# PX4FMUv2_3.net
KiCad netlist of a schematic drawn in EAGLE
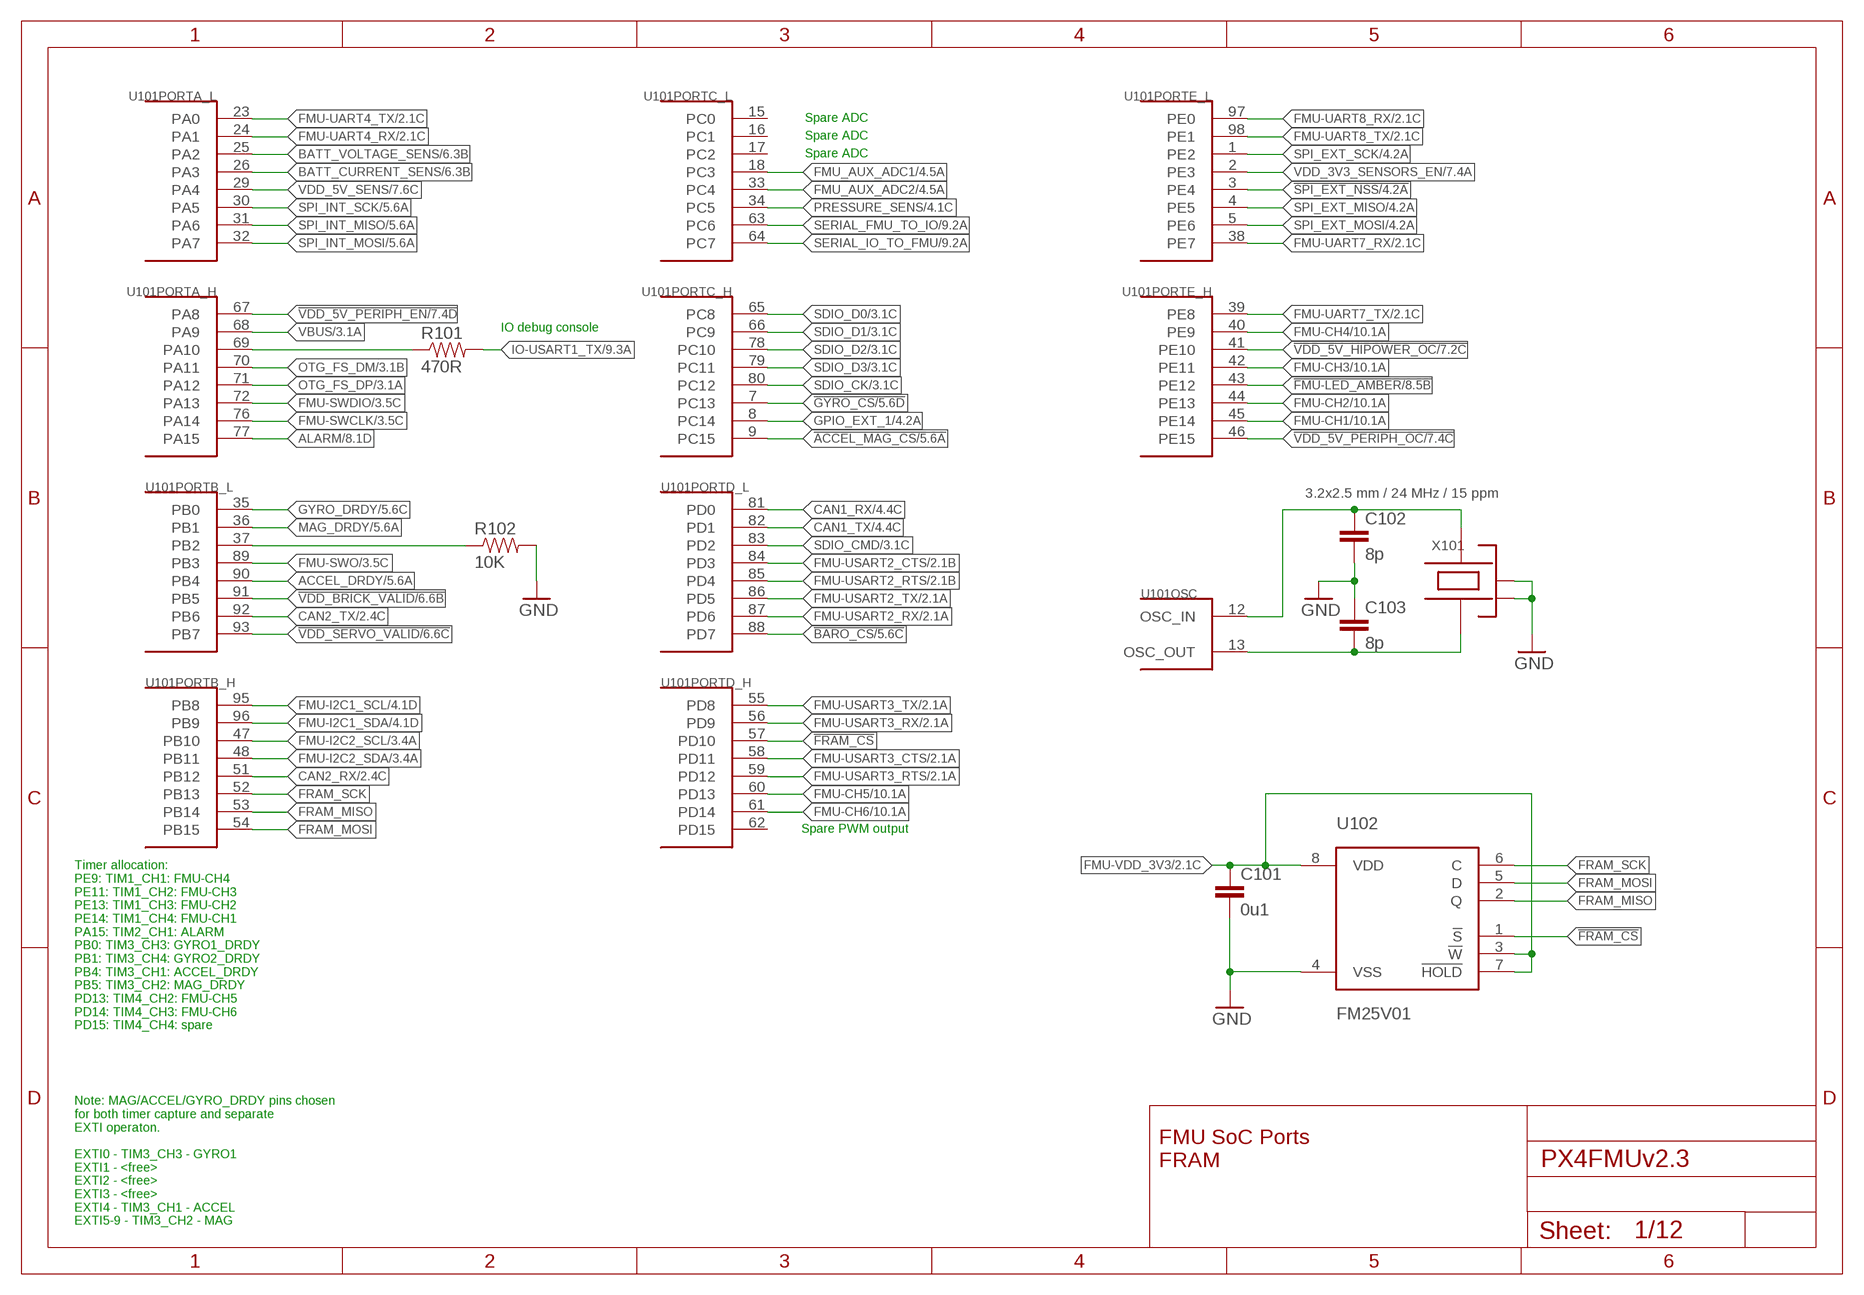
[diagram p0: schematic, sheet 1]
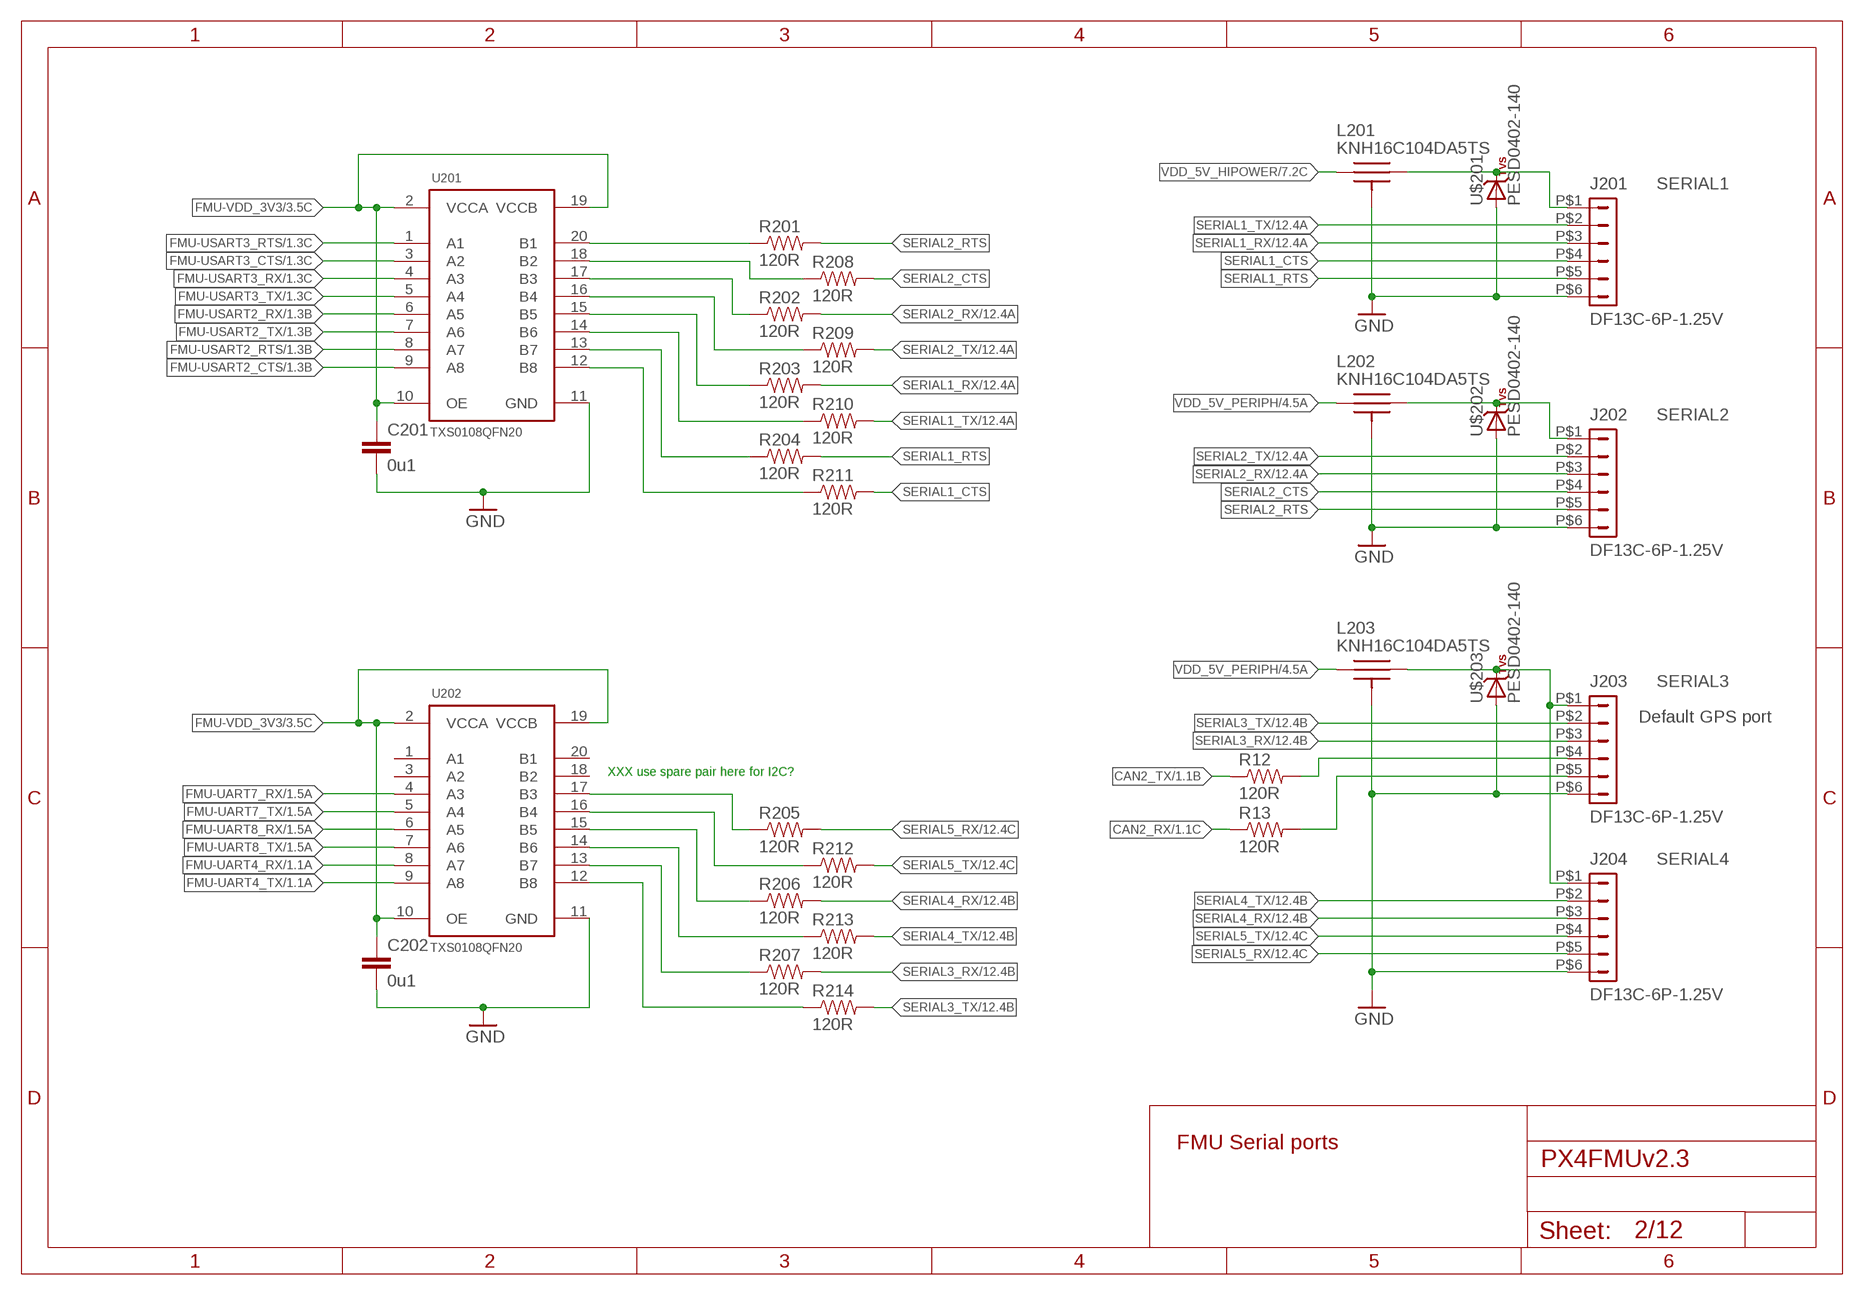
[diagram p1: schematic, sheet 2]
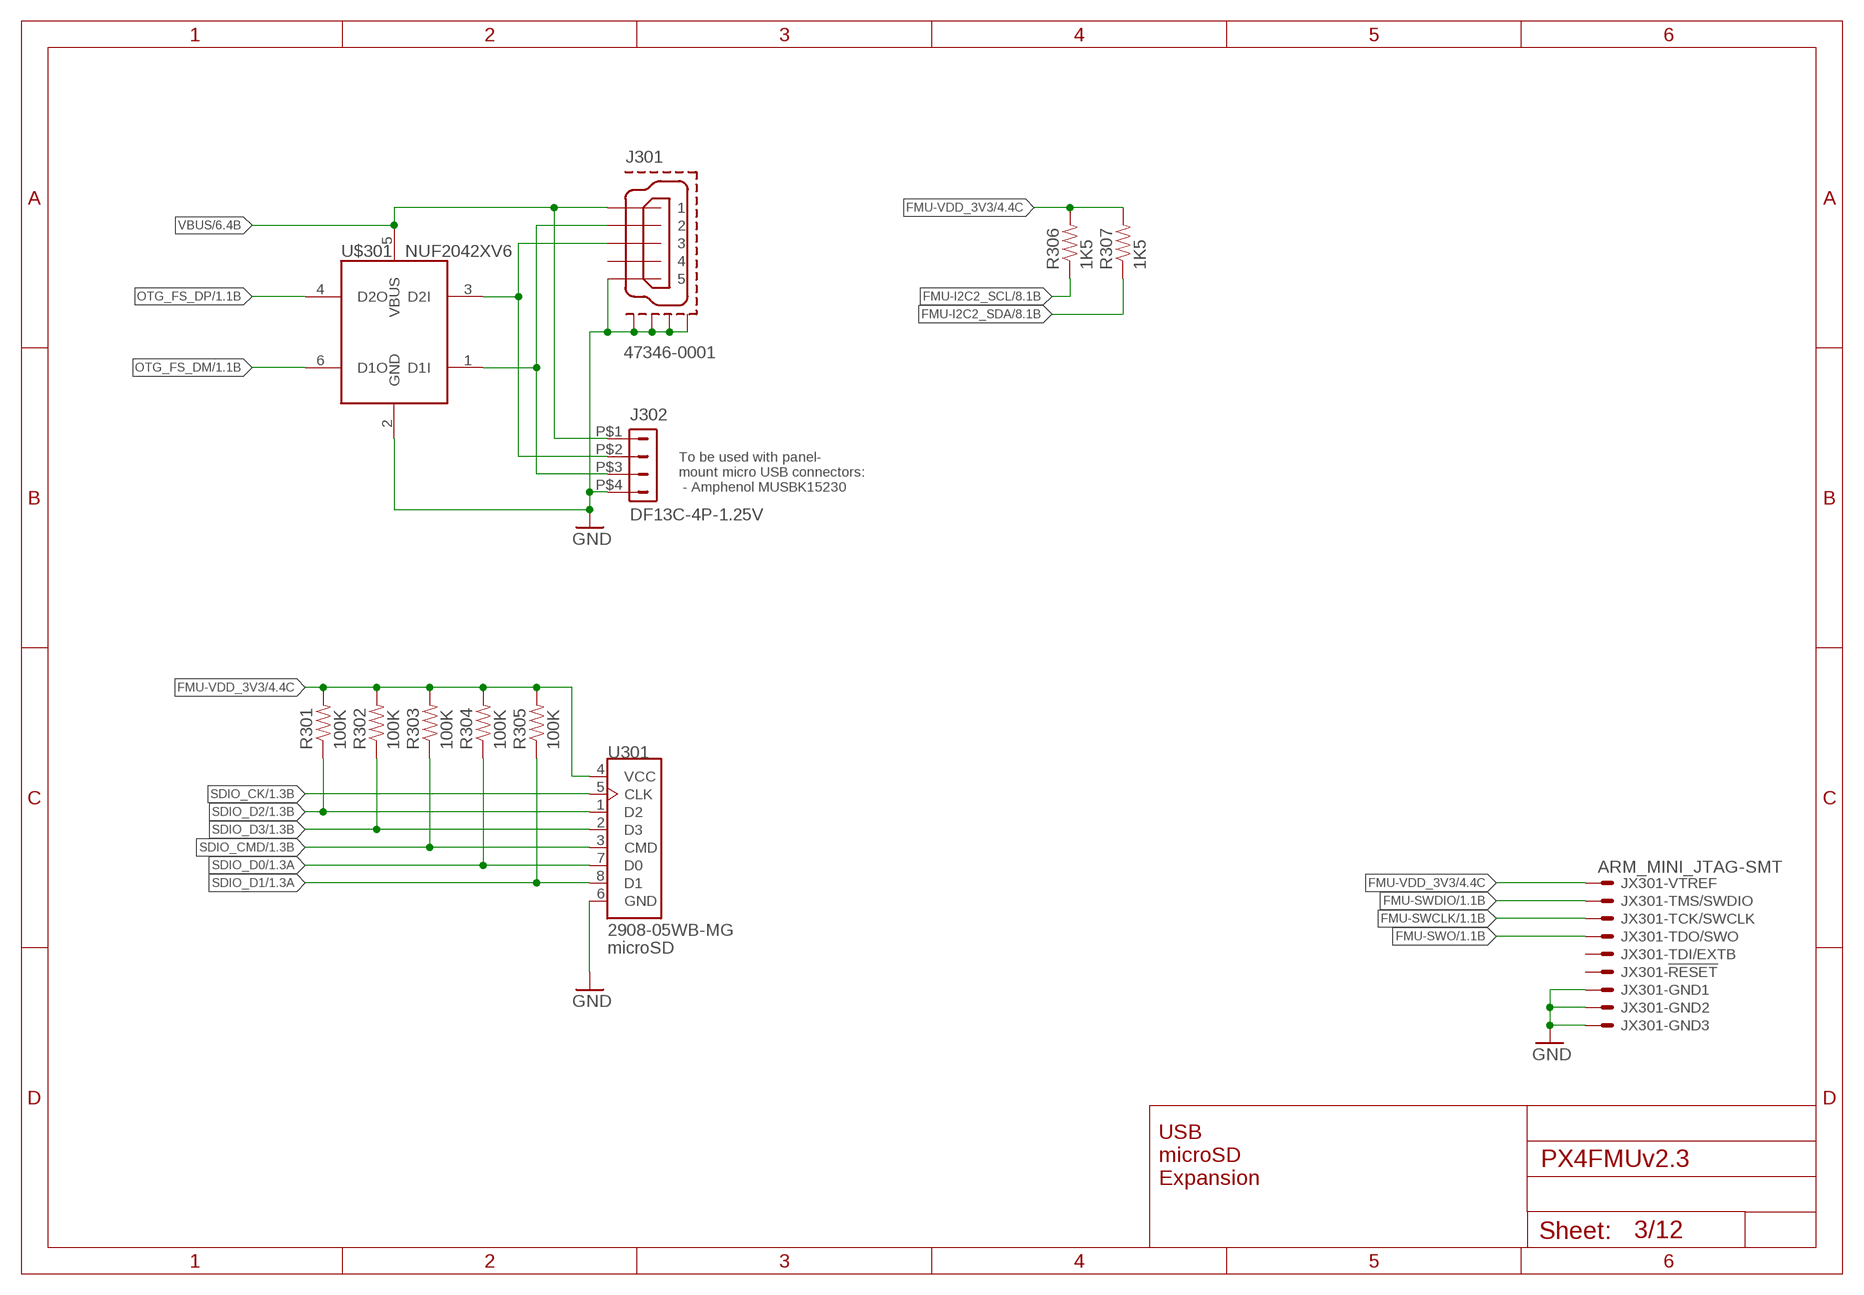
[diagram p2: schematic, sheet 3]
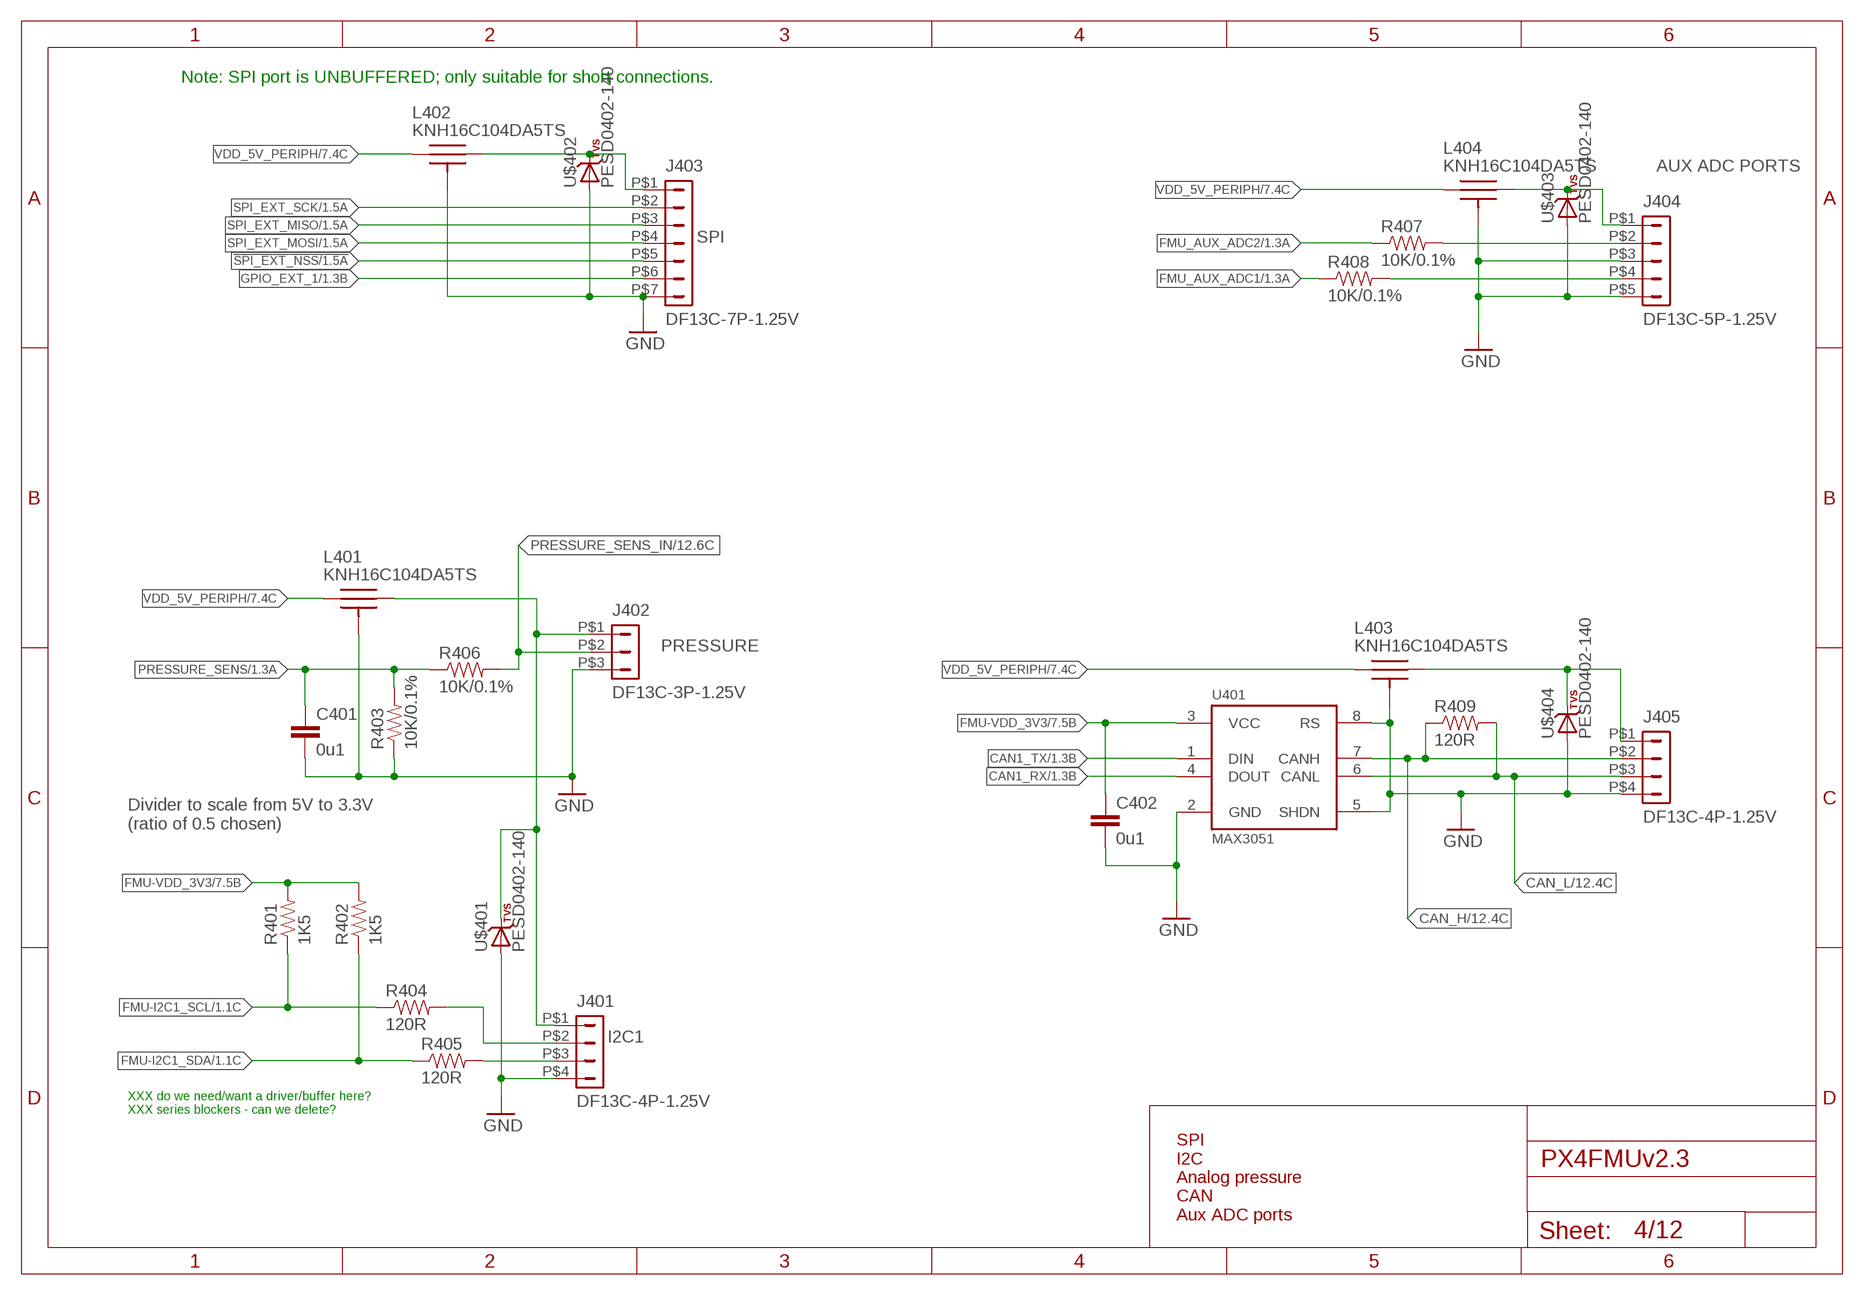
[diagram p3: schematic, sheet 4]
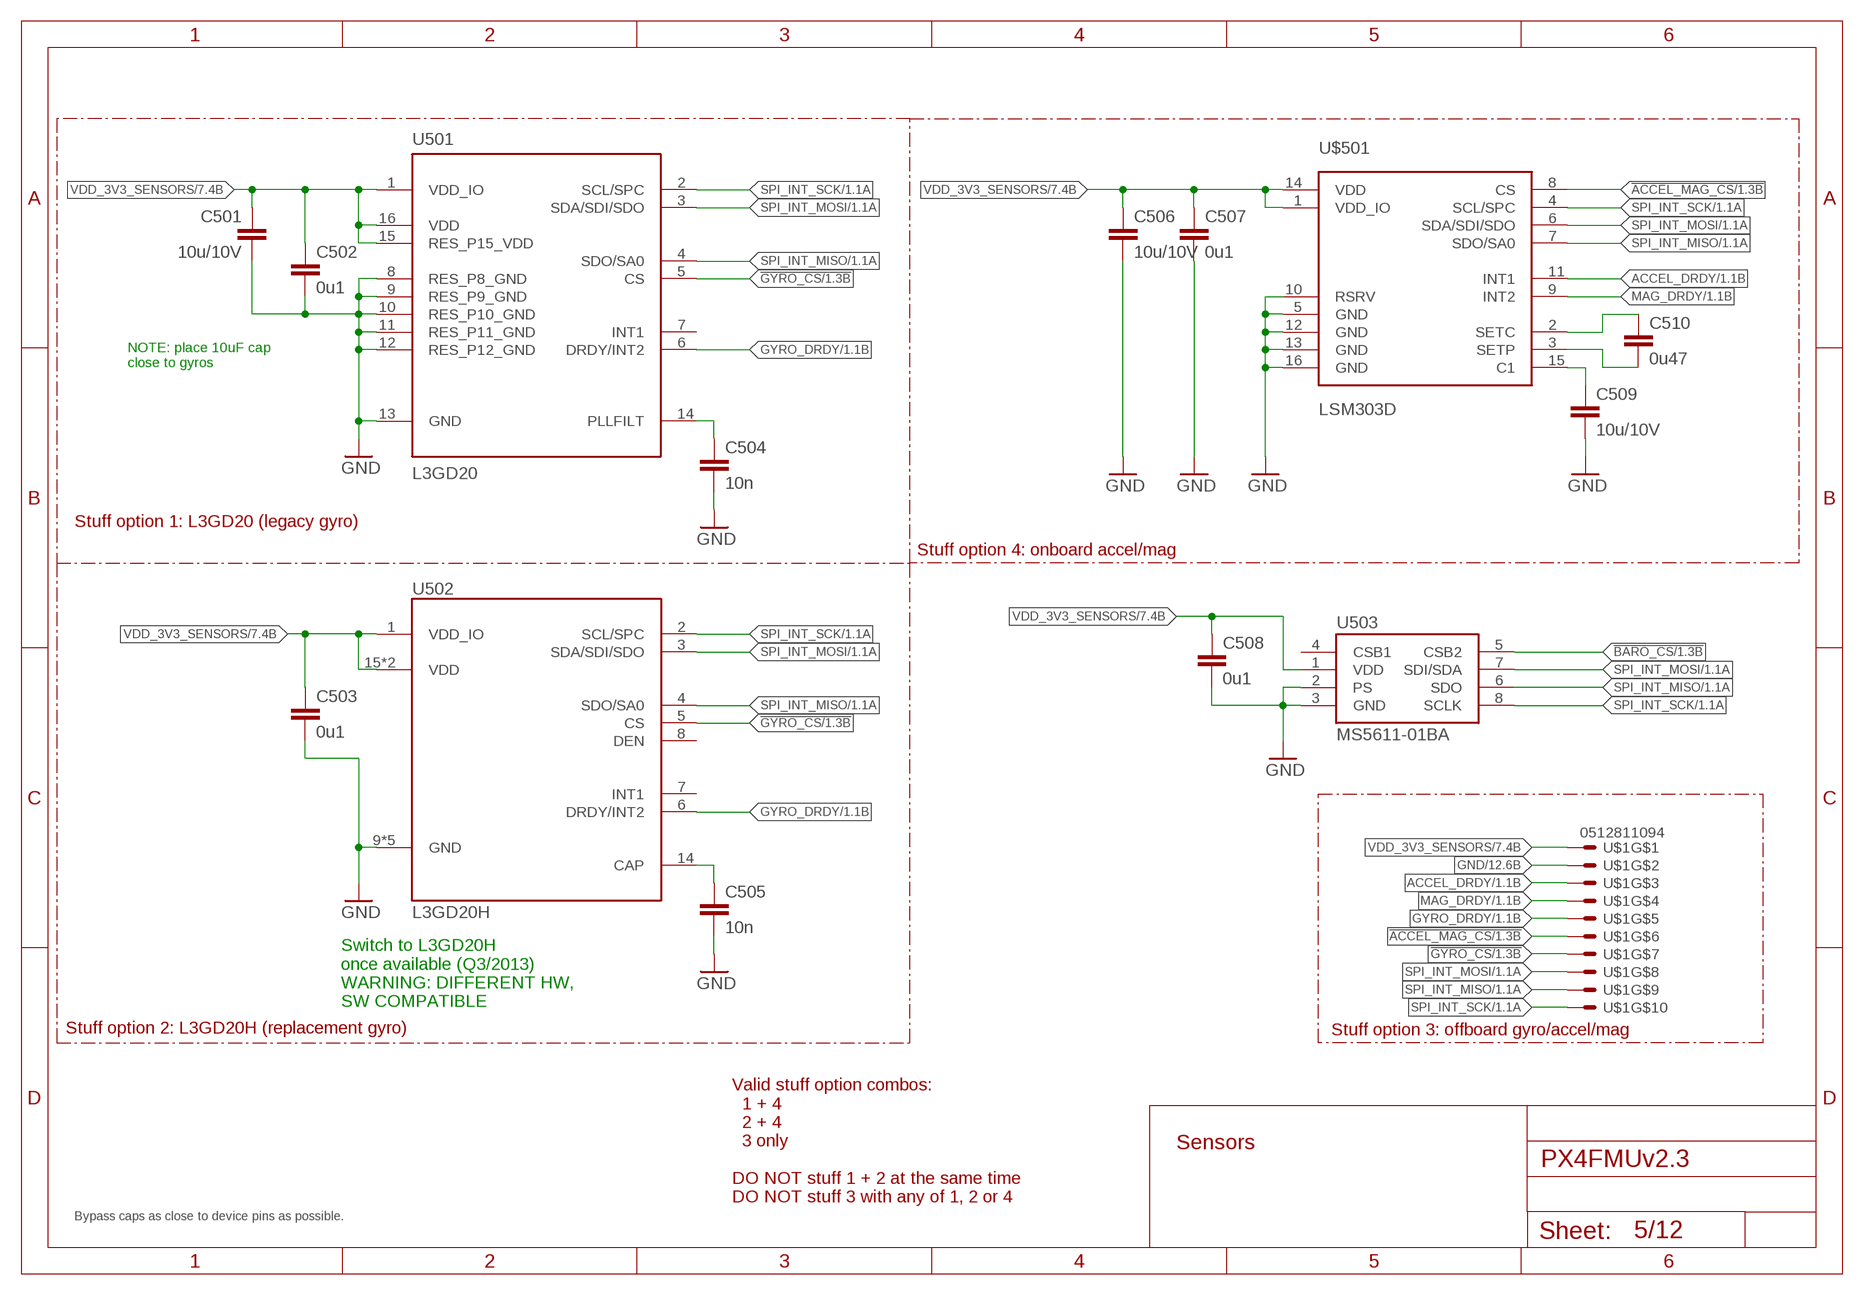
[diagram p4: schematic, sheet 5]
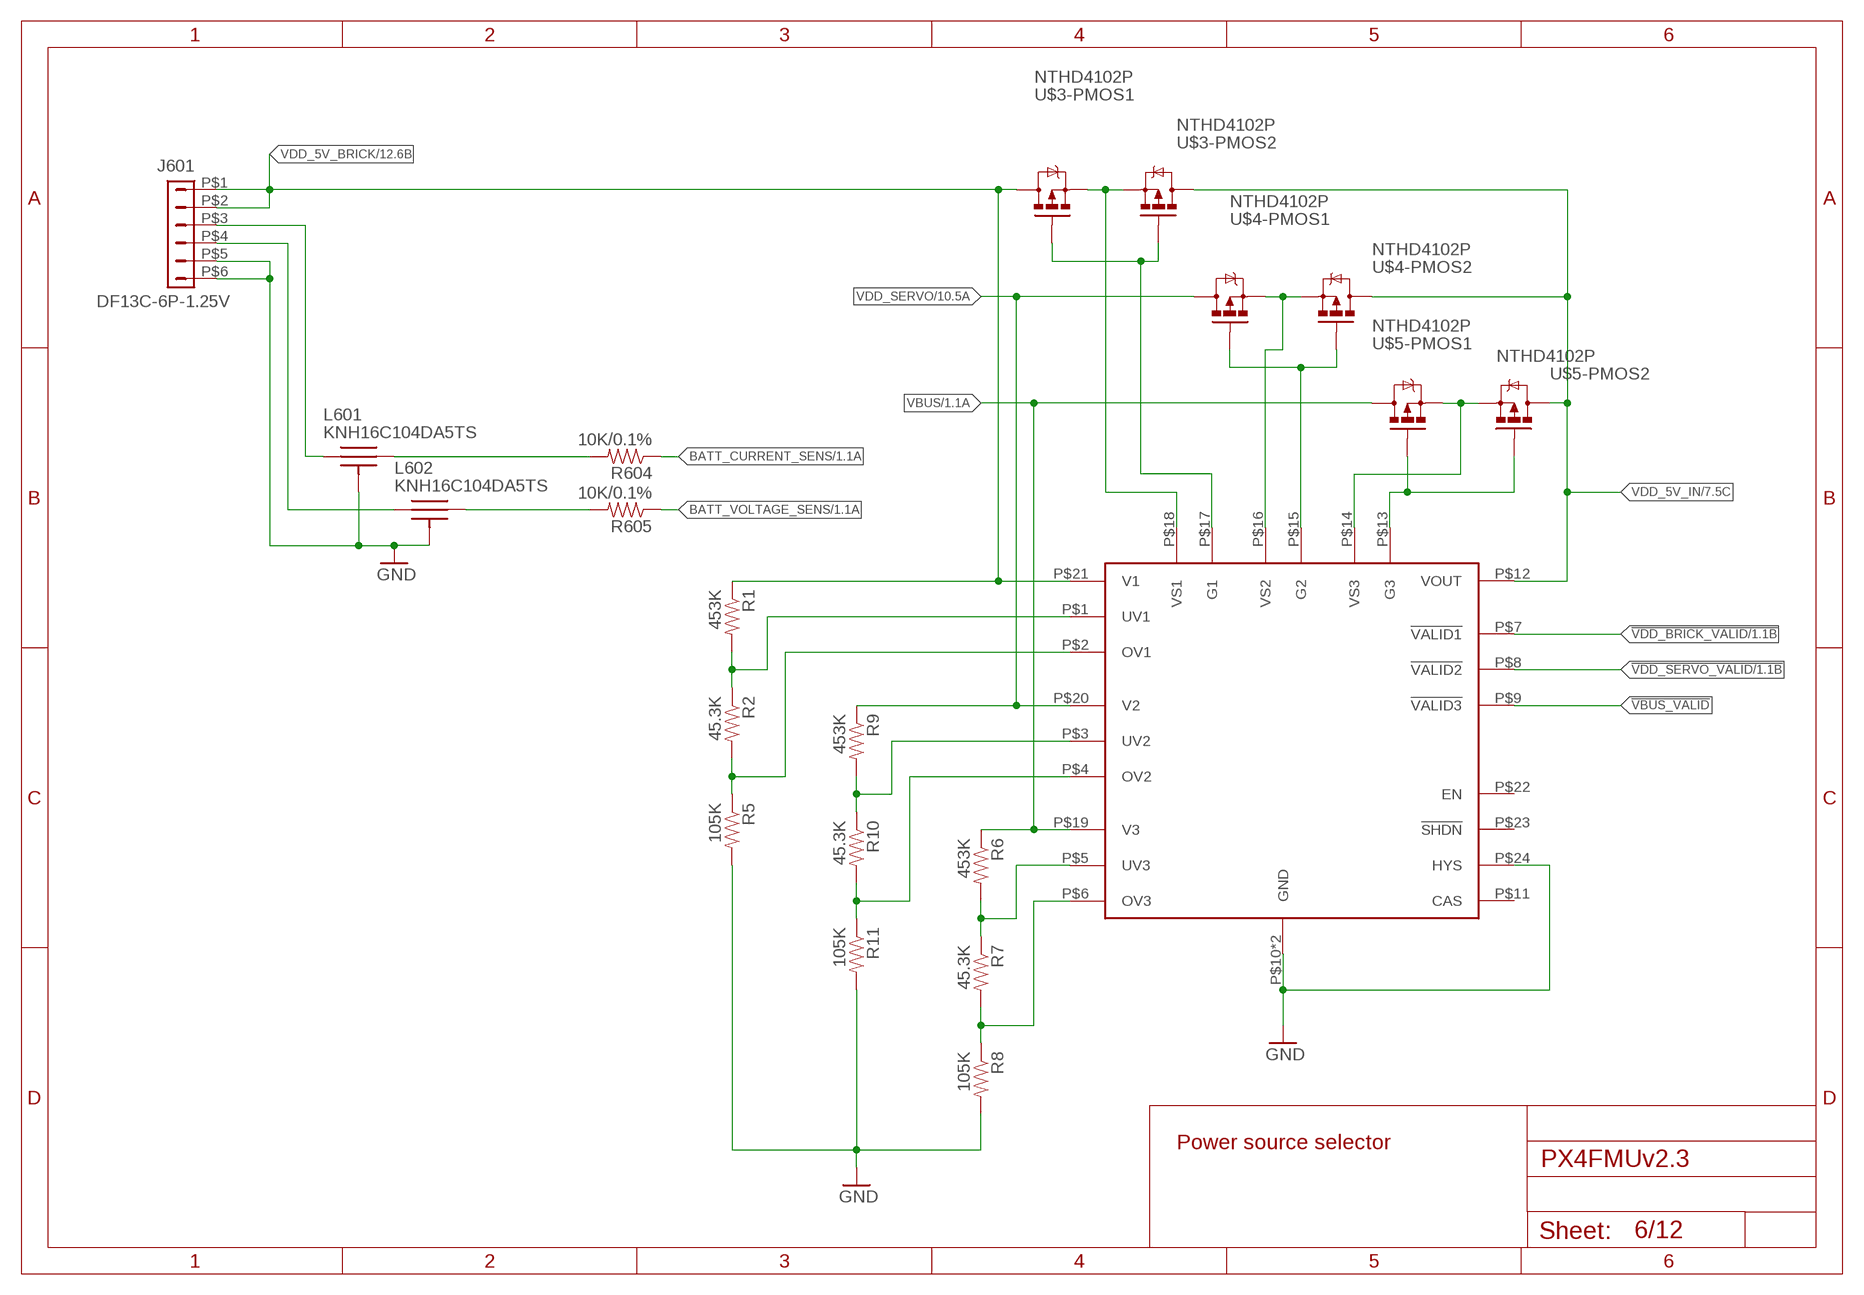
[diagram p5: schematic, sheet 6]
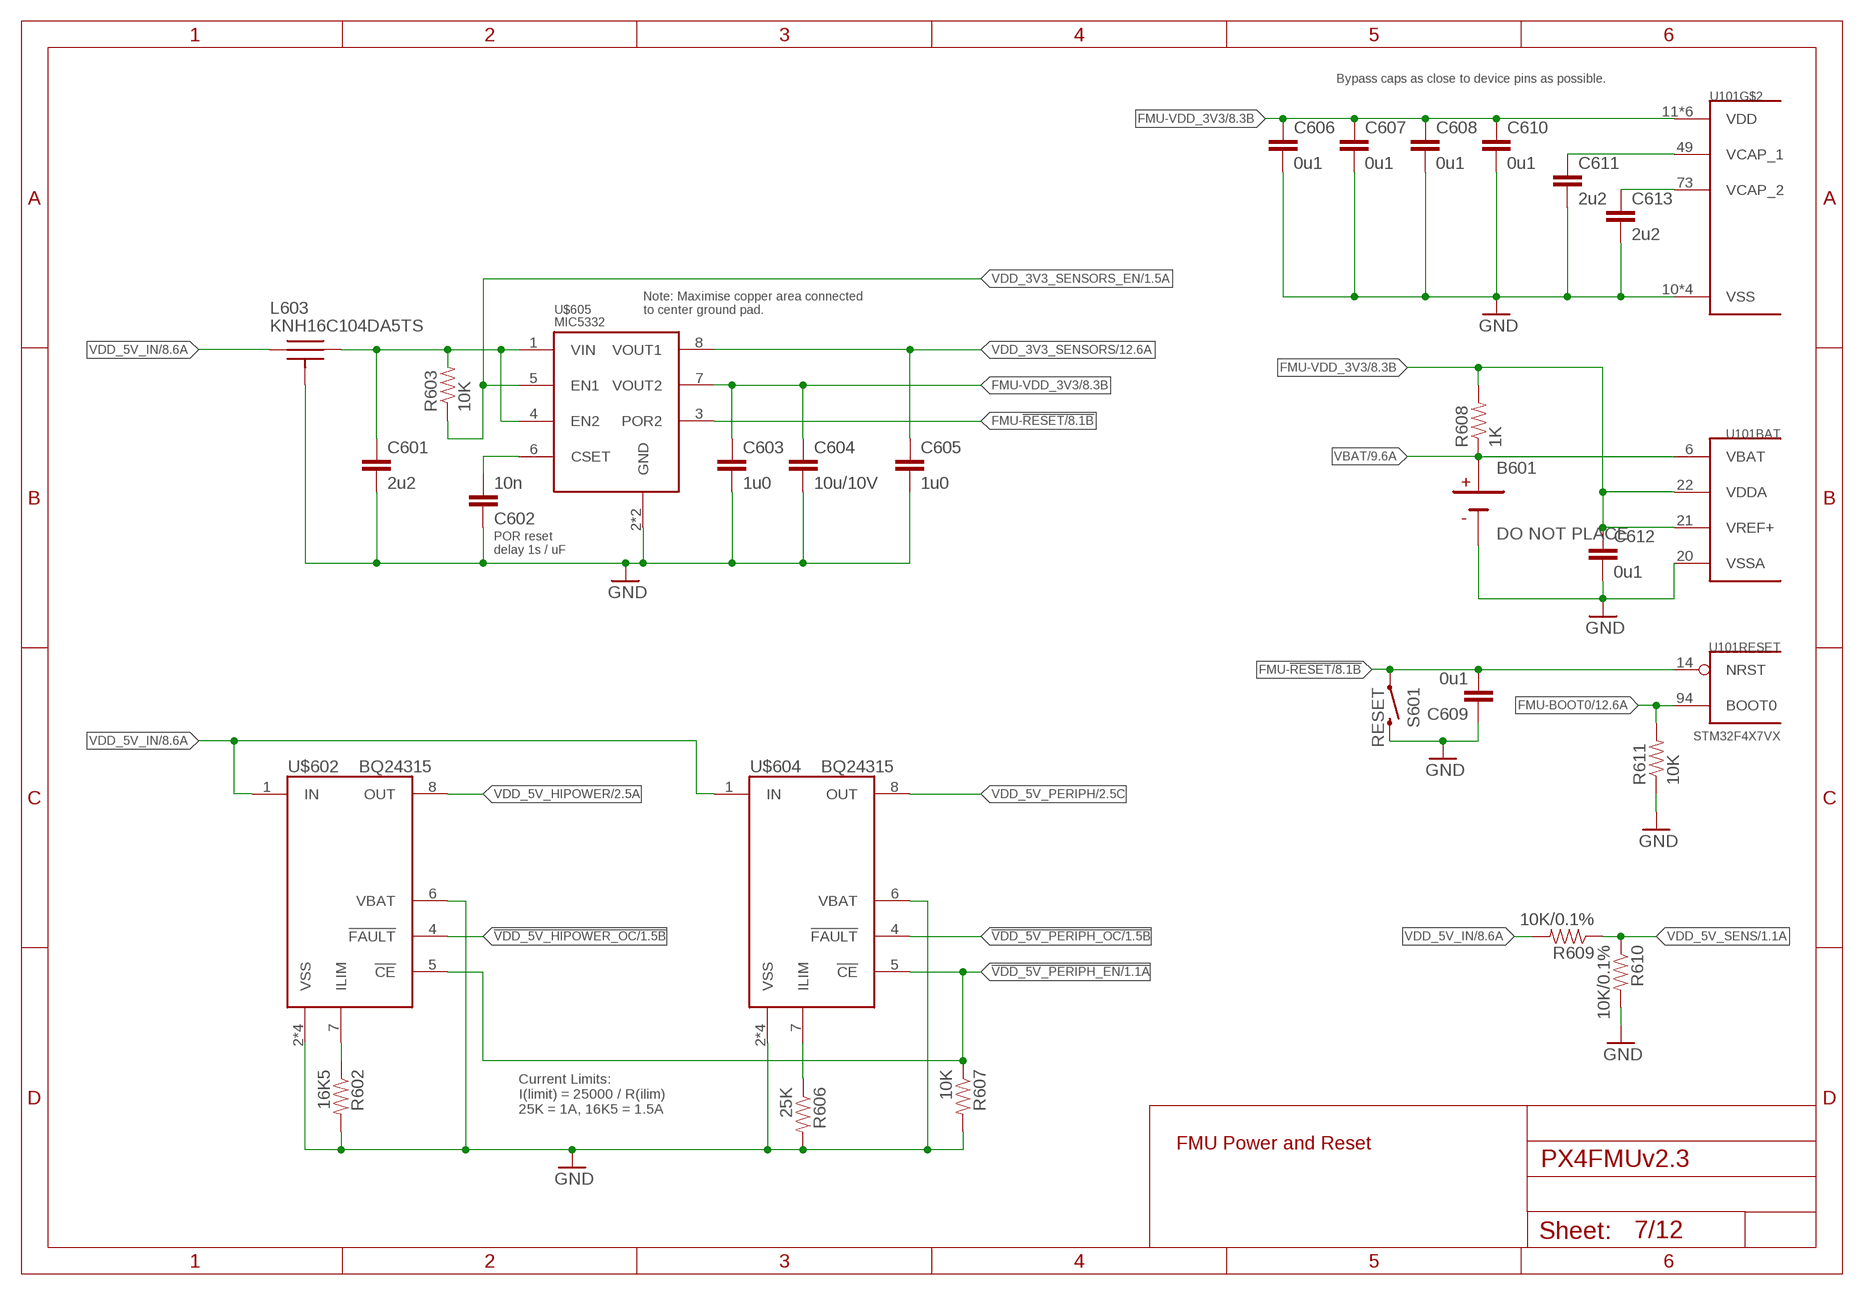
[diagram p6: schematic, sheet 7]
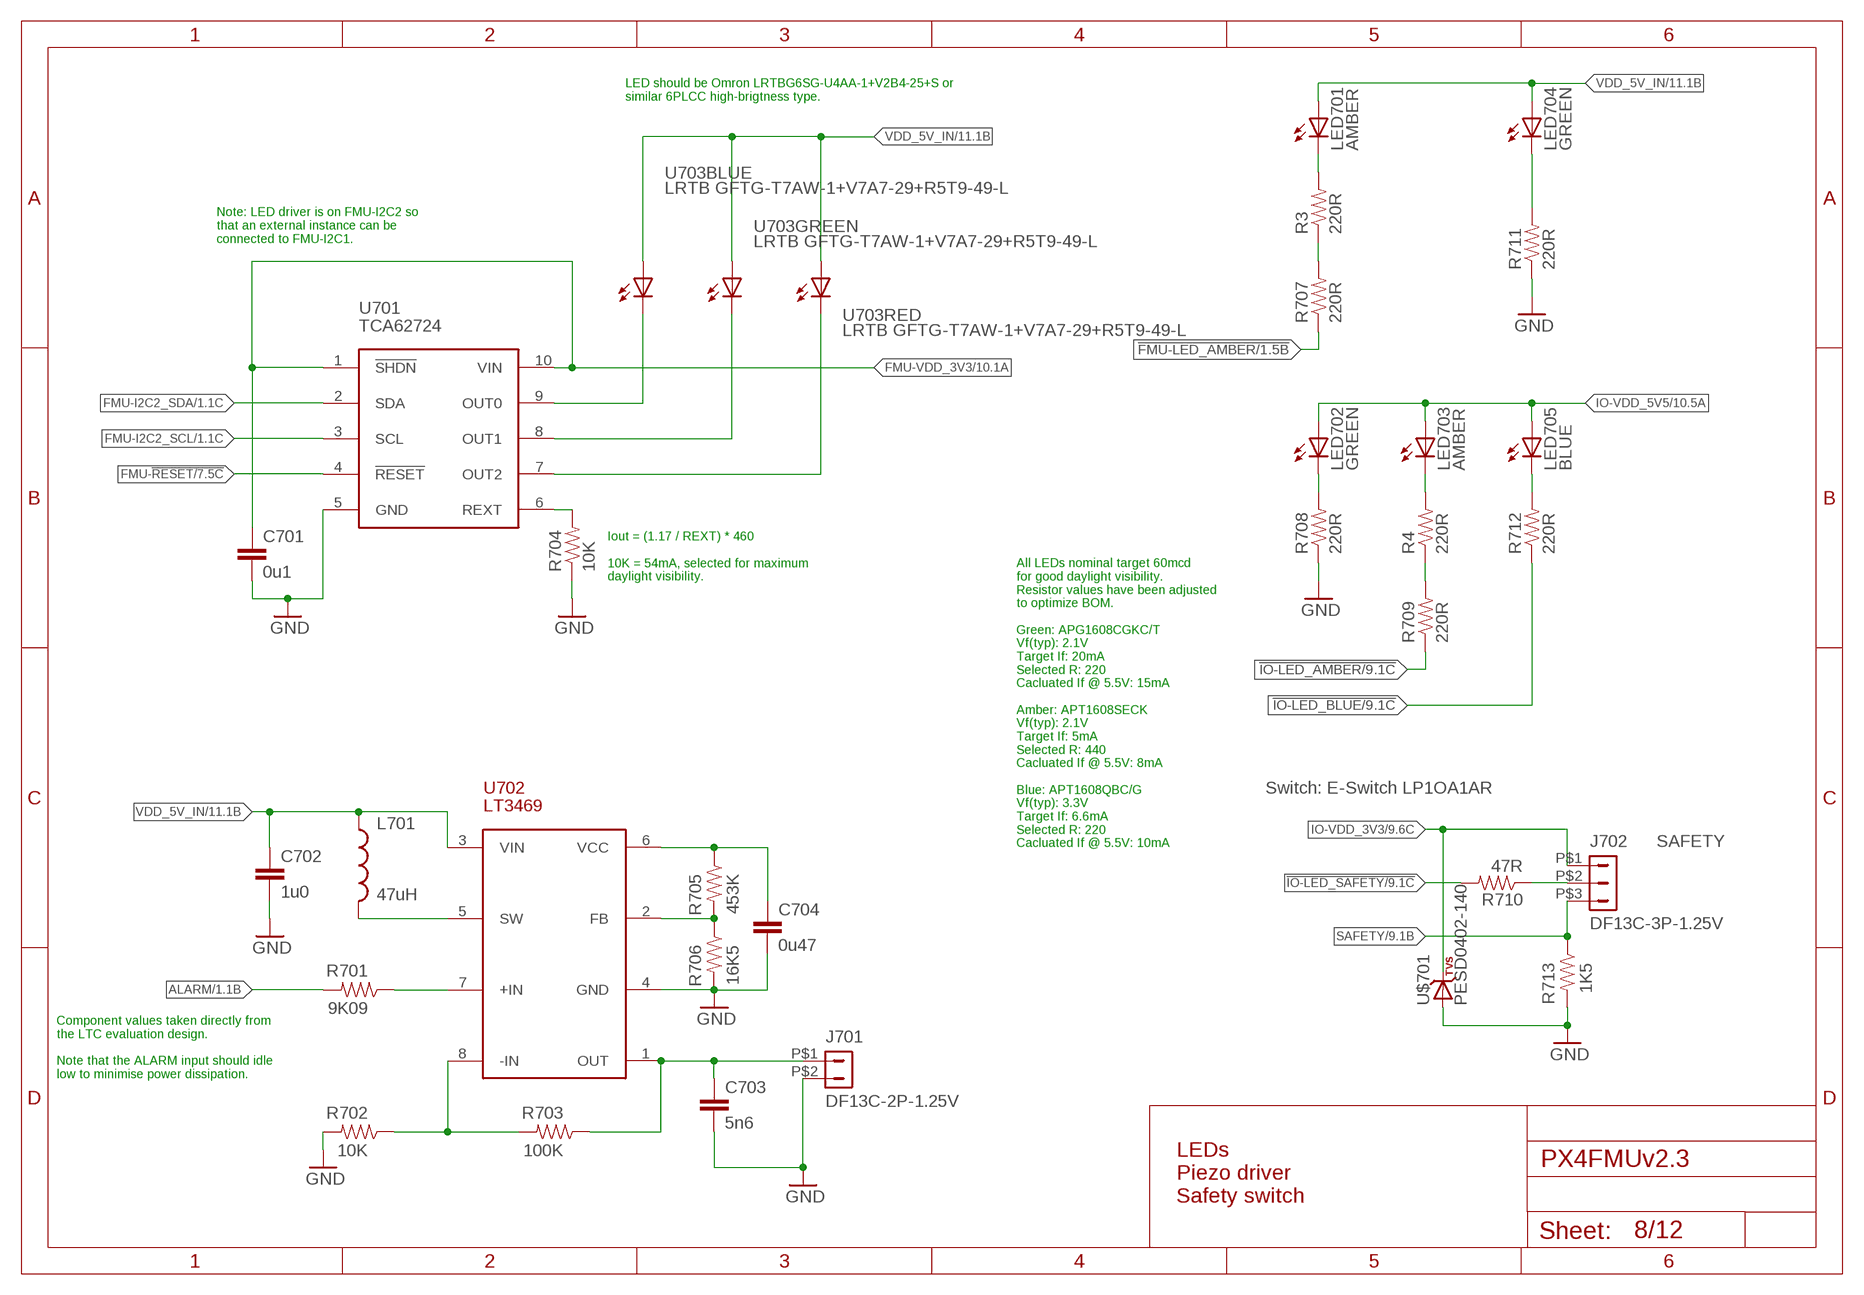
[diagram p7: schematic, sheet 8]
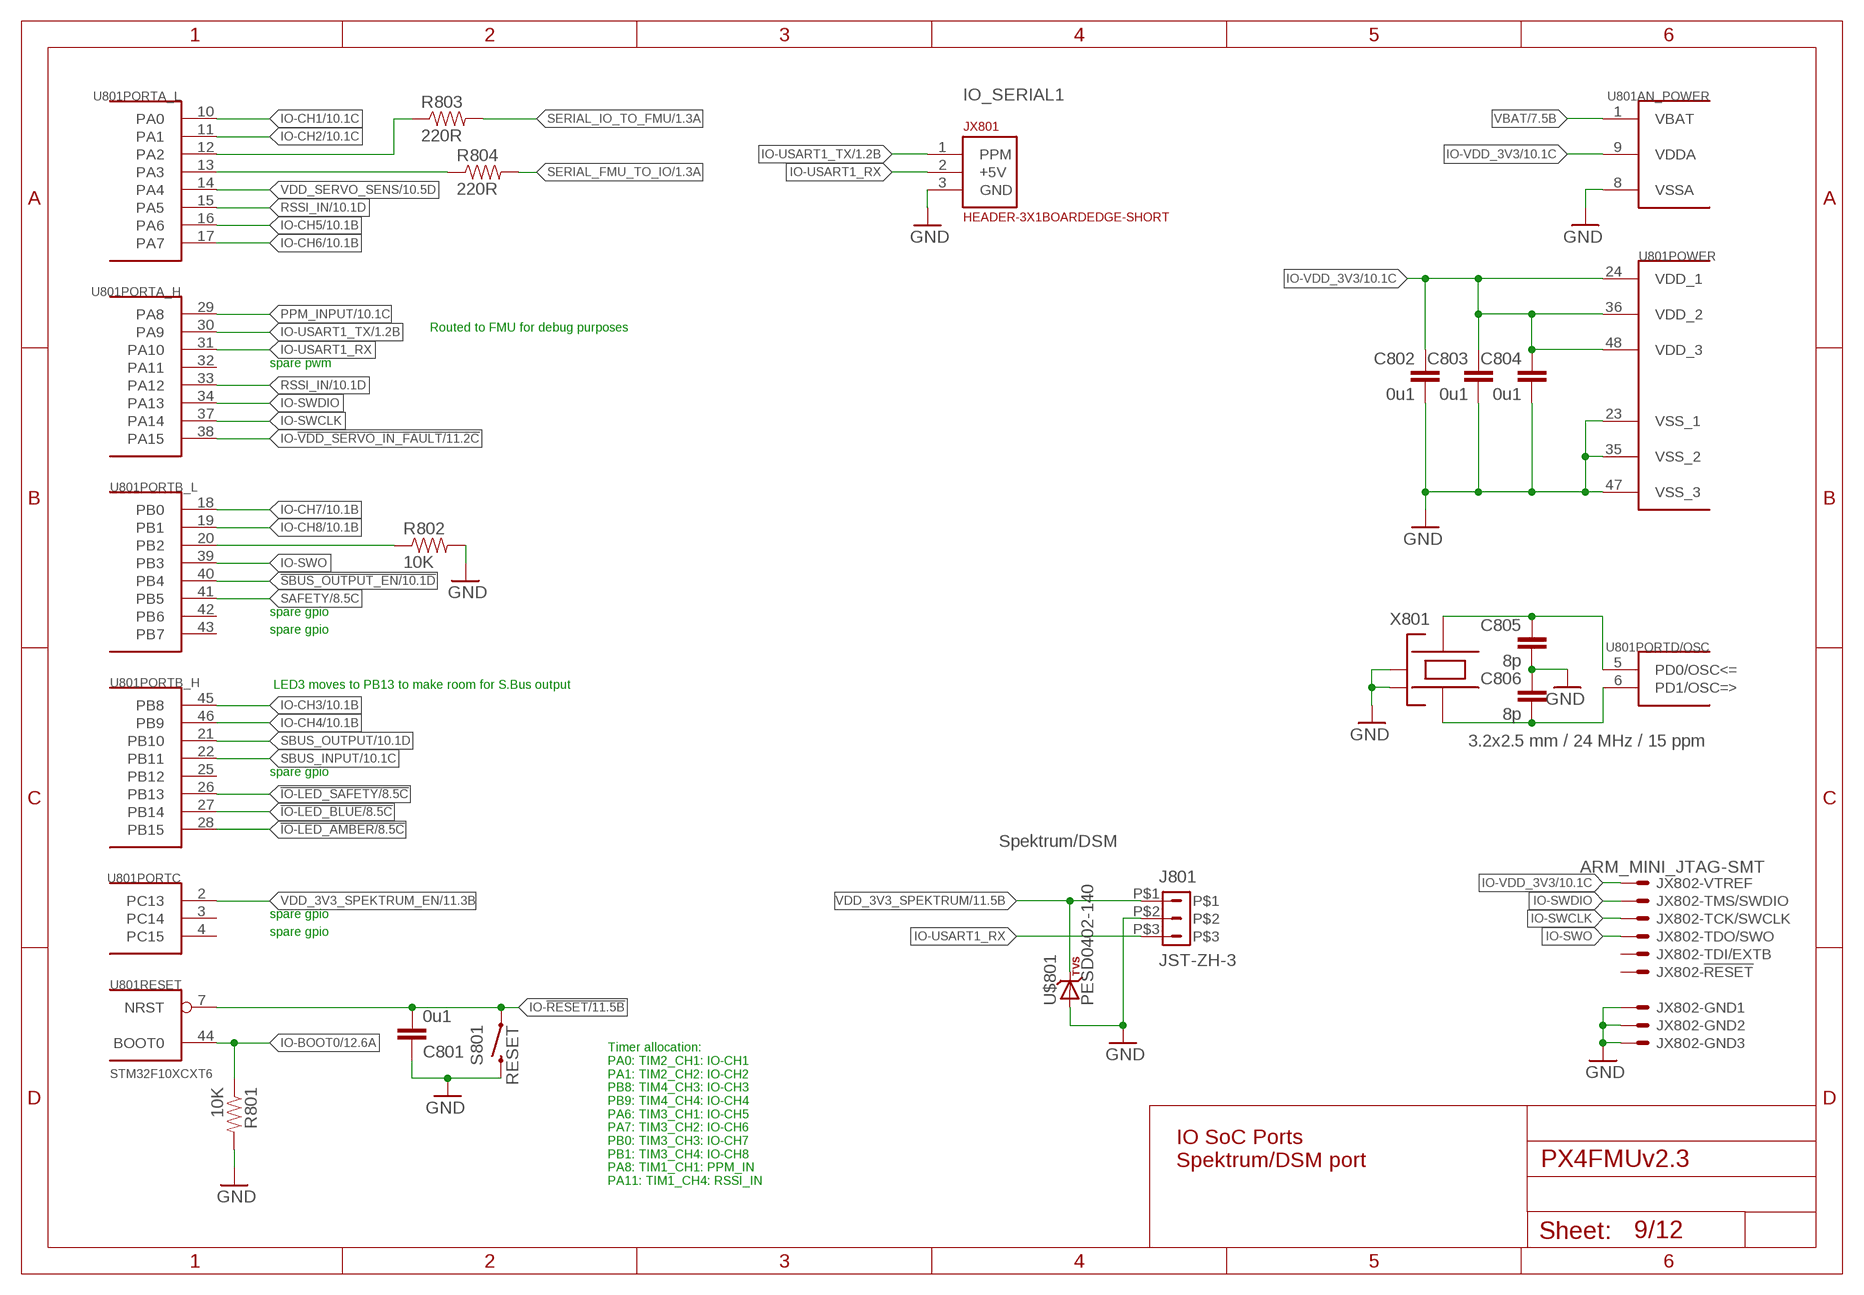
[diagram p8: schematic, sheet 9]
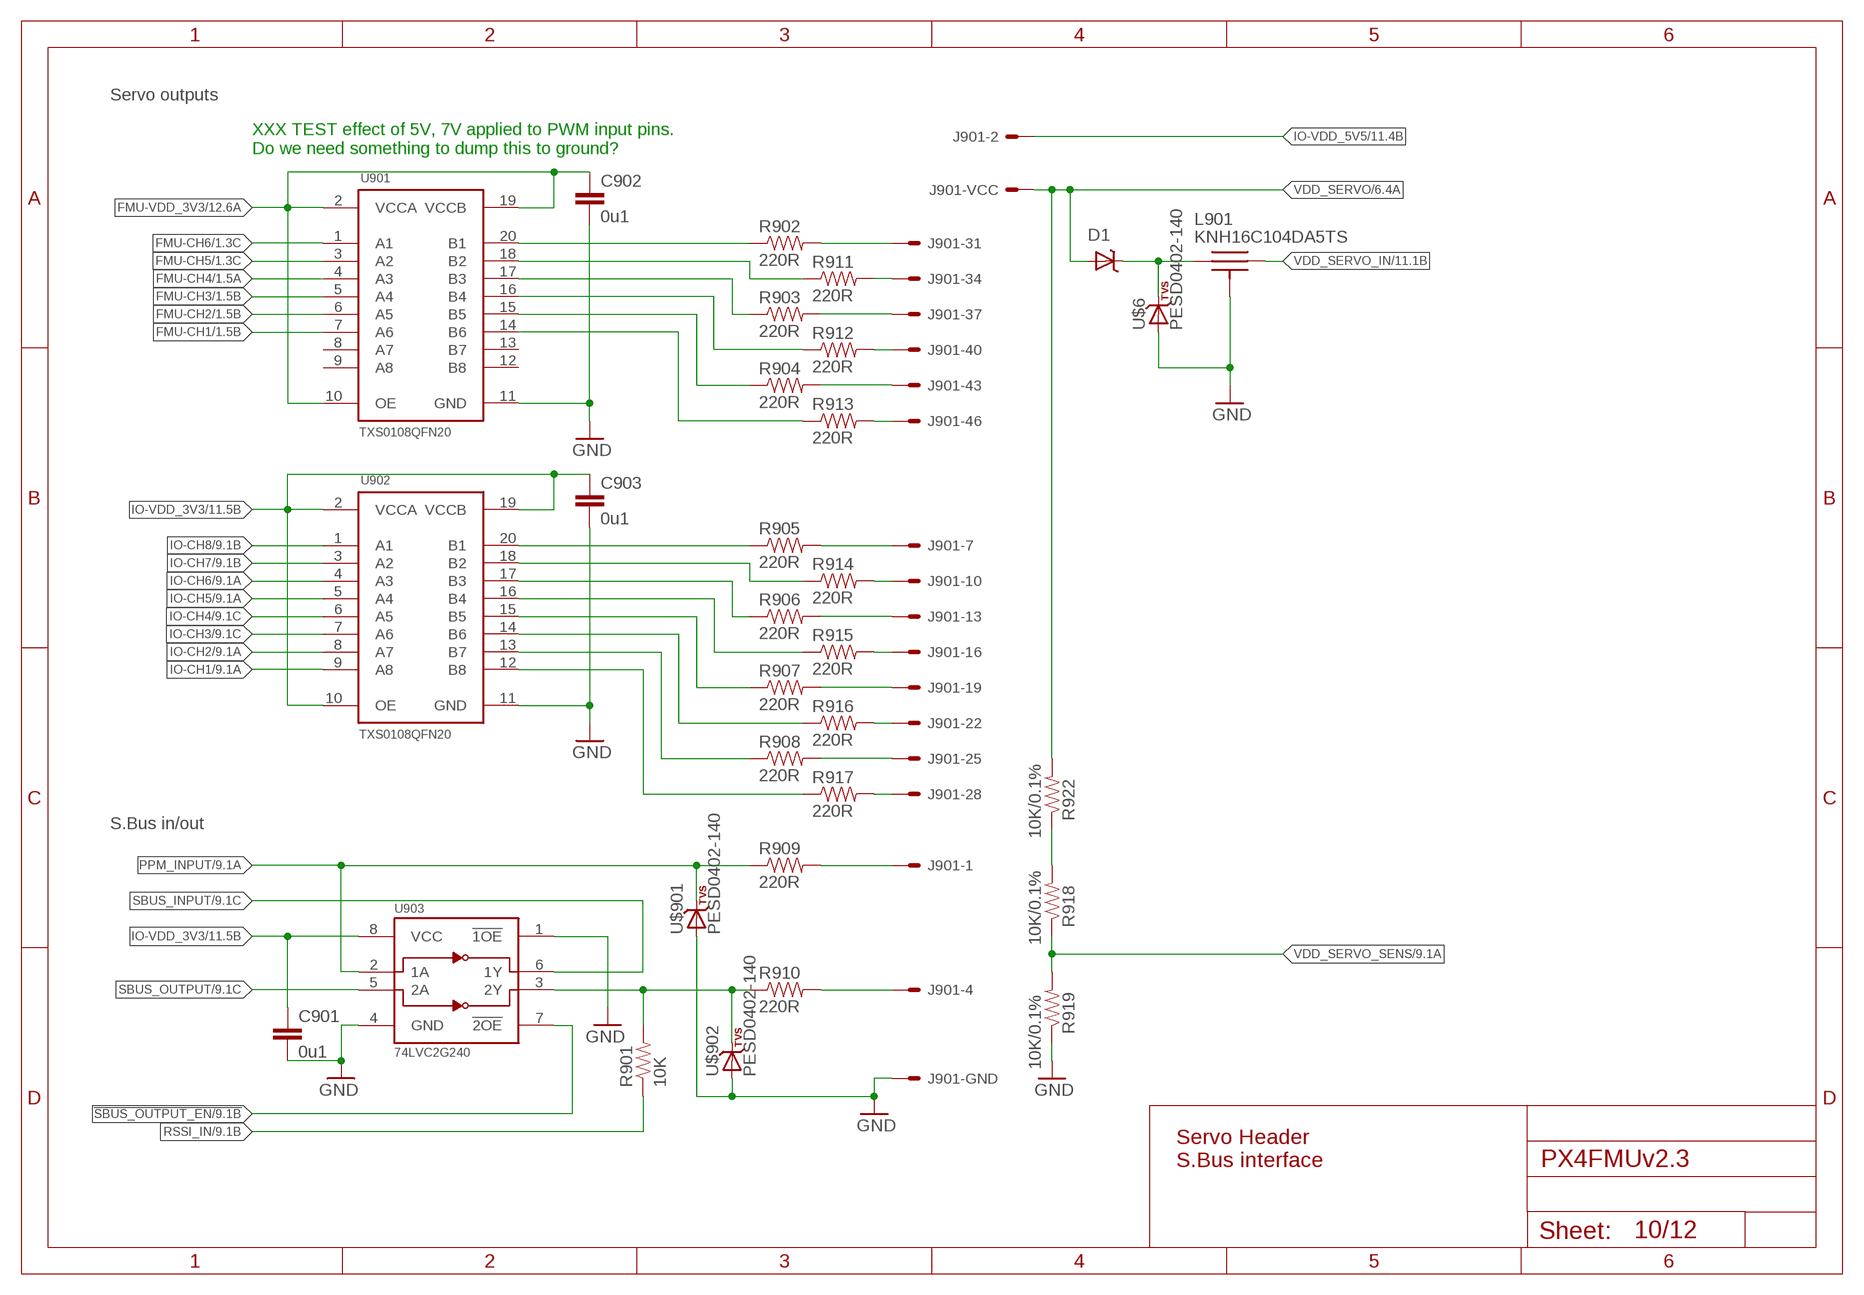
[diagram p9: schematic, sheet 10]
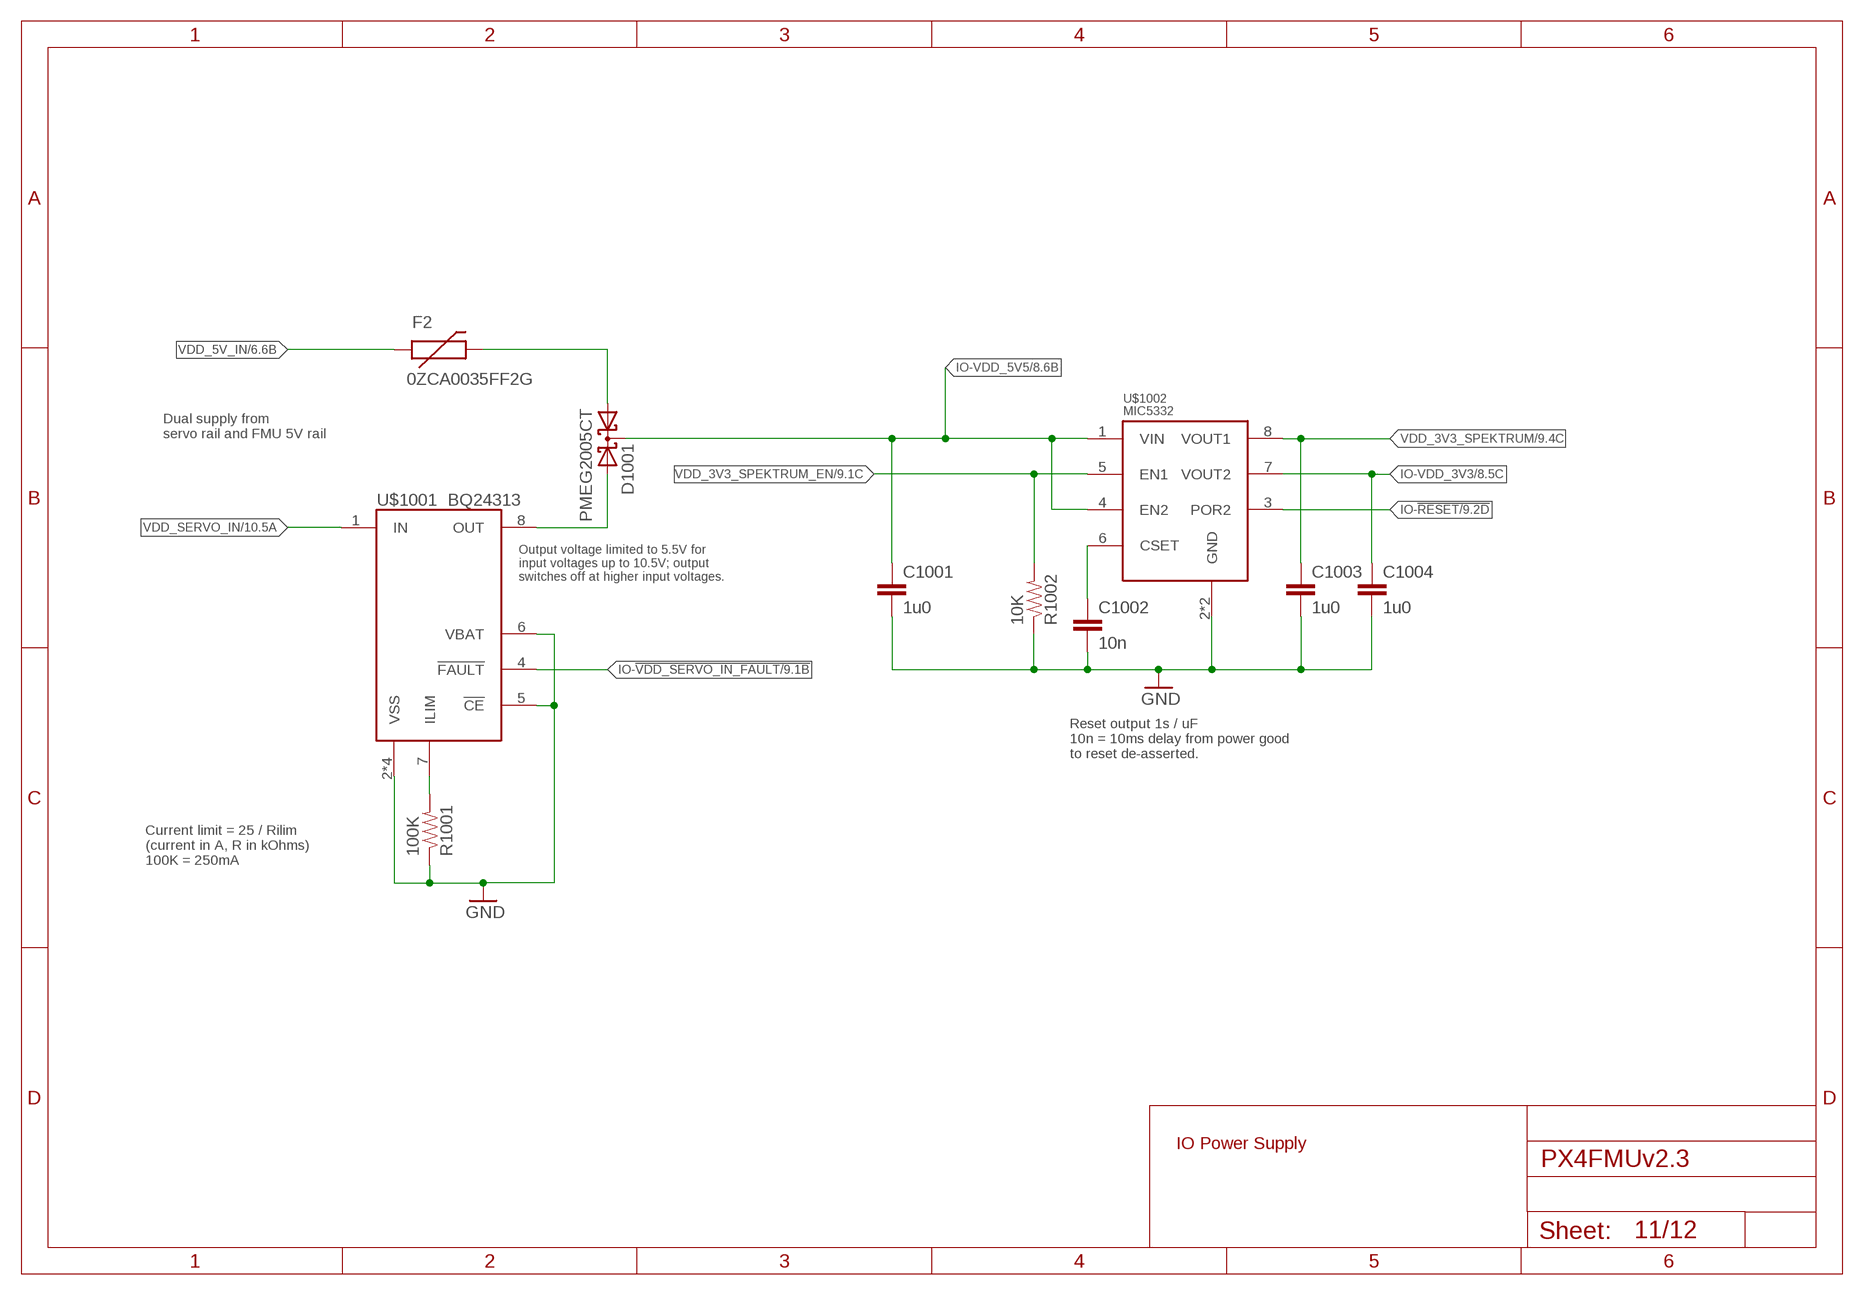
[diagram p10: schematic, sheet 11]
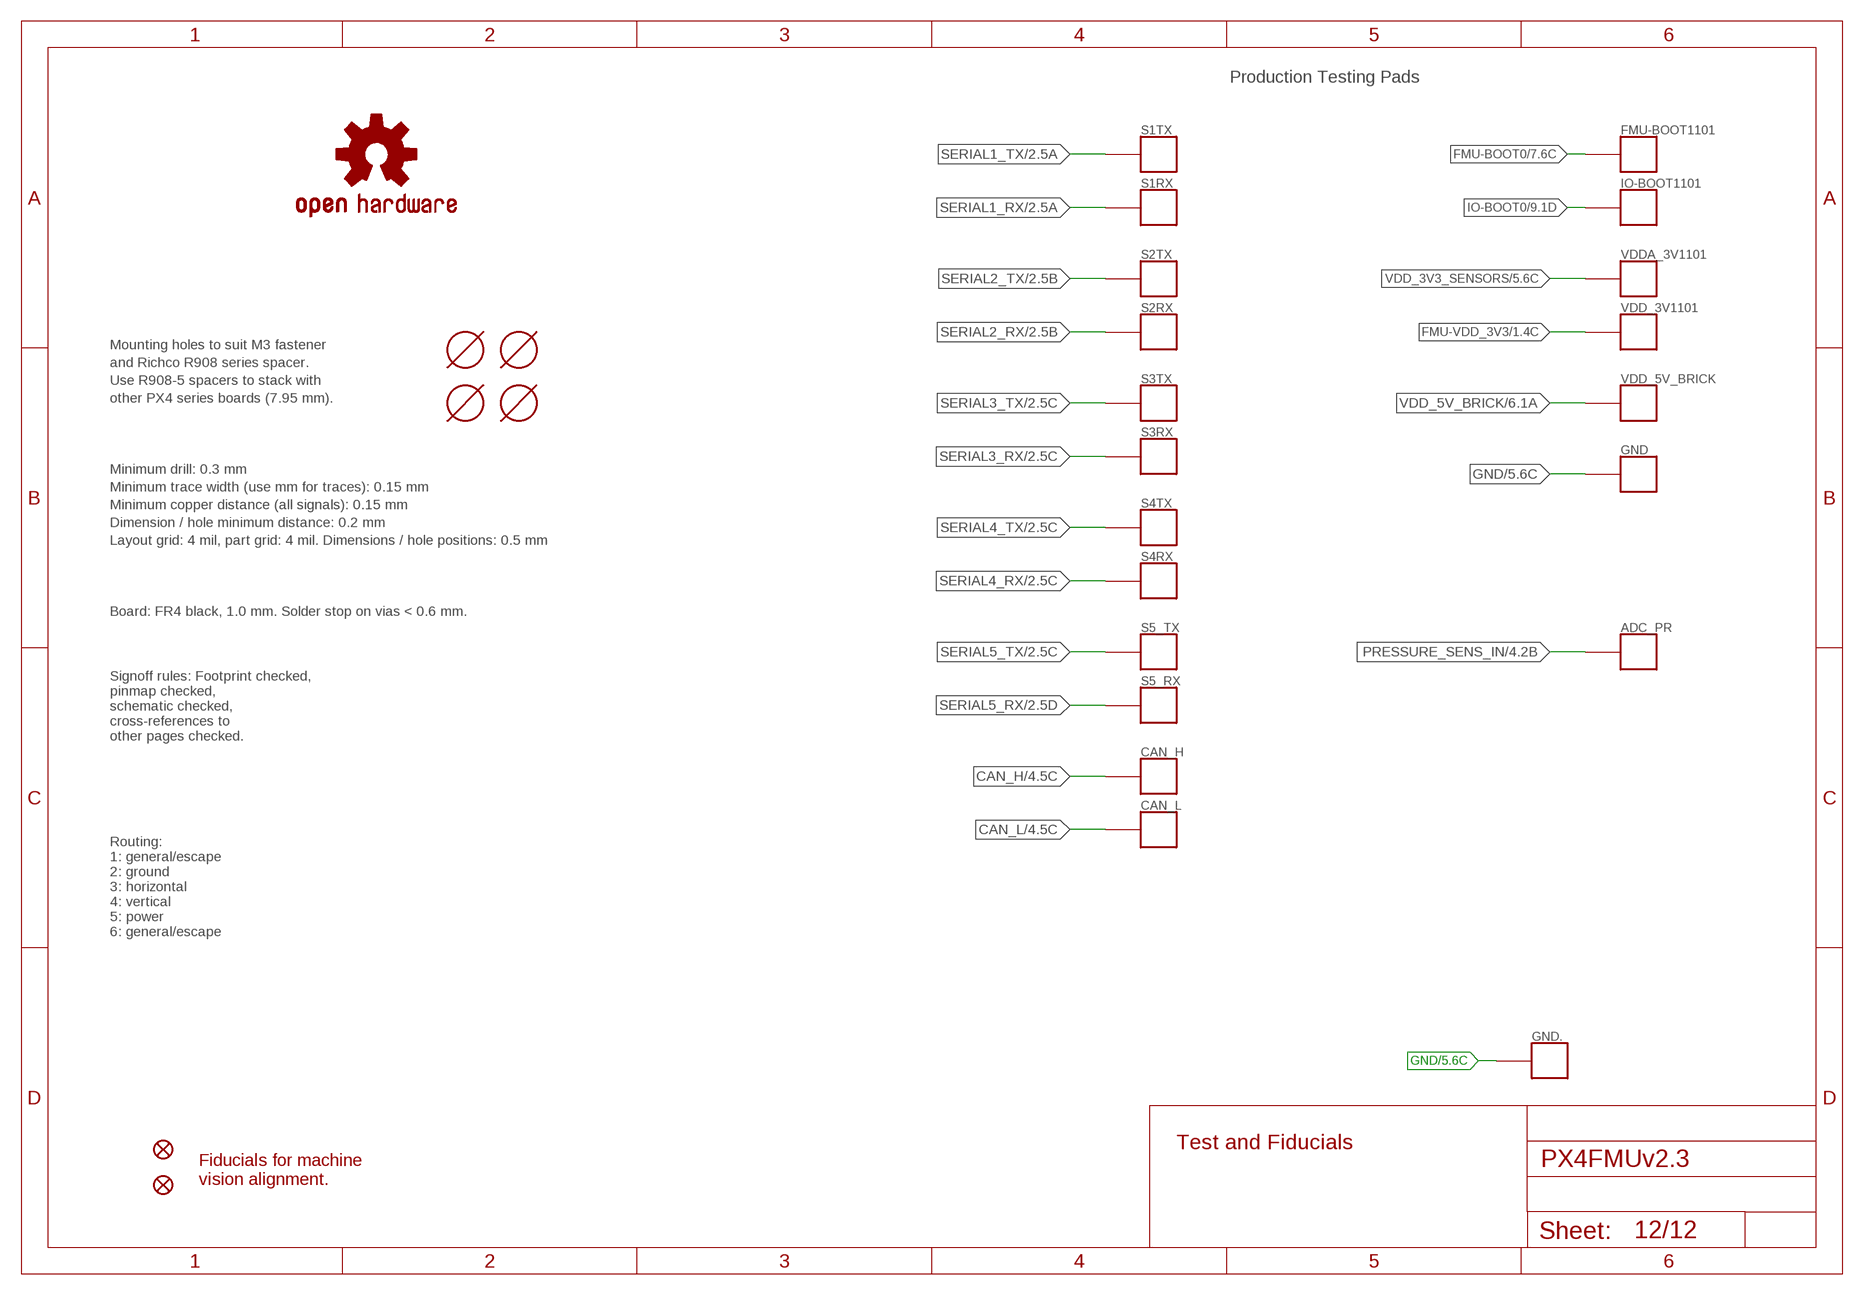
[diagram p11: schematic, sheet 12]

(export (version "E")
  (design (tool "Eeschema 10.0.6"))
  (components
    (comp (ref "C1001")
      (value "1u0")
      (footprint "eagle-import:0603-CAP")
      (fields (field (name "PARTNO") "CC0603ZRY5V7BB105"))
      (libsource (lib "eagle-import") (part "CAP0603"))
    )
    (comp (ref "C1002")
      (value "10n")
      (footprint "eagle-import:0402-CAP")
      (fields (field (name "PARTNO") "CC0402KRX7R7BB103"))
      (libsource (lib "eagle-import") (part "CAP0402"))
    )
    (comp (ref "C1003")
      (value "1u0")
      (footprint "eagle-import:0603-CAP")
      (fields (field (name "PARTNO") "CC0603ZRY5V7BB105"))
      (libsource (lib "eagle-import") (part "CAP0603"))
    )
    (comp (ref "C1004")
      (value "1u0")
      (footprint "eagle-import:0603-CAP")
      (fields (field (name "PARTNO") "CC0603ZRY5V7BB105"))
      (libsource (lib "eagle-import") (part "CAP0603"))
    )
    (comp (ref "D1001")
      (value "PMEG2005CT")
      (footprint "eagle-import:SOT23-3")
      (libsource (lib "eagle-import") (part "PMEG2005CT"))
    )
    (comp (ref "F2")
      (value "0ZCA0035FF2G")
      (footprint "eagle-import:PTC-1206")
      (libsource (lib "eagle-import") (part "PTCSMD"))
    )
    (comp (ref "R1001")
      (value "100K")
      (footprint "eagle-import:0402-RES")
      (fields (field (name "PARTNO") "RC0402FR-07100KL"))
      (libsource (lib "eagle-import") (part "RESISTOR0402-RES"))
    )
    (comp (ref "R1002")
      (value "10K")
      (footprint "eagle-import:0402-RES")
      (fields (field (name "PARTNO") "RC0402FR-0710KL"))
      (libsource (lib "eagle-import") (part "RESISTOR0402-RES"))
    )
    (comp (ref "U$1001")
      (value "BQ24313")
      (footprint "eagle-import:QFN8-DSG")
      (fields (field (name "PARTNO") "BQ24313DSGT"))
      (libsource (lib "eagle-import") (part "BQ24313"))
    )
    (comp (ref "U$1002")
      (value "MIC5332")
      (footprint "eagle-import:MLF-8-EPAD")
      (fields (field (name "PARTNO") "MIC5332-SSYMT"))
      (libsource (lib "eagle-import") (part "MIC5332"))
    )
    (comp (ref "J601")
      (value "DF13C-6P-1.25V")
      (footprint "eagle-import:DF13C-6P-1.25V")
      (fields (field (name "PARTNO") "DF13C-6P-1.25V(20)"))
      (libsource (lib "eagle-import") (part "DF13-6P-1.25V"))
    )
    (comp (ref "L601")
      (value "KNH16C104DA5TS")
      (footprint "eagle-import:KYOCERA-KNH16-DA")
      (libsource (lib "eagle-import") (part "KNH16C104DA5TS"))
    )
    (comp (ref "L602")
      (value "KNH16C104DA5TS")
      (footprint "eagle-import:KYOCERA-KNH16-DA")
      (libsource (lib "eagle-import") (part "KNH16C104DA5TS"))
    )
    (comp (ref "R1")
      (value "453K")
      (footprint "eagle-import:0402-RES")
      (fields (field (name "PARTNO") "RMCF0402FT453K"))
      (libsource (lib "eagle-import") (part "RESISTOR0402-RES"))
    )
    (comp (ref "R2")
      (value "45.3K")
      (footprint "eagle-import:0402-RES")
      (libsource (lib "eagle-import") (part "RESISTOR0402-RES"))
    )
    (comp (ref "R5")
      (value "105K")
      (footprint "eagle-import:0402-RES")
      (libsource (lib "eagle-import") (part "RESISTOR0402-RES"))
    )
    (comp (ref "R6")
      (value "453K")
      (footprint "eagle-import:0402-RES")
      (fields (field (name "PARTNO") "RMCF0402FT453K"))
      (libsource (lib "eagle-import") (part "RESISTOR0402-RES"))
    )
    (comp (ref "R7")
      (value "45.3K")
      (footprint "eagle-import:0402-RES")
      (libsource (lib "eagle-import") (part "RESISTOR0402-RES"))
    )
    (comp (ref "R8")
      (value "105K")
      (footprint "eagle-import:0402-RES")
      (libsource (lib "eagle-import") (part "RESISTOR0402-RES"))
    )
    (comp (ref "R9")
      (value "453K")
      (footprint "eagle-import:0402-RES")
      (fields (field (name "PARTNO") "RMCF0402FT453K"))
      (libsource (lib "eagle-import") (part "RESISTOR0402-RES"))
    )
    (comp (ref "R10")
      (value "45.3K")
      (footprint "eagle-import:0402-RES")
      (libsource (lib "eagle-import") (part "RESISTOR0402-RES"))
    )
    (comp (ref "R11")
      (value "105K")
      (footprint "eagle-import:0402-RES")
      (libsource (lib "eagle-import") (part "RESISTOR0402-RES"))
    )
    (comp (ref "R604")
      (value "10K/0.1%")
      (footprint "eagle-import:0402-RES")
      (fields (field (name "PARTNO") "ERA-2AEB103X"))
      (libsource (lib "eagle-import") (part "RESISTOR0402-RES"))
    )
    (comp (ref "R605")
      (value "10K/0.1%")
      (footprint "eagle-import:0402-RES")
      (fields (field (name "PARTNO") "ERA-2AEB103X"))
      (libsource (lib "eagle-import") (part "RESISTOR0402-RES"))
    )
    (comp (ref "U$2")
      (value "LTC4417")
      (footprint "eagle-import:MO-220")
      (libsource (lib "eagle-import") (part "LTC4117"))
    )
    (comp (ref "U$3")
      (value "NTHD4102P")
      (footprint "eagle-import:1206-8")
      (fields (field (name "PARTNO") "*"))
      (libsource (lib "eagle-import") (part "MOSFET-DUAL-PCHANNEL-CHIPFET"))
    )
    (comp (ref "U$4")
      (value "NTHD4102P")
      (footprint "eagle-import:1206-8")
      (fields (field (name "PARTNO") "*"))
      (libsource (lib "eagle-import") (part "MOSFET-DUAL-PCHANNEL-CHIPFET"))
    )
    (comp (ref "U$5")
      (value "NTHD4102P")
      (footprint "eagle-import:1206-8")
      (fields (field (name "PARTNO") "*"))
      (libsource (lib "eagle-import") (part "MOSFET-DUAL-PCHANNEL-CHIPFET"))
    )
    (comp (ref "C901")
      (value "0u1")
      (footprint "eagle-import:0402-CAP")
      (fields (field (name "PARTNO") "CC0402ZRY5V7BB104"))
      (libsource (lib "eagle-import") (part "CAP0402"))
    )
    (comp (ref "C902")
      (value "0u1")
      (footprint "eagle-import:0402-CAP")
      (fields (field (name "PARTNO") "CC0402ZRY5V7BB104"))
      (libsource (lib "eagle-import") (part "CAP0402"))
    )
    (comp (ref "C903")
      (value "0u1")
      (footprint "eagle-import:0402-CAP")
      (fields (field (name "PARTNO") "CC0402ZRY5V7BB104"))
      (libsource (lib "eagle-import") (part "CAP0402"))
    )
    (comp (ref "D1")
      (value "MSS1P4-M3")
      (footprint "eagle-import:MICROSMP")
      (fields (field (name "PARTNO") "MSS1P4-M3/89A"))
      (libsource (lib "eagle-import") (part "DIODE-SCHOTTKY_MSMP"))
    )
    (comp (ref "J901")
      (value "HEADER-3X163X16RA")
      (footprint "eagle-import:3X16RA")
      (fields (field (name "BOM") "EXCLUDE"))
      (libsource (lib "eagle-import") (part "HEADER-3X163X16RA"))
    )
    (comp (ref "L901")
      (value "KNH16C104DA5TS")
      (footprint "eagle-import:KYOCERA-KNH16-DA")
      (libsource (lib "eagle-import") (part "KNH16C104DA5TS"))
    )
    (comp (ref "R901")
      (value "10K")
      (footprint "eagle-import:0402-RES")
      (fields (field (name "PARTNO") "RC0402FR-0710KL"))
      (libsource (lib "eagle-import") (part "RESISTOR0402-RES"))
    )
    (comp (ref "R902")
      (value "220R")
      (footprint "eagle-import:0402-RES")
      (fields (field (name "PARTNO") "RC0402FR-07220RL"))
      (libsource (lib "eagle-import") (part "RESISTOR0402-RES"))
    )
    (comp (ref "R903")
      (value "220R")
      (footprint "eagle-import:0402-RES")
      (fields (field (name "PARTNO") "RC0402FR-07220RL"))
      (libsource (lib "eagle-import") (part "RESISTOR0402-RES"))
    )
    (comp (ref "R904")
      (value "220R")
      (footprint "eagle-import:0402-RES")
      (fields (field (name "PARTNO") "RC0402FR-07220RL"))
      (libsource (lib "eagle-import") (part "RESISTOR0402-RES"))
    )
    (comp (ref "R905")
      (value "220R")
      (footprint "eagle-import:0402-RES")
      (fields (field (name "PARTNO") "RC0402FR-07220RL"))
      (libsource (lib "eagle-import") (part "RESISTOR0402-RES"))
    )
    (comp (ref "R906")
      (value "220R")
      (footprint "eagle-import:0402-RES")
      (fields (field (name "PARTNO") "RC0402FR-07220RL"))
      (libsource (lib "eagle-import") (part "RESISTOR0402-RES"))
    )
    (comp (ref "R907")
      (value "220R")
      (footprint "eagle-import:0402-RES")
      (fields (field (name "PARTNO") "RC0402FR-07220RL"))
      (libsource (lib "eagle-import") (part "RESISTOR0402-RES"))
    )
    (comp (ref "R908")
      (value "220R")
      (footprint "eagle-import:0402-RES")
      (fields (field (name "PARTNO") "RC0402FR-07220RL"))
      (libsource (lib "eagle-import") (part "RESISTOR0402-RES"))
    )
    (comp (ref "R909")
      (value "220R")
      (footprint "eagle-import:0402-RES")
      (fields (field (name "PARTNO") "RC0402FR-07220RL"))
      (libsource (lib "eagle-import") (part "RESISTOR0402-RES"))
    )
    (comp (ref "R910")
      (value "220R")
      (footprint "eagle-import:0402-RES")
      (fields (field (name "PARTNO") "RC0402FR-07220RL"))
      (libsource (lib "eagle-import") (part "RESISTOR0402-RES"))
    )
    (comp (ref "R911")
      (value "220R")
      (footprint "eagle-import:0402-RES")
      (fields (field (name "PARTNO") "RC0402FR-07220RL"))
      (libsource (lib "eagle-import") (part "RESISTOR0402-RES"))
    )
    (comp (ref "R912")
      (value "220R")
      (footprint "eagle-import:0402-RES")
      (fields (field (name "PARTNO") "RC0402FR-07220RL"))
      (libsource (lib "eagle-import") (part "RESISTOR0402-RES"))
    )
    (comp (ref "R913")
      (value "220R")
      (footprint "eagle-import:0402-RES")
      (fields (field (name "PARTNO") "RC0402FR-07220RL"))
      (libsource (lib "eagle-import") (part "RESISTOR0402-RES"))
    )
    (comp (ref "R914")
      (value "220R")
      (footprint "eagle-import:0402-RES")
      (fields (field (name "PARTNO") "RC0402FR-07220RL"))
      (libsource (lib "eagle-import") (part "RESISTOR0402-RES"))
    )
    (comp (ref "R915")
      (value "220R")
      (footprint "eagle-import:0402-RES")
      (fields (field (name "PARTNO") "RC0402FR-07220RL"))
      (libsource (lib "eagle-import") (part "RESISTOR0402-RES"))
    )
    (comp (ref "R916")
      (value "220R")
      (footprint "eagle-import:0402-RES")
      (fields (field (name "PARTNO") "RC0402FR-07220RL"))
      (libsource (lib "eagle-import") (part "RESISTOR0402-RES"))
    )
    (comp (ref "R917")
      (value "220R")
      (footprint "eagle-import:0402-RES")
      (fields (field (name "PARTNO") "RC0402FR-07220RL"))
      (libsource (lib "eagle-import") (part "RESISTOR0402-RES"))
    )
    (comp (ref "R918")
      (value "10K/0.1%")
      (footprint "eagle-import:0402-RES")
      (fields (field (name "PARTNO") "ERA-2AEB103X"))
      (libsource (lib "eagle-import") (part "RESISTOR0402-RES"))
    )
    (comp (ref "R919")
      (value "10K/0.1%")
      (footprint "eagle-import:0402-RES")
      (fields (field (name "PARTNO") "ERA-2AEB103X"))
      (libsource (lib "eagle-import") (part "RESISTOR0402-RES"))
    )
    (comp (ref "R922")
      (value "10K/0.1%")
      (footprint "eagle-import:0402-RES")
      (fields (field (name "PARTNO") "ERA-2AEB103X"))
      (libsource (lib "eagle-import") (part "RESISTOR0402-RES"))
    )
    (comp (ref "U$6")
      (value "PESD0402-140")
      (footprint "eagle-import:0402-TVS")
      (libsource (lib "eagle-import") (part "DIODE-TVS"))
    )
    (comp (ref "U$901")
      (value "PESD0402-140")
      (footprint "eagle-import:0402-TVS")
      (libsource (lib "eagle-import") (part "DIODE-TVS"))
    )
    (comp (ref "U$902")
      (value "PESD0402-140")
      (footprint "eagle-import:0402-TVS")
      (libsource (lib "eagle-import") (part "DIODE-TVS"))
    )
    (comp (ref "U901")
      (value "TXS0108QFN20")
      (footprint "eagle-import:QFN20-RGY")
      (fields (field (name "PARTNO") "TXS0108ERGYR"))
      (libsource (lib "eagle-import") (part "TXS0108QFN20"))
    )
    (comp (ref "U902")
      (value "TXS0108QFN20")
      (footprint "eagle-import:QFN20-RGY")
      (fields (field (name "PARTNO") "TXS0108ERGYR"))
      (libsource (lib "eagle-import") (part "TXS0108QFN20"))
    )
    (comp (ref "U903")
      (value "74LVC2G240")
      (footprint "eagle-import:TSSOP8_SOT505-2")
      (fields (field (name "PARTNO") "74LVC2G240DP,125"))
      (libsource (lib "eagle-import") (part "74LVC2G240-TSSOP-8"))
    )
    (comp (ref "B601")
      (value "DO NOT PLACE")
      (footprint "eagle-import:MS621FE")
      (fields (field (name "PARTNO") "MS621FE-FL11E"))
      (libsource (lib "eagle-import") (part "MS621FE"))
    )
    (comp (ref "C601")
      (value "2u2")
      (footprint "eagle-import:0603-CAP")
      (fields (field (name "PARTNO") "C1608Y5V1C225Z"))
      (libsource (lib "eagle-import") (part "CAP0603"))
    )
    (comp (ref "C602")
      (value "10n")
      (footprint "eagle-import:0402-CAP")
      (fields (field (name "PARTNO") "CC0402KRX7R7BB103"))
      (libsource (lib "eagle-import") (part "CAP0402"))
    )
    (comp (ref "C603")
      (value "1u0")
      (footprint "eagle-import:0603-CAP")
      (fields (field (name "PARTNO") "CC0603ZRY5V7BB105"))
      (libsource (lib "eagle-import") (part "CAP0603"))
    )
    (comp (ref "C604")
      (value "10u/10V")
      (footprint "eagle-import:0805-CAP")
      (fields (field (name "PARTNO") "CC0805ZKY5V6BB106"))
      (libsource (lib "eagle-import") (part "CAP0805"))
    )
    (comp (ref "C605")
      (value "1u0")
      (footprint "eagle-import:0603-CAP")
      (fields (field (name "PARTNO") "CC0603ZRY5V7BB105"))
      (libsource (lib "eagle-import") (part "CAP0603"))
    )
    (comp (ref "C606")
      (value "0u1")
      (footprint "eagle-import:0402-CAP")
      (fields (field (name "PARTNO") "CC0402ZRY5V7BB104"))
      (libsource (lib "eagle-import") (part "CAP0402"))
    )
    (comp (ref "C607")
      (value "0u1")
      (footprint "eagle-import:0402-CAP")
      (fields (field (name "PARTNO") "CC0402ZRY5V7BB104"))
      (libsource (lib "eagle-import") (part "CAP0402"))
    )
    (comp (ref "C608")
      (value "0u1")
      (footprint "eagle-import:0402-CAP")
      (fields (field (name "PARTNO") "CC0402ZRY5V7BB104"))
      (libsource (lib "eagle-import") (part "CAP0402"))
    )
    (comp (ref "C609")
      (value "0u1")
      (footprint "eagle-import:0402-CAP")
      (fields (field (name "PARTNO") "CC0402ZRY5V7BB104"))
      (libsource (lib "eagle-import") (part "CAP0402"))
    )
    (comp (ref "C610")
      (value "0u1")
      (footprint "eagle-import:0402-CAP")
      (fields (field (name "PARTNO") "CC0402ZRY5V7BB104"))
      (libsource (lib "eagle-import") (part "CAP0402"))
    )
    (comp (ref "C611")
      (value "2u2")
      (footprint "eagle-import:0603-CAP")
      (fields (field (name "PARTNO") "C1608Y5V1C225Z"))
      (libsource (lib "eagle-import") (part "CAP0603"))
    )
    (comp (ref "C612")
      (value "0u1")
      (footprint "eagle-import:0402-CAP")
      (fields (field (name "PARTNO") "CC0402ZRY5V7BB104"))
      (libsource (lib "eagle-import") (part "CAP0402"))
    )
    (comp (ref "C613")
      (value "2u2")
      (footprint "eagle-import:0603-CAP")
      (fields (field (name "PARTNO") "C1608Y5V1C225Z"))
      (libsource (lib "eagle-import") (part "CAP0603"))
    )
    (comp (ref "L603")
      (value "KNH16C104DA5TS")
      (footprint "eagle-import:KYOCERA-KNH16-DA")
      (libsource (lib "eagle-import") (part "KNH16C104DA5TS"))
    )
    (comp (ref "R602")
      (value "16K5")
      (footprint "eagle-import:0402-RES")
      (fields (field (name "PARTNO") "RMCF0402FT16K5"))
      (libsource (lib "eagle-import") (part "RESISTOR0402-RES"))
    )
    (comp (ref "R603")
      (value "10K")
      (footprint "eagle-import:0402-RES")
      (fields (field (name "PARTNO") "RC0402FR-0710KL"))
      (libsource (lib "eagle-import") (part "RESISTOR0402-RES"))
    )
    (comp (ref "R606")
      (value "25K")
      (footprint "eagle-import:0402-RES")
      (fields (field (name "PARTNO") "RMCF0402FT25K5"))
      (libsource (lib "eagle-import") (part "RESISTOR0402-RES"))
    )
    (comp (ref "R607")
      (value "10K")
      (footprint "eagle-import:0402-RES")
      (fields (field (name "PARTNO") "RC0402FR-0710KL"))
      (libsource (lib "eagle-import") (part "RESISTOR0402-RES"))
    )
    (comp (ref "R608")
      (value "1K")
      (footprint "eagle-import:0402-RES")
      (fields (field (name "PARTNO") "RC0402FR-071KL"))
      (libsource (lib "eagle-import") (part "RESISTOR0402-RES"))
    )
    (comp (ref "R609")
      (value "10K/0.1%")
      (footprint "eagle-import:0402-RES")
      (fields (field (name "PARTNO") "ERA-2AEB103X"))
      (libsource (lib "eagle-import") (part "RESISTOR0402-RES"))
    )
    (comp (ref "R610")
      (value "10K/0.1%")
      (footprint "eagle-import:0402-RES")
      (fields (field (name "PARTNO") "ERA-2AEB103X"))
      (libsource (lib "eagle-import") (part "RESISTOR0402-RES"))
    )
    (comp (ref "R611")
      (value "10K")
      (footprint "eagle-import:0402-RES")
      (fields (field (name "PARTNO") "RC0402FR-0710KL"))
      (libsource (lib "eagle-import") (part "RESISTOR0402-RES"))
    )
    (comp (ref "S601")
      (value "RESET")
      (footprint "eagle-import:EVQP7J01K")
      (fields (field (name "PARTNO") "EVQP7J01K"))
      (libsource (lib "eagle-import") (part "SWITCH-MOMENTARY-2"))
    )
    (comp (ref "U$602")
      (value "BQ24315")
      (footprint "eagle-import:QFN8-DSG")
      (fields (field (name "PARTNO") "BQ24315DSGR"))
      (libsource (lib "eagle-import") (part "BQ24315"))
    )
    (comp (ref "U$604")
      (value "BQ24315")
      (footprint "eagle-import:QFN8-DSG")
      (fields (field (name "PARTNO") "BQ24315DSGR"))
      (libsource (lib "eagle-import") (part "BQ24315"))
    )
    (comp (ref "U$605")
      (value "MIC5332")
      (footprint "eagle-import:MLF-8-EPAD")
      (fields (field (name "PARTNO") "MIC5332-SSYMT"))
      (libsource (lib "eagle-import") (part "MIC5332"))
    )
    (comp (ref "U101")
      (value "STM32F4X7VX")
      (footprint "eagle-import:TQFP100")
      (fields (field (name "PARTNO") "STM32F427VI"))
      (libsource (lib "eagle-import") (part "STM32F4X7VX"))
    )
    (comp (ref "ADC_PR")
      (value "PAD.04")
      (footprint "eagle-import:PAD.04X.04")
      (libsource (lib "eagle-import") (part "PAD.04"))
    )
    (comp (ref "CAN_H")
      (value "PAD.04")
      (footprint "eagle-import:PAD.04X.04")
      (libsource (lib "eagle-import") (part "PAD.04"))
    )
    (comp (ref "CAN_L")
      (value "PAD.04")
      (footprint "eagle-import:PAD.04X.04")
      (libsource (lib "eagle-import") (part "PAD.04"))
    )
    (comp (ref "FMU-BOOT1101")
      (value "PAD.04")
      (footprint "eagle-import:PAD.04X.04")
      (libsource (lib "eagle-import") (part "PAD.04"))
    )
    (comp (ref "GND")
      (value "PAD.04")
      (footprint "eagle-import:PAD.04X.04")
      (libsource (lib "eagle-import") (part "PAD.04"))
    )
    (comp (ref "GND.")
      (value "PAD.04")
      (footprint "eagle-import:PAD.04X.04")
      (libsource (lib "eagle-import") (part "PAD.04"))
    )
    (comp (ref "IO-BOOT1101")
      (value "PAD.04")
      (footprint "eagle-import:PAD.04X.04")
      (libsource (lib "eagle-import") (part "PAD.04"))
    )
    (comp (ref "JP1")
      (value "FIDUCIAL1.5X3")
      (footprint "eagle-import:FIDUCIAL-1.5X3")
      (libsource (lib "eagle-import") (part "FIDUCIAL1.5X3"))
    )
    (comp (ref "JP2")
      (value "FIDUCIAL1.5X3")
      (footprint "eagle-import:FIDUCIAL-1.5X3")
      (libsource (lib "eagle-import") (part "FIDUCIAL1.5X3"))
    )
    (comp (ref "M3_MOUNT1101")
      (value "MOUNT-HOLE3.1MM")
      (footprint "eagle-import:MOUNT-HOLE3.1")
      (libsource (lib "eagle-import") (part "MOUNT-HOLE3.1MM"))
    )
    (comp (ref "M3_MOUNT1102")
      (value "MOUNT-HOLE3.1MM")
      (footprint "eagle-import:MOUNT-HOLE3.1")
      (libsource (lib "eagle-import") (part "MOUNT-HOLE3.1MM"))
    )
    (comp (ref "M3_MOUNT1103")
      (value "MOUNT-HOLE3.1MM")
      (footprint "eagle-import:MOUNT-HOLE3.1")
      (libsource (lib "eagle-import") (part "MOUNT-HOLE3.1MM"))
    )
    (comp (ref "M3_MOUNT1104")
      (value "MOUNT-HOLE3.1MM")
      (footprint "eagle-import:MOUNT-HOLE3.1")
      (libsource (lib "eagle-import") (part "MOUNT-HOLE3.1MM"))
    )
    (comp (ref "OSHW_LOGO")
      (value "OSHW-LOGOS")
      (footprint "eagle-import:OSHW-LOGO-S")
      (libsource (lib "eagle-import") (part "OSHW-LOGOS"))
    )
    (comp (ref "S1RX")
      (value "PAD.04")
      (footprint "eagle-import:PAD.04X.04")
      (libsource (lib "eagle-import") (part "PAD.04"))
    )
    (comp (ref "S1TX")
      (value "PAD.04")
      (footprint "eagle-import:PAD.04X.04")
      (libsource (lib "eagle-import") (part "PAD.04"))
    )
    (comp (ref "S2RX")
      (value "PAD.04")
      (footprint "eagle-import:PAD.04X.04")
      (libsource (lib "eagle-import") (part "PAD.04"))
    )
    (comp (ref "S2TX")
      (value "PAD.04")
      (footprint "eagle-import:PAD.04X.04")
      (libsource (lib "eagle-import") (part "PAD.04"))
    )
    (comp (ref "S3RX")
      (value "PAD.04")
      (footprint "eagle-import:PAD.04X.04")
      (libsource (lib "eagle-import") (part "PAD.04"))
    )
    (comp (ref "S3TX")
      (value "PAD.04")
      (footprint "eagle-import:PAD.04X.04")
      (libsource (lib "eagle-import") (part "PAD.04"))
    )
    (comp (ref "S4RX")
      (value "PAD.04")
      (footprint "eagle-import:PAD.04X.04")
      (libsource (lib "eagle-import") (part "PAD.04"))
    )
    (comp (ref "S4TX")
      (value "PAD.04")
      (footprint "eagle-import:PAD.04X.04")
      (libsource (lib "eagle-import") (part "PAD.04"))
    )
    (comp (ref "S5_RX")
      (value "PAD.04")
      (footprint "eagle-import:PAD.04X.04")
      (libsource (lib "eagle-import") (part "PAD.04"))
    )
    (comp (ref "S5_TX")
      (value "PAD.04")
      (footprint "eagle-import:PAD.04X.04")
      (libsource (lib "eagle-import") (part "PAD.04"))
    )
    (comp (ref "VDDA_3V1101")
      (value "PAD.04")
      (footprint "eagle-import:PAD.04X.04")
      (libsource (lib "eagle-import") (part "PAD.04"))
    )
    (comp (ref "VDD_3V1101")
      (value "PAD.04")
      (footprint "eagle-import:PAD.04X.04")
      (libsource (lib "eagle-import") (part "PAD.04"))
    )
    (comp (ref "VDD_5V_BRICK")
      (value "PAD.04")
      (footprint "eagle-import:PAD.04X.04")
      (libsource (lib "eagle-import") (part "PAD.04"))
    )
    (comp (ref "J301")
      (value "47346-0001")
      (footprint "eagle-import:MOLEX-47346-0001")
      (libsource (lib "eagle-import") (part "MOLEX-47346-0001"))
    )
    (comp (ref "J302")
      (value "DF13C-4P-1.25V")
      (footprint "eagle-import:DF13C-4P-1.25V")
      (fields (field (name "PARTNO") "DF13C-4P-1.25V(20)"))
      (libsource (lib "eagle-import") (part "DF13-4P-1.25V"))
    )
    (comp (ref "JX301")
      (value "ARM_MINI_JTAG-SMT")
      (footprint "eagle-import:FTSH-105-01-XXX-DV-K")
      (fields (field (name "BOM") "EXCLUDE") (field (name "PARTNO") "M50-3900542"))
      (libsource (lib "eagle-import") (part "ARM_MINI_JTAG-SMT"))
    )
    (comp (ref "R301")
      (value "100K")
      (footprint "eagle-import:0402-RES")
      (fields (field (name "PARTNO") "RC0402FR-07100KL"))
      (libsource (lib "eagle-import") (part "RESISTOR0402-RES"))
    )
    (comp (ref "R302")
      (value "100K")
      (footprint "eagle-import:0402-RES")
      (fields (field (name "PARTNO") "RC0402FR-07100KL"))
      (libsource (lib "eagle-import") (part "RESISTOR0402-RES"))
    )
    (comp (ref "R303")
      (value "100K")
      (footprint "eagle-import:0402-RES")
      (fields (field (name "PARTNO") "RC0402FR-07100KL"))
      (libsource (lib "eagle-import") (part "RESISTOR0402-RES"))
    )
    (comp (ref "R304")
      (value "100K")
      (footprint "eagle-import:0402-RES")
      (fields (field (name "PARTNO") "RC0402FR-07100KL"))
      (libsource (lib "eagle-import") (part "RESISTOR0402-RES"))
    )
    (comp (ref "R305")
      (value "100K")
      (footprint "eagle-import:0402-RES")
      (fields (field (name "PARTNO") "RC0402FR-07100KL"))
      (libsource (lib "eagle-import") (part "RESISTOR0402-RES"))
    )
    (comp (ref "R306")
      (value "1K5")
      (footprint "eagle-import:0402-RES")
      (fields (field (name "PARTNO") "RC0402FR-071K5L"))
      (libsource (lib "eagle-import") (part "RESISTOR0402-RES"))
    )
    (comp (ref "R307")
      (value "1K5")
      (footprint "eagle-import:0402-RES")
      (fields (field (name "PARTNO") "RC0402FR-071K5L"))
      (libsource (lib "eagle-import") (part "RESISTOR0402-RES"))
    )
    (comp (ref "U$301")
      (value "NUF2042XV6")
      (footprint "eagle-import:SOT563-6")
      (fields (field (name "PARTNO") "NUF2042XV6T1G"))
      (libsource (lib "eagle-import") (part "NUF2042XV6"))
    )
    (comp (ref "U301")
      (value "2908-05WB-MG")
      (footprint "eagle-import:MICROSD")
      (libsource (lib "eagle-import") (part "MICROSDSDI"))
    )
    (comp (ref "C101")
      (value "0u1")
      (footprint "eagle-import:0402-CAP")
      (fields (field (name "PARTNO") "CC0402ZRY5V7BB104"))
      (libsource (lib "eagle-import") (part "CAP0402"))
    )
    (comp (ref "C102")
      (value "8p")
      (footprint "eagle-import:0402-CAP")
      (fields (field (name "PARTNO") "C1005C0G1H080C"))
      (libsource (lib "eagle-import") (part "CAP0402"))
    )
    (comp (ref "C103")
      (value "8p")
      (footprint "eagle-import:0402-CAP")
      (fields (field (name "PARTNO") "C1005C0G1H080C"))
      (libsource (lib "eagle-import") (part "CAP0402"))
    )
    (comp (ref "R101")
      (value "470R")
      (footprint "eagle-import:0402-RES")
      (fields (field (name "PARTNO") "RC0402FR-07470RL"))
      (libsource (lib "eagle-import") (part "RESISTOR0402-RES"))
    )
    (comp (ref "R102")
      (value "10K")
      (footprint "eagle-import:0402-RES")
      (fields (field (name "PARTNO") "RC0402FR-0710KL"))
      (libsource (lib "eagle-import") (part "RESISTOR0402-RES"))
    )
    (comp (ref "U102")
      (value "FM25V01")
      (footprint "eagle-import:SO08")
      (fields (field (name "PARTNO") "FM25V01-G"))
      (libsource (lib "eagle-import") (part "FM25V01"))
    )
    (comp (ref "X101")
      (value "3.2x2.5 mm / 24 MHz / 15 ppm")
      (footprint "eagle-import:OSCILLATOR-3.2X2.5")
      (fields (field (name "PARTNO") "NX3225SA-24.000000MHZ"))
      (libsource (lib "eagle-import") (part "OSCILLATOR-3.2X2.5"))
    )
    (comp (ref "C201")
      (value "0u1")
      (footprint "eagle-import:0402-CAP")
      (fields (field (name "PARTNO") "CC0402ZRY5V7BB104"))
      (libsource (lib "eagle-import") (part "CAP0402"))
    )
    (comp (ref "C202")
      (value "0u1")
      (footprint "eagle-import:0402-CAP")
      (fields (field (name "PARTNO") "CC0402ZRY5V7BB104"))
      (libsource (lib "eagle-import") (part "CAP0402"))
    )
    (comp (ref "J201")
      (value "DF13C-6P-1.25V")
      (footprint "eagle-import:DF13C-6P-1.25V")
      (fields (field (name "PARTNO") "DF13C-6P-1.25V(20)"))
      (libsource (lib "eagle-import") (part "DF13-6P-1.25V"))
    )
    (comp (ref "J202")
      (value "DF13C-6P-1.25V")
      (footprint "eagle-import:DF13C-6P-1.25V")
      (fields (field (name "PARTNO") "DF13C-6P-1.25V(20)"))
      (libsource (lib "eagle-import") (part "DF13-6P-1.25V"))
    )
    (comp (ref "J203")
      (value "DF13C-6P-1.25V")
      (footprint "eagle-import:DF13C-6P-1.25V")
      (fields (field (name "PARTNO") "DF13C-6P-1.25V(20)"))
      (libsource (lib "eagle-import") (part "DF13-6P-1.25V"))
    )
    (comp (ref "J204")
      (value "DF13C-6P-1.25V")
      (footprint "eagle-import:DF13C-6P-1.25V")
      (fields (field (name "PARTNO") "DF13C-6P-1.25V(20)"))
      (libsource (lib "eagle-import") (part "DF13-6P-1.25V"))
    )
    (comp (ref "L201")
      (value "KNH16C104DA5TS")
      (footprint "eagle-import:KYOCERA-KNH16-DA")
      (libsource (lib "eagle-import") (part "KNH16C104DA5TS"))
    )
    (comp (ref "L202")
      (value "KNH16C104DA5TS")
      (footprint "eagle-import:KYOCERA-KNH16-DA")
      (libsource (lib "eagle-import") (part "KNH16C104DA5TS"))
    )
    (comp (ref "L203")
      (value "KNH16C104DA5TS")
      (footprint "eagle-import:KYOCERA-KNH16-DA")
      (libsource (lib "eagle-import") (part "KNH16C104DA5TS"))
    )
    (comp (ref "R12")
      (value "120R")
      (footprint "eagle-import:0402-RES")
      (fields (field (name "PARTNO") "RC0402FR-07120RL"))
      (libsource (lib "eagle-import") (part "RESISTOR0402-RES"))
    )
    (comp (ref "R13")
      (value "120R")
      (footprint "eagle-import:0402-RES")
      (fields (field (name "PARTNO") "RC0402FR-07120RL"))
      (libsource (lib "eagle-import") (part "RESISTOR0402-RES"))
    )
    (comp (ref "R201")
      (value "120R")
      (footprint "eagle-import:0402-RES")
      (fields (field (name "PARTNO") "RC0402FR-07120RL"))
      (libsource (lib "eagle-import") (part "RESISTOR0402-RES"))
    )
    (comp (ref "R202")
      (value "120R")
      (footprint "eagle-import:0402-RES")
      (fields (field (name "PARTNO") "RC0402FR-07120RL"))
      (libsource (lib "eagle-import") (part "RESISTOR0402-RES"))
    )
    (comp (ref "R203")
      (value "120R")
      (footprint "eagle-import:0402-RES")
      (fields (field (name "PARTNO") "RC0402FR-07120RL"))
      (libsource (lib "eagle-import") (part "RESISTOR0402-RES"))
    )
    (comp (ref "R204")
      (value "120R")
      (footprint "eagle-import:0402-RES")
      (fields (field (name "PARTNO") "RC0402FR-07120RL"))
      (libsource (lib "eagle-import") (part "RESISTOR0402-RES"))
    )
    (comp (ref "R205")
      (value "120R")
      (footprint "eagle-import:0402-RES")
      (fields (field (name "PARTNO") "RC0402FR-07120RL"))
      (libsource (lib "eagle-import") (part "RESISTOR0402-RES"))
    )
    (comp (ref "R206")
      (value "120R")
      (footprint "eagle-import:0402-RES")
      (fields (field (name "PARTNO") "RC0402FR-07120RL"))
      (libsource (lib "eagle-import") (part "RESISTOR0402-RES"))
    )
    (comp (ref "R207")
      (value "120R")
      (footprint "eagle-import:0402-RES")
      (fields (field (name "PARTNO") "RC0402FR-07120RL"))
      (libsource (lib "eagle-import") (part "RESISTOR0402-RES"))
    )
    (comp (ref "R208")
      (value "120R")
      (footprint "eagle-import:0402-RES")
      (fields (field (name "PARTNO") "RC0402FR-07120RL"))
      (libsource (lib "eagle-import") (part "RESISTOR0402-RES"))
    )
    (comp (ref "R209")
      (value "120R")
      (footprint "eagle-import:0402-RES")
      (fields (field (name "PARTNO") "RC0402FR-07120RL"))
      (libsource (lib "eagle-import") (part "RESISTOR0402-RES"))
    )
    (comp (ref "R210")
      (value "120R")
      (footprint "eagle-import:0402-RES")
      (fields (field (name "PARTNO") "RC0402FR-07120RL"))
      (libsource (lib "eagle-import") (part "RESISTOR0402-RES"))
    )
    (comp (ref "R211")
      (value "120R")
      (footprint "eagle-import:0402-RES")
      (fields (field (name "PARTNO") "RC0402FR-07120RL"))
      (libsource (lib "eagle-import") (part "RESISTOR0402-RES"))
    )
    (comp (ref "R212")
      (value "120R")
      (footprint "eagle-import:0402-RES")
      (fields (field (name "PARTNO") "RC0402FR-07120RL"))
      (libsource (lib "eagle-import") (part "RESISTOR0402-RES"))
    )
    (comp (ref "R213")
      (value "120R")
      (footprint "eagle-import:0402-RES")
      (fields (field (name "PARTNO") "RC0402FR-07120RL"))
      (libsource (lib "eagle-import") (part "RESISTOR0402-RES"))
    )
    (comp (ref "R214")
      (value "120R")
      (footprint "eagle-import:0402-RES")
      (fields (field (name "PARTNO") "RC0402FR-07120RL"))
      (libsource (lib "eagle-import") (part "RESISTOR0402-RES"))
    )
    (comp (ref "U$201")
      (value "PESD0402-140")
      (footprint "eagle-import:0402-TVS")
      (libsource (lib "eagle-import") (part "DIODE-TVS"))
    )
    (comp (ref "U$202")
      (value "PESD0402-140")
      (footprint "eagle-import:0402-TVS")
      (libsource (lib "eagle-import") (part "DIODE-TVS"))
    )
    (comp (ref "U$203")
      (value "PESD0402-140")
      (footprint "eagle-import:0402-TVS")
      (libsource (lib "eagle-import") (part "DIODE-TVS"))
    )
    (comp (ref "U201")
      (value "TXS0108QFN20")
      (footprint "eagle-import:QFN20-RGY")
      (fields (field (name "PARTNO") "TXS0108ERGYR"))
      (libsource (lib "eagle-import") (part "TXS0108QFN20"))
    )
    (comp (ref "U202")
      (value "TXS0108QFN20")
      (footprint "eagle-import:QFN20-RGY")
      (fields (field (name "PARTNO") "TXS0108ERGYR"))
      (libsource (lib "eagle-import") (part "TXS0108QFN20"))
    )
    (comp (ref "C401")
      (value "0u1")
      (footprint "eagle-import:0402-CAP")
      (fields (field (name "PARTNO") "CC0402ZRY5V7BB104"))
      (libsource (lib "eagle-import") (part "CAP0402"))
    )
    (comp (ref "C402")
      (value "0u1")
      (footprint "eagle-import:0402-CAP")
      (fields (field (name "PARTNO") "CC0402ZRY5V7BB104"))
      (libsource (lib "eagle-import") (part "CAP0402"))
    )
    (comp (ref "J401")
      (value "DF13C-4P-1.25V")
      (footprint "eagle-import:DF13C-4P-1.25V")
      (fields (field (name "PARTNO") "DF13C-4P-1.25V(20)"))
      (libsource (lib "eagle-import") (part "DF13-4P-1.25V"))
    )
    (comp (ref "J402")
      (value "DF13C-3P-1.25V")
      (footprint "eagle-import:DF13C-3P-1.25V")
      (fields (field (name "PARTNO") "DF13C-3P-1.25V(20)"))
      (libsource (lib "eagle-import") (part "DF13-3P-1.25V"))
    )
    (comp (ref "J403")
      (value "DF13C-7P-1.25V")
      (footprint "eagle-import:DF13C-7P-1.25V")
      (fields (field (name "PARTNO") "DF13C-7P-1.25V(20)"))
      (libsource (lib "eagle-import") (part "DF13-7P-1.25V"))
    )
    (comp (ref "J404")
      (value "DF13C-5P-1.25V")
      (footprint "eagle-import:DF13C-5P-1.25V")
      (fields (field (name "PARTNO") "DF13C-5P-1.25V(20)"))
      (libsource (lib "eagle-import") (part "DF13-5P-1.25V"))
    )
    (comp (ref "J405")
      (value "DF13C-4P-1.25V")
      (footprint "eagle-import:DF13C-4P-1.25V")
      (fields (field (name "PARTNO") "DF13C-4P-1.25V(20)"))
      (libsource (lib "eagle-import") (part "DF13-4P-1.25V"))
    )
    (comp (ref "L401")
      (value "KNH16C104DA5TS")
      (footprint "eagle-import:KYOCERA-KNH16-DA")
      (libsource (lib "eagle-import") (part "KNH16C104DA5TS"))
    )
    (comp (ref "L402")
      (value "KNH16C104DA5TS")
      (footprint "eagle-import:KYOCERA-KNH16-DA")
      (libsource (lib "eagle-import") (part "KNH16C104DA5TS"))
    )
    (comp (ref "L403")
      (value "KNH16C104DA5TS")
      (footprint "eagle-import:KYOCERA-KNH16-DA")
      (libsource (lib "eagle-import") (part "KNH16C104DA5TS"))
    )
    (comp (ref "L404")
      (value "KNH16C104DA5TS")
      (footprint "eagle-import:KYOCERA-KNH16-DA")
      (libsource (lib "eagle-import") (part "KNH16C104DA5TS"))
    )
    (comp (ref "R401")
      (value "1K5")
      (footprint "eagle-import:0402-RES")
      (fields (field (name "PARTNO") "RC0402FR-071K5L"))
      (libsource (lib "eagle-import") (part "RESISTOR0402-RES"))
    )
    (comp (ref "R402")
      (value "1K5")
      (footprint "eagle-import:0402-RES")
      (fields (field (name "PARTNO") "RC0402FR-071K5L"))
      (libsource (lib "eagle-import") (part "RESISTOR0402-RES"))
    )
    (comp (ref "R403")
      (value "10K/0.1%")
      (footprint "eagle-import:0402-RES")
      (fields (field (name "PARTNO") "ERA-2AEB103X"))
      (libsource (lib "eagle-import") (part "RESISTOR0402-RES"))
    )
    (comp (ref "R404")
      (value "120R")
      (footprint "eagle-import:0402-RES")
      (fields (field (name "PARTNO") "RC0402FR-07120RL"))
      (libsource (lib "eagle-import") (part "RESISTOR0402-RES"))
    )
    (comp (ref "R405")
      (value "120R")
      (footprint "eagle-import:0402-RES")
      (fields (field (name "PARTNO") "RC0402FR-07120RL"))
      (libsource (lib "eagle-import") (part "RESISTOR0402-RES"))
    )
    (comp (ref "R406")
      (value "10K/0.1%")
      (footprint "eagle-import:0402-RES")
      (fields (field (name "PARTNO") "ERA-2AEB103X"))
      (libsource (lib "eagle-import") (part "RESISTOR0402-RES"))
    )
    (comp (ref "R407")
      (value "10K/0.1%")
      (footprint "eagle-import:0402-RES")
      (fields (field (name "PARTNO") "ERA-2AEB103X"))
      (libsource (lib "eagle-import") (part "RESISTOR0402-RES"))
    )
    (comp (ref "R408")
      (value "10K/0.1%")
      (footprint "eagle-import:0402-RES")
      (fields (field (name "PARTNO") "ERA-2AEB103X"))
      (libsource (lib "eagle-import") (part "RESISTOR0402-RES"))
    )
    (comp (ref "R409")
      (value "120R")
      (footprint "eagle-import:0402-RES")
      (fields (field (name "PARTNO") "RC0402FR-07120RL"))
      (libsource (lib "eagle-import") (part "RESISTOR0402-RES"))
    )
    (comp (ref "U$401")
      (value "PESD0402-140")
      (footprint "eagle-import:0402-TVS")
      (libsource (lib "eagle-import") (part "DIODE-TVS"))
    )
    (comp (ref "U$402")
      (value "PESD0402-140")
      (footprint "eagle-import:0402-TVS")
      (libsource (lib "eagle-import") (part "DIODE-TVS"))
    )
    (comp (ref "U$403")
      (value "PESD0402-140")
      (footprint "eagle-import:0402-TVS")
      (libsource (lib "eagle-import") (part "DIODE-TVS"))
    )
    (comp (ref "U$404")
      (value "PESD0402-140")
      (footprint "eagle-import:0402-TVS")
      (libsource (lib "eagle-import") (part "DIODE-TVS"))
    )
    (comp (ref "U401")
      (value "MAX3051")
      (footprint "eagle-import:SOT23-8")
      (fields (field (name "PARTNO") "MAX3051EKA"))
      (libsource (lib "eagle-import") (part "MAX3051MAX3051EKA"))
    )
    (comp (ref "C501")
      (value "10u/10V")
      (footprint "eagle-import:0805-CAP")
      (fields (field (name "PARTNO") "CC0805ZKY5V6BB106"))
      (libsource (lib "eagle-import") (part "CAP0805"))
    )
    (comp (ref "C502")
      (value "0u1")
      (footprint "eagle-import:0402-CAP")
      (fields (field (name "PARTNO") "CC0402ZRY5V7BB104"))
      (libsource (lib "eagle-import") (part "CAP0402"))
    )
    (comp (ref "C503")
      (value "0u1")
      (footprint "eagle-import:0402-CAP")
      (fields (field (name "PARTNO") "CC0402ZRY5V7BB104"))
      (libsource (lib "eagle-import") (part "CAP0402"))
    )
    (comp (ref "C504")
      (value "10n")
      (footprint "eagle-import:0402-CAP")
      (fields (field (name "PARTNO") "CC0402KRX7R7BB103"))
      (libsource (lib "eagle-import") (part "CAP0402"))
    )
    (comp (ref "C505")
      (value "10n")
      (footprint "eagle-import:0402-CAP")
      (fields (field (name "PARTNO") "CC0402KRX7R7BB103"))
      (libsource (lib "eagle-import") (part "CAP0402"))
    )
    (comp (ref "C506")
      (value "10u/10V")
      (footprint "eagle-import:0805-CAP")
      (fields (field (name "PARTNO") "CC0805ZKY5V6BB106"))
      (libsource (lib "eagle-import") (part "CAP0805"))
    )
    (comp (ref "C507")
      (value "0u1")
      (footprint "eagle-import:0402-CAP")
      (fields (field (name "PARTNO") "CC0402ZRY5V7BB104"))
      (libsource (lib "eagle-import") (part "CAP0402"))
    )
    (comp (ref "C508")
      (value "0u1")
      (footprint "eagle-import:0402-CAP")
      (fields (field (name "PARTNO") "CC0402ZRY5V7BB104"))
      (libsource (lib "eagle-import") (part "CAP0402"))
    )
    (comp (ref "C509")
      (value "10u/10V")
      (footprint "eagle-import:0805-CAP")
      (fields (field (name "PARTNO") "CC0805ZKY5V6BB106"))
      (libsource (lib "eagle-import") (part "CAP0805"))
    )
    (comp (ref "C510")
      (value "0u47")
      (footprint "eagle-import:0402-CAP")
      (fields (field (name "PARTNO") "C1005X5R1C474K050BC"))
      (libsource (lib "eagle-import") (part "CAP0402"))
    )
    (comp (ref "U$1")
      (value "0512811094")
      (footprint "eagle-import:51281-1094")
      (fields (field (name "PARTNO") "0781191109"))
      (libsource (lib "eagle-import") (part "CONN_FPC_10RA"))
    )
    (comp (ref "U$501")
      (value "LSM303D")
      (footprint "eagle-import:LGA-16L")
      (libsource (lib "eagle-import") (part "LSM303D"))
    )
    (comp (ref "U501")
      (value "L3GD20")
      (footprint "eagle-import:L3G4200DH-MAN")
      (libsource (lib "eagle-import") (part "L3G4200DH-LL"))
    )
    (comp (ref "U502")
      (value "L3GD20H")
      (footprint "eagle-import:LGA-16L")
      (libsource (lib "eagle-import") (part "L3GD20H"))
    )
    (comp (ref "U503")
      (value "MS5611-01BA")
      (footprint "eagle-import:MS5611-01BA")
      (libsource (lib "eagle-import") (part "MS5611-01BA"))
    )
    (comp (ref "C801")
      (value "0u1")
      (footprint "eagle-import:0402-CAP")
      (fields (field (name "PARTNO") "CC0402ZRY5V7BB104"))
      (libsource (lib "eagle-import") (part "CAP0402"))
    )
    (comp (ref "C802")
      (value "0u1")
      (footprint "eagle-import:0402-CAP")
      (fields (field (name "PARTNO") "CC0402ZRY5V7BB104"))
      (libsource (lib "eagle-import") (part "CAP0402"))
    )
    (comp (ref "C803")
      (value "0u1")
      (footprint "eagle-import:0402-CAP")
      (fields (field (name "PARTNO") "CC0402ZRY5V7BB104"))
      (libsource (lib "eagle-import") (part "CAP0402"))
    )
    (comp (ref "C804")
      (value "0u1")
      (footprint "eagle-import:0402-CAP")
      (fields (field (name "PARTNO") "CC0402ZRY5V7BB104"))
      (libsource (lib "eagle-import") (part "CAP0402"))
    )
    (comp (ref "C805")
      (value "8p")
      (footprint "eagle-import:0402-CAP")
      (fields (field (name "PARTNO") "C1005C0G1H080C"))
      (libsource (lib "eagle-import") (part "CAP0402"))
    )
    (comp (ref "C806")
      (value "8p")
      (footprint "eagle-import:0402-CAP")
      (fields (field (name "PARTNO") "C1005C0G1H080C"))
      (libsource (lib "eagle-import") (part "CAP0402"))
    )
    (comp (ref "J801")
      (value "JST-ZH-3")
      (footprint "eagle-import:JST-ZH-SMT-VERTICAL")
      (fields (field (name "PARTNO") "B3B-ZR-SM4-TF (LF)(SN)(P)"))
      (libsource (lib "eagle-import") (part "JST-ZH-3"))
    )
    (comp (ref "JX801")
      (value "HEADER-3X1BOARDEDGE-SHORT")
      (footprint "eagle-import:HEADER_3X01_SMD_H_BOARD_EDGE_SHORT")
      (libsource (lib "eagle-import") (part "HEADER-3X1BOARDEDGE-SHORT"))
    )
    (comp (ref "JX802")
      (value "ARM_MINI_JTAG-SMT")
      (footprint "eagle-import:FTSH-105-01-XXX-DV-K")
      (fields (field (name "BOM") "EXCLUDE") (field (name "PARTNO") "M50-3900542"))
      (libsource (lib "eagle-import") (part "ARM_MINI_JTAG-SMT"))
    )
    (comp (ref "R801")
      (value "10K")
      (footprint "eagle-import:0402-RES")
      (fields (field (name "PARTNO") "RC0402FR-0710KL"))
      (libsource (lib "eagle-import") (part "RESISTOR0402-RES"))
    )
    (comp (ref "R802")
      (value "10K")
      (footprint "eagle-import:0402-RES")
      (fields (field (name "PARTNO") "RC0402FR-0710KL"))
      (libsource (lib "eagle-import") (part "RESISTOR0402-RES"))
    )
    (comp (ref "R803")
      (value "220R")
      (footprint "eagle-import:0402-RES")
      (fields (field (name "PARTNO") "RC0402FR-07220RL"))
      (libsource (lib "eagle-import") (part "RESISTOR0402-RES"))
    )
    (comp (ref "R804")
      (value "220R")
      (footprint "eagle-import:0402-RES")
      (fields (field (name "PARTNO") "RC0402FR-07220RL"))
      (libsource (lib "eagle-import") (part "RESISTOR0402-RES"))
    )
    (comp (ref "S801")
      (value "RESET")
      (footprint "eagle-import:EVQP7J01K")
      (fields (field (name "PARTNO") "EVQP7J01K"))
      (libsource (lib "eagle-import") (part "SWITCH-MOMENTARY-2"))
    )
    (comp (ref "U$801")
      (value "PESD0402-140")
      (footprint "eagle-import:0402-TVS")
      (libsource (lib "eagle-import") (part "DIODE-TVS"))
    )
    (comp (ref "U801")
      (value "STM32F10XCXT6")
      (footprint "eagle-import:TQFP48")
      (fields (field (name "PARTNO") "STM32F100C8T6B"))
      (libsource (lib "eagle-import") (part "STM32F10XCXT6"))
    )
    (comp (ref "X801")
      (value "3.2x2.5 mm / 24 MHz / 15 ppm")
      (footprint "eagle-import:OSCILLATOR-3.2X2.5")
      (fields (field (name "PARTNO") "NX3225SA-24.000000MHZ"))
      (libsource (lib "eagle-import") (part "OSCILLATOR-3.2X2.5"))
    )
    (comp (ref "C701")
      (value "0u1")
      (footprint "eagle-import:0402-CAP")
      (fields (field (name "PARTNO") "CC0402ZRY5V7BB104"))
      (libsource (lib "eagle-import") (part "CAP0402"))
    )
    (comp (ref "C702")
      (value "1u0")
      (footprint "eagle-import:0603-CAP")
      (fields (field (name "PARTNO") "CC0603ZRY5V7BB105"))
      (libsource (lib "eagle-import") (part "CAP0603"))
    )
    (comp (ref "C703")
      (value "5n6")
      (footprint "eagle-import:0402-CAP")
      (fields (field (name "PARTNO") "CC0402KRX7R7BB562"))
      (libsource (lib "eagle-import") (part "CAP0402"))
    )
    (comp (ref "C704")
      (value "0u47")
      (footprint "eagle-import:0402-CAP")
      (fields (field (name "PARTNO") "C1005X5R1C474K050BC"))
      (libsource (lib "eagle-import") (part "CAP0402"))
    )
    (comp (ref "J701")
      (value "DF13C-2P-1.25V")
      (footprint "eagle-import:DF13C-2P-1.25V")
      (fields (field (name "PARTNO") "DF13C-2P-1.25V(20)"))
      (libsource (lib "eagle-import") (part "DF13-2P-1.25V"))
    )
    (comp (ref "J702")
      (value "DF13C-3P-1.25V")
      (footprint "eagle-import:DF13C-3P-1.25V")
      (fields (field (name "PARTNO") "DF13C-3P-1.25V(20)"))
      (libsource (lib "eagle-import") (part "DF13-3P-1.25V"))
    )
    (comp (ref "L701")
      (value "47uH")
      (footprint "eagle-import:0805-IND")
      (fields (field (name "PARTNO") "MLZ2012M470W"))
      (libsource (lib "eagle-import") (part "INDUCTOR0805"))
    )
    (comp (ref "LED701")
      (value "AMBER")
      (footprint "eagle-import:0603-LED")
      (fields (field (name "PARTNO") "APTD1608SECK"))
      (libsource (lib "eagle-import") (part "LED0603"))
    )
    (comp (ref "LED702")
      (value "GREEN")
      (footprint "eagle-import:0603-LED")
      (fields (field (name "PARTNO") "APTD1608CGCK"))
      (libsource (lib "eagle-import") (part "LED0603"))
    )
    (comp (ref "LED703")
      (value "AMBER")
      (footprint "eagle-import:0603-LED")
      (fields (field (name "PARTNO") "APTD1608SECK"))
      (libsource (lib "eagle-import") (part "LED0603"))
    )
    (comp (ref "LED704")
      (value "GREEN")
      (footprint "eagle-import:0603-LED")
      (fields (field (name "PARTNO") "APTD1608CGCK"))
      (libsource (lib "eagle-import") (part "LED0603"))
    )
    (comp (ref "LED705")
      (value "BLUE")
      (footprint "eagle-import:0603-LED")
      (fields (field (name "PARTNO") "APTD1608QBC/D"))
      (libsource (lib "eagle-import") (part "LED0603"))
    )
    (comp (ref "R3")
      (value "220R")
      (footprint "eagle-import:0402-RES")
      (fields (field (name "PARTNO") "RC0402FR-07220RL"))
      (libsource (lib "eagle-import") (part "RESISTOR0402-RES"))
    )
    (comp (ref "R4")
      (value "220R")
      (footprint "eagle-import:0402-RES")
      (fields (field (name "PARTNO") "RC0402FR-07220RL"))
      (libsource (lib "eagle-import") (part "RESISTOR0402-RES"))
    )
    (comp (ref "R701")
      (value "9K09")
      (footprint "eagle-import:0402-RES")
      (fields (field (name "PARTNO") "RMCF0402FT9K09"))
      (libsource (lib "eagle-import") (part "RESISTOR0402-RES"))
    )
    (comp (ref "R702")
      (value "10K")
      (footprint "eagle-import:0402-RES")
      (fields (field (name "PARTNO") "RC0402FR-0710KL"))
      (libsource (lib "eagle-import") (part "RESISTOR0402-RES"))
    )
    (comp (ref "R703")
      (value "100K")
      (footprint "eagle-import:0402-RES")
      (fields (field (name "PARTNO") "RC0402FR-07100KL"))
      (libsource (lib "eagle-import") (part "RESISTOR0402-RES"))
    )
    (comp (ref "R704")
      (value "10K")
      (footprint "eagle-import:0402-RES")
      (fields (field (name "PARTNO") "RC0402FR-0710KL"))
      (libsource (lib "eagle-import") (part "RESISTOR0402-RES"))
    )
    (comp (ref "R705")
      (value "453K")
      (footprint "eagle-import:0402-RES")
      (fields (field (name "PARTNO") "RMCF0402FT453K"))
      (libsource (lib "eagle-import") (part "RESISTOR0402-RES"))
    )
    (comp (ref "R706")
      (value "16K5")
      (footprint "eagle-import:0402-RES")
      (fields (field (name "PARTNO") "RMCF0402FT16K5"))
      (libsource (lib "eagle-import") (part "RESISTOR0402-RES"))
    )
    (comp (ref "R707")
      (value "220R")
      (footprint "eagle-import:0402-RES")
      (fields (field (name "PARTNO") "RC0402FR-07220RL"))
      (libsource (lib "eagle-import") (part "RESISTOR0402-RES"))
    )
    (comp (ref "R708")
      (value "220R")
      (footprint "eagle-import:0402-RES")
      (fields (field (name "PARTNO") "RC0402FR-07220RL"))
      (libsource (lib "eagle-import") (part "RESISTOR0402-RES"))
    )
    (comp (ref "R709")
      (value "220R")
      (footprint "eagle-import:0402-RES")
      (fields (field (name "PARTNO") "RC0402FR-07220RL"))
      (libsource (lib "eagle-import") (part "RESISTOR0402-RES"))
    )
    (comp (ref "R710")
      (value "47R")
      (footprint "eagle-import:0402-RES")
      (fields (field (name "PARTNO") "RC0402JR-0747RL"))
      (libsource (lib "eagle-import") (part "RESISTOR0402-RES"))
    )
    (comp (ref "R711")
      (value "220R")
      (footprint "eagle-import:0402-RES")
      (fields (field (name "PARTNO") "RC0402FR-07220RL"))
      (libsource (lib "eagle-import") (part "RESISTOR0402-RES"))
    )
    (comp (ref "R712")
      (value "220R")
      (footprint "eagle-import:0402-RES")
      (fields (field (name "PARTNO") "RC0402FR-07220RL"))
      (libsource (lib "eagle-import") (part "RESISTOR0402-RES"))
    )
    (comp (ref "R713")
      (value "1K5")
      (footprint "eagle-import:0402-RES")
      (fields (field (name "PARTNO") "RC0402FR-071K5L"))
      (libsource (lib "eagle-import") (part "RESISTOR0402-RES"))
    )
    (comp (ref "U$701")
      (value "PESD0402-140")
      (footprint "eagle-import:0402-TVS")
      (libsource (lib "eagle-import") (part "DIODE-TVS"))
    )
    (comp (ref "U701")
      (value "TCA62724FMG")
      (footprint "eagle-import:SON10")
      (libsource (lib "eagle-import") (part "TCA62724FMG"))
    )
    (comp (ref "U702")
      (value "LT3469")
      (footprint "eagle-import:SOT23-8")
      (fields (field (name "PARTNO") "LT3469ETS8"))
      (libsource (lib "eagle-import") (part "LT3469"))
    )
    (comp (ref "U703")
      (value "LRTB GFTG-T7AW-1+V7A7-29+R5T9-49-L")
      (footprint "eagle-import:6-PLCC")
      (fields (field (name "PARTNO") "LRTB GFTG-T7AW-1+V7A7-29+R5T9-49-L"))
      (libsource (lib "eagle-import") (part "RGB-LED6-PLCC"))
    )
  )
  (nets
    (net (code "1") (name "ACCEL_DRDY") (class "Default")
      (node (ref "U$1") (pin "3") (pinfunction "S_3") (pintype "passive"))
      (node (ref "U$501") (pin "11") (pinfunction "INT1_11") (pintype "bidirectional"))
      (node (ref "U101") (pin "90") (pinfunction "PB4_90") (pintype "bidirectional"))
    )
    (net (code "2") (name "ALARM") (class "Default")
      (node (ref "R701") (pin "P$2") (pinfunction "2_P$2") (pintype "passive"))
      (node (ref "U101") (pin "77") (pinfunction "PA15_77") (pintype "bidirectional"))
    )
    (net (code "3") (name "BATT_CURRENT_SENS") (class "Default")
      (node (ref "R604") (pin "P$1") (pinfunction "1_P$1") (pintype "passive"))
      (node (ref "U101") (pin "26") (pinfunction "PA3_26") (pintype "bidirectional"))
    )
    (net (code "4") (name "BATT_VOLTAGE_SENS") (class "Default")
      (node (ref "R605") (pin "P$1") (pinfunction "1_P$1") (pintype "passive"))
      (node (ref "U101") (pin "25") (pinfunction "PA2_25") (pintype "bidirectional"))
    )
    (net (code "5") (name "CAN1_RX") (class "Default")
      (node (ref "U101") (pin "81") (pinfunction "PD0_81") (pintype "bidirectional"))
      (node (ref "U401") (pin "4") (pinfunction "DOUT_4") (pintype "output"))
    )
    (net (code "6") (name "CAN1_TX") (class "Default")
      (node (ref "U101") (pin "82") (pinfunction "PD1_82") (pintype "bidirectional"))
      (node (ref "U401") (pin "1") (pinfunction "DIN_1") (pintype "input"))
    )
    (net (code "7") (name "CAN2_RX") (class "Default")
      (node (ref "R13") (pin "P$1") (pinfunction "1_P$1") (pintype "passive"))
      (node (ref "U101") (pin "51") (pinfunction "PB12_51") (pintype "bidirectional"))
    )
    (net (code "8") (name "CAN2_TX") (class "Default")
      (node (ref "R12") (pin "P$1") (pinfunction "1_P$1") (pintype "passive"))
      (node (ref "U101") (pin "92") (pinfunction "PB6_92") (pintype "bidirectional"))
    )
    (net (code "9") (name "CAN_H") (class "Default")
      (node (ref "CAN_H") (pin "P$1") (pinfunction "P$1_P$1") (pintype "passive"))
      (node (ref "J405") (pin "P$2") (pinfunction "2_P$2") (pintype "passive"))
      (node (ref "R409") (pin "P$1") (pinfunction "1_P$1") (pintype "passive"))
      (node (ref "U401") (pin "7") (pinfunction "CANH_7") (pintype "bidirectional"))
    )
    (net (code "10") (name "CAN_L") (class "Default")
      (node (ref "CAN_L") (pin "P$1") (pinfunction "P$1_P$1") (pintype "passive"))
      (node (ref "J405") (pin "P$3") (pinfunction "3_P$3") (pintype "passive"))
      (node (ref "R409") (pin "P$2") (pinfunction "2_P$2") (pintype "passive"))
      (node (ref "U401") (pin "6") (pinfunction "CANL_6") (pintype "bidirectional"))
    )
    (net (code "11") (name "FMU-BOOT0") (class "Default")
      (node (ref "FMU-BOOT1101") (pin "P$1") (pinfunction "P$1_P$1") (pintype "passive"))
      (node (ref "R611") (pin "P$2") (pinfunction "2_P$2") (pintype "passive"))
      (node (ref "U101") (pin "94") (pinfunction "BOOT0_94") (pintype "input"))
    )
    (net (code "12") (name "FMU-CH1") (class "Default")
      (node (ref "U101") (pin "45") (pinfunction "PE14_45") (pintype "bidirectional"))
      (node (ref "U901") (pin "7") (pinfunction "A6_7") (pintype "bidirectional"))
    )
    (net (code "13") (name "FMU-CH2") (class "Default")
      (node (ref "U101") (pin "44") (pinfunction "PE13_44") (pintype "bidirectional"))
      (node (ref "U901") (pin "6") (pinfunction "A5_6") (pintype "bidirectional"))
    )
    (net (code "14") (name "FMU-CH3") (class "Default")
      (node (ref "U101") (pin "42") (pinfunction "PE11_42") (pintype "bidirectional"))
      (node (ref "U901") (pin "5") (pinfunction "A4_5") (pintype "bidirectional"))
    )
    (net (code "15") (name "FMU-CH4") (class "Default")
      (node (ref "U101") (pin "40") (pinfunction "PE9_40") (pintype "bidirectional"))
      (node (ref "U901") (pin "4") (pinfunction "A3_4") (pintype "bidirectional"))
    )
    (net (code "16") (name "FMU-CH5") (class "Default")
      (node (ref "U101") (pin "60") (pinfunction "PD13_60") (pintype "bidirectional"))
      (node (ref "U901") (pin "3") (pinfunction "A2_3") (pintype "bidirectional"))
    )
    (net (code "17") (name "FMU-CH6") (class "Default")
      (node (ref "U101") (pin "61") (pinfunction "PD14_61") (pintype "bidirectional"))
      (node (ref "U901") (pin "1") (pinfunction "A1_1") (pintype "bidirectional"))
    )
    (net (code "18") (name "FMU-I2C1_SCL") (class "Default")
      (node (ref "R401") (pin "P$1") (pinfunction "1_P$1") (pintype "passive"))
      (node (ref "R404") (pin "P$1") (pinfunction "1_P$1") (pintype "passive"))
      (node (ref "U101") (pin "95") (pinfunction "PB8_95") (pintype "bidirectional"))
    )
    (net (code "19") (name "FMU-I2C1_SDA") (class "Default")
      (node (ref "R402") (pin "P$1") (pinfunction "1_P$1") (pintype "passive"))
      (node (ref "R405") (pin "P$1") (pinfunction "1_P$1") (pintype "passive"))
      (node (ref "U101") (pin "96") (pinfunction "PB9_96") (pintype "bidirectional"))
    )
    (net (code "20") (name "FMU-I2C2_SCL") (class "Default")
      (node (ref "R306") (pin "P$1") (pinfunction "1_P$1") (pintype "passive"))
      (node (ref "U101") (pin "47") (pinfunction "PB10_47") (pintype "bidirectional"))
      (node (ref "U701") (pin "3") (pinfunction "SCL_3") (pintype "bidirectional"))
    )
    (net (code "21") (name "FMU-I2C2_SDA") (class "Default")
      (node (ref "R307") (pin "P$1") (pinfunction "1_P$1") (pintype "passive"))
      (node (ref "U101") (pin "48") (pinfunction "PB11_48") (pintype "bidirectional"))
      (node (ref "U701") (pin "2") (pinfunction "SDA_2") (pintype "bidirectional"))
    )
    (net (code "22") (name "FMU-SWCLK") (class "Default")
      (node (ref "JX301") (pin "4") (pinfunction "S_4") (pintype "passive"))
      (node (ref "U101") (pin "76") (pinfunction "PA14_76") (pintype "bidirectional"))
    )
    (net (code "23") (name "FMU-SWDIO") (class "Default")
      (node (ref "JX301") (pin "2") (pinfunction "S_2") (pintype "passive"))
      (node (ref "U101") (pin "72") (pinfunction "PA13_72") (pintype "bidirectional"))
    )
    (net (code "24") (name "FMU-SWO") (class "Default")
      (node (ref "JX301") (pin "6") (pinfunction "S_6") (pintype "passive"))
      (node (ref "U101") (pin "89") (pinfunction "PB3_89") (pintype "bidirectional"))
    )
    (net (code "25") (name "FMU-UART4_RX") (class "Default")
      (node (ref "U101") (pin "24") (pinfunction "PA1_24") (pintype "bidirectional"))
      (node (ref "U202") (pin "8") (pinfunction "A7_8") (pintype "bidirectional"))
    )
    (net (code "26") (name "FMU-UART4_TX") (class "Default")
      (node (ref "U101") (pin "23") (pinfunction "PA0_23") (pintype "bidirectional"))
      (node (ref "U202") (pin "9") (pinfunction "A8_9") (pintype "bidirectional"))
    )
    (net (code "27") (name "FMU-UART7_RX") (class "Default")
      (node (ref "U101") (pin "38") (pinfunction "PE7_38") (pintype "bidirectional"))
      (node (ref "U202") (pin "4") (pinfunction "A3_4") (pintype "bidirectional"))
    )
    (net (code "28") (name "FMU-UART7_TX") (class "Default")
      (node (ref "U101") (pin "39") (pinfunction "PE8_39") (pintype "bidirectional"))
      (node (ref "U202") (pin "5") (pinfunction "A4_5") (pintype "bidirectional"))
    )
    (net (code "29") (name "FMU-UART8_RX") (class "Default")
      (node (ref "U101") (pin "97") (pinfunction "PE0_97") (pintype "bidirectional"))
      (node (ref "U202") (pin "6") (pinfunction "A5_6") (pintype "bidirectional"))
    )
    (net (code "30") (name "FMU-UART8_TX") (class "Default")
      (node (ref "U101") (pin "98") (pinfunction "PE1_98") (pintype "bidirectional"))
      (node (ref "U202") (pin "7") (pinfunction "A6_7") (pintype "bidirectional"))
    )
    (net (code "31") (name "FMU-USART2_CTS") (class "Default")
      (node (ref "U101") (pin "84") (pinfunction "PD3_84") (pintype "bidirectional"))
      (node (ref "U201") (pin "9") (pinfunction "A8_9") (pintype "bidirectional"))
    )
    (net (code "32") (name "FMU-USART2_RTS") (class "Default")
      (node (ref "U101") (pin "85") (pinfunction "PD4_85") (pintype "bidirectional"))
      (node (ref "U201") (pin "8") (pinfunction "A7_8") (pintype "bidirectional"))
    )
    (net (code "33") (name "FMU-USART2_RX") (class "Default")
      (node (ref "U101") (pin "87") (pinfunction "PD6_87") (pintype "bidirectional"))
      (node (ref "U201") (pin "6") (pinfunction "A5_6") (pintype "bidirectional"))
    )
    (net (code "34") (name "FMU-USART2_TX") (class "Default")
      (node (ref "U101") (pin "86") (pinfunction "PD5_86") (pintype "bidirectional"))
      (node (ref "U201") (pin "7") (pinfunction "A6_7") (pintype "bidirectional"))
    )
    (net (code "35") (name "FMU-USART3_CTS") (class "Default")
      (node (ref "U101") (pin "58") (pinfunction "PD11_58") (pintype "bidirectional"))
      (node (ref "U201") (pin "3") (pinfunction "A2_3") (pintype "bidirectional"))
    )
    (net (code "36") (name "FMU-USART3_RTS") (class "Default")
      (node (ref "U101") (pin "59") (pinfunction "PD12_59") (pintype "bidirectional"))
      (node (ref "U201") (pin "1") (pinfunction "A1_1") (pintype "bidirectional"))
    )
    (net (code "37") (name "FMU-USART3_RX") (class "Default")
      (node (ref "U101") (pin "56") (pinfunction "PD9_56") (pintype "bidirectional"))
      (node (ref "U201") (pin "4") (pinfunction "A3_4") (pintype "bidirectional"))
    )
    (net (code "38") (name "FMU-USART3_TX") (class "Default")
      (node (ref "U101") (pin "55") (pinfunction "PD8_55") (pintype "bidirectional"))
      (node (ref "U201") (pin "5") (pinfunction "A4_5") (pintype "bidirectional"))
    )
    (net (code "39") (name "FMU-VDD_3V3") (class "Default")
      (node (ref "C101") (pin "P$1") (pinfunction "1_P$1") (pintype "passive"))
      (node (ref "C201") (pin "P$1") (pinfunction "1_P$1") (pintype "passive"))
      (node (ref "C202") (pin "P$1") (pinfunction "1_P$1") (pintype "passive"))
      (node (ref "C402") (pin "P$1") (pinfunction "1_P$1") (pintype "passive"))
      (node (ref "C603") (pin "P$1") (pinfunction "1_P$1") (pintype "passive"))
      (node (ref "C604") (pin "P$1") (pinfunction "1_P$1") (pintype "passive"))
      (node (ref "C606") (pin "P$1") (pinfunction "1_P$1") (pintype "passive"))
      (node (ref "C607") (pin "P$1") (pinfunction "1_P$1") (pintype "passive"))
      (node (ref "C608") (pin "P$1") (pinfunction "1_P$1") (pintype "passive"))
      (node (ref "C610") (pin "P$1") (pinfunction "1_P$1") (pintype "passive"))
      (node (ref "C612") (pin "P$1") (pinfunction "1_P$1") (pintype "passive"))
      (node (ref "C701") (pin "P$1") (pinfunction "1_P$1") (pintype "passive"))
      (node (ref "C902") (pin "P$1") (pinfunction "1_P$1") (pintype "passive"))
      (node (ref "JX301") (pin "1") (pinfunction "S_1") (pintype "passive"))
      (node (ref "R301") (pin "P$2") (pinfunction "2_P$2") (pintype "passive"))
      (node (ref "R302") (pin "P$2") (pinfunction "2_P$2") (pintype "passive"))
      (node (ref "R303") (pin "P$2") (pinfunction "2_P$2") (pintype "passive"))
      (node (ref "R304") (pin "P$2") (pinfunction "2_P$2") (pintype "passive"))
      (node (ref "R305") (pin "P$2") (pinfunction "2_P$2") (pintype "passive"))
      (node (ref "R306") (pin "P$2") (pinfunction "2_P$2") (pintype "passive"))
      (node (ref "R307") (pin "P$2") (pinfunction "2_P$2") (pintype "passive"))
      (node (ref "R401") (pin "P$2") (pinfunction "2_P$2") (pintype "passive"))
      (node (ref "R402") (pin "P$2") (pinfunction "2_P$2") (pintype "passive"))
      (node (ref "R608") (pin "P$2") (pinfunction "2_P$2") (pintype "passive"))
      (node (ref "U$605") (pin "7") (pinfunction "VOUT2_7") (pintype "bidirectional"))
      (node (ref "U101") (pin "100") (pinfunction "VDD_100") (pintype "power_in"))
      (node (ref "U101") (pin "11") (pinfunction "VDD_11") (pintype "power_in"))
      (node (ref "U101") (pin "19") (pinfunction "VDD_19") (pintype "power_in"))
      (node (ref "U101") (pin "21") (pinfunction "VREF+_21") (pintype "input"))
      (node (ref "U101") (pin "22") (pinfunction "VDDA_22") (pintype "power_in"))
      (node (ref "U101") (pin "28") (pinfunction "VDD_28") (pintype "power_in"))
      (node (ref "U101") (pin "50") (pinfunction "VDD_50") (pintype "power_in"))
      (node (ref "U101") (pin "75") (pinfunction "VDD_75") (pintype "power_in"))
      (node (ref "U102") (pin "3") (pinfunction "~{W}_3") (pintype "bidirectional"))
      (node (ref "U102") (pin "7") (pinfunction "~{HOLD}_7") (pintype "bidirectional"))
      (node (ref "U102") (pin "8") (pinfunction "VDD_8") (pintype "bidirectional"))
      (node (ref "U201") (pin "10") (pinfunction "OE_10") (pintype "input"))
      (node (ref "U201") (pin "19") (pinfunction "VCCB_19") (pintype "input"))
      (node (ref "U201") (pin "2") (pinfunction "VCCA_2") (pintype "input"))
      (node (ref "U202") (pin "10") (pinfunction "OE_10") (pintype "input"))
      (node (ref "U202") (pin "19") (pinfunction "VCCB_19") (pintype "input"))
      (node (ref "U202") (pin "2") (pinfunction "VCCA_2") (pintype "input"))
      (node (ref "U301") (pin "4") (pinfunction "VCC_4") (pintype "passive"))
      (node (ref "U401") (pin "3") (pinfunction "VCC_3") (pintype "input"))
      (node (ref "U701") (pin "1") (pinfunction "~{SHDN}_1") (pintype "input"))
      (node (ref "U701") (pin "10") (pinfunction "VIN_10") (pintype "power_in"))
      (node (ref "U901") (pin "10") (pinfunction "OE_10") (pintype "input"))
      (node (ref "U901") (pin "19") (pinfunction "VCCB_19") (pintype "input"))
      (node (ref "U901") (pin "2") (pinfunction "VCCA_2") (pintype "input"))
      (node (ref "VDD_3V1101") (pin "P$1") (pinfunction "P$1_P$1") (pintype "passive"))
    )
    (net (code "40") (name "FMU-~{RESET}") (class "Default")
      (node (ref "C609") (pin "P$2") (pinfunction "2_P$2") (pintype "passive"))
      (node (ref "S601") (pin "A1") (pinfunction "1_A1") (pintype "passive"))
      (node (ref "U$605") (pin "3") (pinfunction "POR2_3") (pintype "bidirectional"))
      (node (ref "U101") (pin "14") (pinfunction "NRST_14") (pintype "input"))
      (node (ref "U701") (pin "4") (pinfunction "~{RESET}_4") (pintype "input"))
    )
    (net (code "41") (name "FMU_AUX_ADC1") (class "Default")
      (node (ref "R408") (pin "P$1") (pinfunction "1_P$1") (pintype "passive"))
      (node (ref "U101") (pin "18") (pinfunction "PC3_18") (pintype "bidirectional"))
    )
    (net (code "42") (name "FMU_AUX_ADC2") (class "Default")
      (node (ref "R407") (pin "P$1") (pinfunction "1_P$1") (pintype "passive"))
      (node (ref "U101") (pin "33") (pinfunction "PC4_33") (pintype "bidirectional"))
    )
    (net (code "43") (name "FRAM_MISO") (class "Default")
      (node (ref "U101") (pin "53") (pinfunction "PB14_53") (pintype "bidirectional"))
      (node (ref "U102") (pin "2") (pinfunction "Q_2") (pintype "bidirectional"))
    )
    (net (code "44") (name "FRAM_MOSI") (class "Default")
      (node (ref "U101") (pin "54") (pinfunction "PB15_54") (pintype "bidirectional"))
      (node (ref "U102") (pin "5") (pinfunction "D_5") (pintype "bidirectional"))
    )
    (net (code "45") (name "FRAM_SCK") (class "Default")
      (node (ref "U101") (pin "52") (pinfunction "PB13_52") (pintype "bidirectional"))
      (node (ref "U102") (pin "6") (pinfunction "C_6") (pintype "bidirectional"))
    )
    (net (code "46") (name "GND") (class "Default")
      (node (ref "B601") (pin "2") (pinfunction "NEG_2") (pintype "bidirectional"))
      (node (ref "C1001") (pin "P$2") (pinfunction "2_P$2") (pintype "passive"))
      (node (ref "C1002") (pin "P$2") (pinfunction "2_P$2") (pintype "passive"))
      (node (ref "C1003") (pin "P$2") (pinfunction "2_P$2") (pintype "passive"))
      (node (ref "C1004") (pin "P$2") (pinfunction "2_P$2") (pintype "passive"))
      (node (ref "C101") (pin "P$2") (pinfunction "2_P$2") (pintype "passive"))
      (node (ref "C102") (pin "P$2") (pinfunction "2_P$2") (pintype "passive"))
      (node (ref "C103") (pin "P$1") (pinfunction "1_P$1") (pintype "passive"))
      (node (ref "C201") (pin "P$2") (pinfunction "2_P$2") (pintype "passive"))
      (node (ref "C202") (pin "P$2") (pinfunction "2_P$2") (pintype "passive"))
      (node (ref "C401") (pin "P$2") (pinfunction "2_P$2") (pintype "passive"))
      (node (ref "C402") (pin "P$2") (pinfunction "2_P$2") (pintype "passive"))
      (node (ref "C501") (pin "P$2") (pinfunction "2_P$2") (pintype "passive"))
      (node (ref "C502") (pin "P$2") (pinfunction "2_P$2") (pintype "passive"))
      (node (ref "C503") (pin "P$2") (pinfunction "2_P$2") (pintype "passive"))
      (node (ref "C504") (pin "P$2") (pinfunction "2_P$2") (pintype "passive"))
      (node (ref "C505") (pin "P$2") (pinfunction "2_P$2") (pintype "passive"))
      (node (ref "C506") (pin "P$2") (pinfunction "2_P$2") (pintype "passive"))
      (node (ref "C507") (pin "P$2") (pinfunction "2_P$2") (pintype "passive"))
      (node (ref "C508") (pin "P$2") (pinfunction "2_P$2") (pintype "passive"))
      (node (ref "C509") (pin "P$2") (pinfunction "2_P$2") (pintype "passive"))
      (node (ref "C601") (pin "P$2") (pinfunction "2_P$2") (pintype "passive"))
      (node (ref "C602") (pin "P$1") (pinfunction "1_P$1") (pintype "passive"))
      (node (ref "C603") (pin "P$2") (pinfunction "2_P$2") (pintype "passive"))
      (node (ref "C604") (pin "P$2") (pinfunction "2_P$2") (pintype "passive"))
      (node (ref "C605") (pin "P$2") (pinfunction "2_P$2") (pintype "passive"))
      (node (ref "C606") (pin "P$2") (pinfunction "2_P$2") (pintype "passive"))
      (node (ref "C607") (pin "P$2") (pinfunction "2_P$2") (pintype "passive"))
      (node (ref "C608") (pin "P$2") (pinfunction "2_P$2") (pintype "passive"))
      (node (ref "C609") (pin "P$1") (pinfunction "1_P$1") (pintype "passive"))
      (node (ref "C610") (pin "P$2") (pinfunction "2_P$2") (pintype "passive"))
      (node (ref "C611") (pin "P$2") (pinfunction "2_P$2") (pintype "passive"))
      (node (ref "C612") (pin "P$2") (pinfunction "2_P$2") (pintype "passive"))
      (node (ref "C613") (pin "P$2") (pinfunction "2_P$2") (pintype "passive"))
      (node (ref "C701") (pin "P$2") (pinfunction "2_P$2") (pintype "passive"))
      (node (ref "C702") (pin "P$2") (pinfunction "2_P$2") (pintype "passive"))
      (node (ref "C703") (pin "P$2") (pinfunction "2_P$2") (pintype "passive"))
      (node (ref "C704") (pin "P$2") (pinfunction "2_P$2") (pintype "passive"))
      (node (ref "C801") (pin "P$1") (pinfunction "1_P$1") (pintype "passive"))
      (node (ref "C802") (pin "P$2") (pinfunction "2_P$2") (pintype "passive"))
      (node (ref "C803") (pin "P$2") (pinfunction "2_P$2") (pintype "passive"))
      (node (ref "C804") (pin "P$2") (pinfunction "2_P$2") (pintype "passive"))
      (node (ref "C805") (pin "P$2") (pinfunction "2_P$2") (pintype "passive"))
      (node (ref "C806") (pin "P$1") (pinfunction "1_P$1") (pintype "passive"))
      (node (ref "C901") (pin "P$2") (pinfunction "2_P$2") (pintype "passive"))
      (node (ref "C902") (pin "P$2") (pinfunction "2_P$2") (pintype "passive"))
      (node (ref "C903") (pin "P$2") (pinfunction "2_P$2") (pintype "passive"))
      (node (ref "GND") (pin "P$1") (pinfunction "P$1_P$1") (pintype "passive"))
      (node (ref "GND.") (pin "P$1") (pinfunction "P$1_P$1") (pintype "passive"))
      (node (ref "J201") (pin "P$6") (pinfunction "6_P$6") (pintype "passive"))
      (node (ref "J202") (pin "P$6") (pinfunction "6_P$6") (pintype "passive"))
      (node (ref "J203") (pin "P$6") (pinfunction "6_P$6") (pintype "passive"))
      (node (ref "J204") (pin "P$6") (pinfunction "6_P$6") (pintype "passive"))
      (node (ref "J301") (pin "GND") (pinfunction "5_GND") (pintype "power_in"))
      (node (ref "J301") (pin "GND1") (pinfunction "GND1_GND1") (pintype "bidirectional"))
      (node (ref "J301") (pin "GND2") (pinfunction "GND2_GND2") (pintype "bidirectional"))
      (node (ref "J301") (pin "GND3") (pinfunction "GND3_GND3") (pintype "bidirectional"))
      (node (ref "J301") (pin "GND4") (pinfunction "GND4_GND4") (pintype "bidirectional"))
      (node (ref "J302") (pin "P$4") (pinfunction "4_P$4") (pintype "passive"))
      (node (ref "J401") (pin "P$4") (pinfunction "4_P$4") (pintype "passive"))
      (node (ref "J402") (pin "P$3") (pinfunction "3_P$3") (pintype "passive"))
      (node (ref "J403") (pin "P$7") (pinfunction "7_P$7") (pintype "passive"))
      (node (ref "J404") (pin "P$3") (pinfunction "3_P$3") (pintype "passive"))
      (node (ref "J404") (pin "P$5") (pinfunction "5_P$5") (pintype "passive"))
      (node (ref "J405") (pin "P$4") (pinfunction "4_P$4") (pintype "passive"))
      (node (ref "J601") (pin "P$5") (pinfunction "5_P$5") (pintype "passive"))
      (node (ref "J601") (pin "P$6") (pinfunction "6_P$6") (pintype "passive"))
      (node (ref "J701") (pin "P$2") (pinfunction "2_P$2") (pintype "passive"))
      (node (ref "J801") (pin "P$2") (pinfunction "P$2_P$2") (pintype "bidirectional"))
      (node (ref "J901") (pin "12") (pinfunction "S_12") (pintype "passive"))
      (node (ref "J901") (pin "15") (pinfunction "S_15") (pintype "passive"))
      (node (ref "J901") (pin "18") (pinfunction "S_18") (pintype "passive"))
      (node (ref "J901") (pin "21") (pinfunction "S_21") (pintype "passive"))
      (node (ref "J901") (pin "24") (pinfunction "S_24") (pintype "passive"))
      (node (ref "J901") (pin "27") (pinfunction "S_27") (pintype "passive"))
      (node (ref "J901") (pin "3") (pinfunction "S_3") (pintype "passive"))
      (node (ref "J901") (pin "30") (pinfunction "S_30") (pintype "passive"))
      (node (ref "J901") (pin "33") (pinfunction "S_33") (pintype "passive"))
      (node (ref "J901") (pin "36") (pinfunction "S_36") (pintype "passive"))
      (node (ref "J901") (pin "39") (pinfunction "S_39") (pintype "passive"))
      (node (ref "J901") (pin "42") (pinfunction "S_42") (pintype "passive"))
      (node (ref "J901") (pin "45") (pinfunction "S_45") (pintype "passive"))
      (node (ref "J901") (pin "48") (pinfunction "S_48") (pintype "passive"))
      (node (ref "J901") (pin "6") (pinfunction "S_6") (pintype "passive"))
      (node (ref "J901") (pin "9") (pinfunction "S_9") (pintype "passive"))
      (node (ref "JX301") (pin "3") (pinfunction "S_3") (pintype "passive"))
      (node (ref "JX301") (pin "5") (pinfunction "S_5") (pintype "passive"))
      (node (ref "JX301") (pin "9") (pinfunction "S_9") (pintype "passive"))
      (node (ref "JX801") (pin "3") (pinfunction "GND_3") (pintype "bidirectional"))
      (node (ref "JX802") (pin "3") (pinfunction "S_3") (pintype "passive"))
      (node (ref "JX802") (pin "5") (pinfunction "S_5") (pintype "passive"))
      (node (ref "JX802") (pin "9") (pinfunction "S_9") (pintype "passive"))
      (node (ref "L201") (pin "P$3") (pinfunction "P$3_P$3") (pintype "bidirectional"))
      (node (ref "L201") (pin "P$4") (pinfunction "P$3_P$4") (pintype "bidirectional"))
      (node (ref "L201") (pin "P$5") (pinfunction "P$3_P$5") (pintype "bidirectional"))
      (node (ref "L202") (pin "P$3") (pinfunction "P$3_P$3") (pintype "bidirectional"))
      (node (ref "L202") (pin "P$4") (pinfunction "P$3_P$4") (pintype "bidirectional"))
      (node (ref "L202") (pin "P$5") (pinfunction "P$3_P$5") (pintype "bidirectional"))
      (node (ref "L203") (pin "P$3") (pinfunction "P$3_P$3") (pintype "bidirectional"))
      (node (ref "L203") (pin "P$4") (pinfunction "P$3_P$4") (pintype "bidirectional"))
      (node (ref "L203") (pin "P$5") (pinfunction "P$3_P$5") (pintype "bidirectional"))
      (node (ref "L401") (pin "P$3") (pinfunction "P$3_P$3") (pintype "bidirectional"))
      (node (ref "L401") (pin "P$4") (pinfunction "P$3_P$4") (pintype "bidirectional"))
      (node (ref "L401") (pin "P$5") (pinfunction "P$3_P$5") (pintype "bidirectional"))
      (node (ref "L402") (pin "P$3") (pinfunction "P$3_P$3") (pintype "bidirectional"))
      (node (ref "L402") (pin "P$4") (pinfunction "P$3_P$4") (pintype "bidirectional"))
      (node (ref "L402") (pin "P$5") (pinfunction "P$3_P$5") (pintype "bidirectional"))
      (node (ref "L403") (pin "P$3") (pinfunction "P$3_P$3") (pintype "bidirectional"))
      (node (ref "L403") (pin "P$4") (pinfunction "P$3_P$4") (pintype "bidirectional"))
      (node (ref "L403") (pin "P$5") (pinfunction "P$3_P$5") (pintype "bidirectional"))
      (node (ref "L404") (pin "P$3") (pinfunction "P$3_P$3") (pintype "bidirectional"))
      (node (ref "L404") (pin "P$4") (pinfunction "P$3_P$4") (pintype "bidirectional"))
      (node (ref "L404") (pin "P$5") (pinfunction "P$3_P$5") (pintype "bidirectional"))
      (node (ref "L601") (pin "P$3") (pinfunction "P$3_P$3") (pintype "bidirectional"))
      (node (ref "L601") (pin "P$4") (pinfunction "P$3_P$4") (pintype "bidirectional"))
      (node (ref "L601") (pin "P$5") (pinfunction "P$3_P$5") (pintype "bidirectional"))
      (node (ref "L602") (pin "P$3") (pinfunction "P$3_P$3") (pintype "bidirectional"))
      (node (ref "L602") (pin "P$4") (pinfunction "P$3_P$4") (pintype "bidirectional"))
      (node (ref "L602") (pin "P$5") (pinfunction "P$3_P$5") (pintype "bidirectional"))
      (node (ref "L603") (pin "P$3") (pinfunction "P$3_P$3") (pintype "bidirectional"))
      (node (ref "L603") (pin "P$4") (pinfunction "P$3_P$4") (pintype "bidirectional"))
      (node (ref "L603") (pin "P$5") (pinfunction "P$3_P$5") (pintype "bidirectional"))
      (node (ref "L901") (pin "P$3") (pinfunction "P$3_P$3") (pintype "bidirectional"))
      (node (ref "L901") (pin "P$4") (pinfunction "P$3_P$4") (pintype "bidirectional"))
      (node (ref "L901") (pin "P$5") (pinfunction "P$3_P$5") (pintype "bidirectional"))
      (node (ref "R1001") (pin "P$1") (pinfunction "1_P$1") (pintype "passive"))
      (node (ref "R1002") (pin "P$1") (pinfunction "1_P$1") (pintype "passive"))
      (node (ref "R102") (pin "P$2") (pinfunction "2_P$2") (pintype "passive"))
      (node (ref "R11") (pin "P$2") (pinfunction "2_P$2") (pintype "passive"))
      (node (ref "R403") (pin "P$1") (pinfunction "1_P$1") (pintype "passive"))
      (node (ref "R5") (pin "P$2") (pinfunction "2_P$2") (pintype "passive"))
      (node (ref "R602") (pin "P$2") (pinfunction "2_P$2") (pintype "passive"))
      (node (ref "R606") (pin "P$2") (pinfunction "2_P$2") (pintype "passive"))
      (node (ref "R607") (pin "P$2") (pinfunction "2_P$2") (pintype "passive"))
      (node (ref "R610") (pin "P$2") (pinfunction "2_P$2") (pintype "passive"))
      (node (ref "R611") (pin "P$1") (pinfunction "1_P$1") (pintype "passive"))
      (node (ref "R702") (pin "P$2") (pinfunction "2_P$2") (pintype "passive"))
      (node (ref "R704") (pin "P$1") (pinfunction "1_P$1") (pintype "passive"))
      (node (ref "R706") (pin "P$2") (pinfunction "2_P$2") (pintype "passive"))
      (node (ref "R708") (pin "P$1") (pinfunction "1_P$1") (pintype "passive"))
      (node (ref "R711") (pin "P$1") (pinfunction "1_P$1") (pintype "passive"))
      (node (ref "R713") (pin "P$2") (pinfunction "2_P$2") (pintype "passive"))
      (node (ref "R8") (pin "P$2") (pinfunction "2_P$2") (pintype "passive"))
      (node (ref "R801") (pin "P$2") (pinfunction "2_P$2") (pintype "passive"))
      (node (ref "R802") (pin "P$2") (pinfunction "2_P$2") (pintype "passive"))
      (node (ref "R919") (pin "P$1") (pinfunction "1_P$1") (pintype "passive"))
      (node (ref "S601") (pin "B3") (pinfunction "2_B3") (pintype "passive"))
      (node (ref "S801") (pin "B3") (pinfunction "2_B3") (pintype "passive"))
      (node (ref "U$1") (pin "2") (pinfunction "S_2") (pintype "passive"))
      (node (ref "U$1001") (pin "2") (pinfunction "VSS_2") (pintype "bidirectional"))
      (node (ref "U$1001") (pin "5") (pinfunction "~{CE}_5") (pintype "bidirectional"))
      (node (ref "U$1001") (pin "6") (pinfunction "VBAT_6") (pintype "bidirectional"))
      (node (ref "U$1001") (pin "GND") (pinfunction "VSS_GND") (pintype "bidirectional"))
      (node (ref "U$1001") (pin "P$2") (pinfunction "VSS_P$2") (pintype "bidirectional"))
      (node (ref "U$1001") (pin "P$3") (pinfunction "VSS_P$3") (pintype "bidirectional"))
      (node (ref "U$1002") (pin "2") (pinfunction "GND_2") (pintype "bidirectional"))
      (node (ref "U$1002") (pin "GND") (pinfunction "GND_GND") (pintype "bidirectional"))
      (node (ref "U$2") (pin "P$10") (pinfunction "GND_P$10") (pintype "bidirectional"))
      (node (ref "U$2") (pin "P$24") (pinfunction "HYS_P$24") (pintype "bidirectional"))
      (node (ref "U$2") (pin "P$25") (pinfunction "GND_P$25") (pintype "bidirectional"))
      (node (ref "U$201") (pin "A") (pinfunction "A_A") (pintype "passive"))
      (node (ref "U$202") (pin "A") (pinfunction "A_A") (pintype "passive"))
      (node (ref "U$203") (pin "A") (pinfunction "A_A") (pintype "passive"))
      (node (ref "U$301") (pin "2") (pinfunction "GND_2") (pintype "bidirectional"))
      (node (ref "U$401") (pin "A") (pinfunction "A_A") (pintype "passive"))
      (node (ref "U$402") (pin "A") (pinfunction "A_A") (pintype "passive"))
      (node (ref "U$403") (pin "A") (pinfunction "A_A") (pintype "passive"))
      (node (ref "U$404") (pin "A") (pinfunction "A_A") (pintype "passive"))
      (node (ref "U$501") (pin "10") (pinfunction "RSRV_10") (pintype "bidirectional"))
      (node (ref "U$501") (pin "12") (pinfunction "GND_12") (pintype "bidirectional"))
      (node (ref "U$501") (pin "13") (pinfunction "GND_13") (pintype "bidirectional"))
      (node (ref "U$501") (pin "16") (pinfunction "GND_16") (pintype "bidirectional"))
      (node (ref "U$501") (pin "5") (pinfunction "GND_5") (pintype "bidirectional"))
      (node (ref "U$6") (pin "A") (pinfunction "A_A") (pintype "passive"))
      (node (ref "U$602") (pin "2") (pinfunction "VSS_2") (pintype "bidirectional"))
      (node (ref "U$602") (pin "6") (pinfunction "VBAT_6") (pintype "bidirectional"))
      (node (ref "U$602") (pin "GND") (pinfunction "VSS_GND") (pintype "bidirectional"))
      (node (ref "U$602") (pin "P$2") (pinfunction "VSS_P$2") (pintype "bidirectional"))
      (node (ref "U$602") (pin "P$3") (pinfunction "VSS_P$3") (pintype "bidirectional"))
      (node (ref "U$604") (pin "2") (pinfunction "VSS_2") (pintype "bidirectional"))
      (node (ref "U$604") (pin "6") (pinfunction "VBAT_6") (pintype "bidirectional"))
      (node (ref "U$604") (pin "GND") (pinfunction "VSS_GND") (pintype "bidirectional"))
      (node (ref "U$604") (pin "P$2") (pinfunction "VSS_P$2") (pintype "bidirectional"))
      (node (ref "U$604") (pin "P$3") (pinfunction "VSS_P$3") (pintype "bidirectional"))
      (node (ref "U$605") (pin "2") (pinfunction "GND_2") (pintype "bidirectional"))
      (node (ref "U$605") (pin "GND") (pinfunction "GND_GND") (pintype "bidirectional"))
      (node (ref "U$701") (pin "A") (pinfunction "A_A") (pintype "passive"))
      (node (ref "U$801") (pin "A") (pinfunction "A_A") (pintype "passive"))
      (node (ref "U$901") (pin "A") (pinfunction "A_A") (pintype "passive"))
      (node (ref "U$902") (pin "A") (pinfunction "A_A") (pintype "passive"))
      (node (ref "U101") (pin "10") (pinfunction "VSS_10") (pintype "power_in"))
      (node (ref "U101") (pin "20") (pinfunction "VSSA_20") (pintype "power_in"))
      (node (ref "U101") (pin "27") (pinfunction "VSS_27") (pintype "power_in"))
      (node (ref "U101") (pin "74") (pinfunction "VSS_74") (pintype "power_in"))
      (node (ref "U101") (pin "99") (pinfunction "VSS_99") (pintype "power_in"))
      (node (ref "U102") (pin "4") (pinfunction "VSS_4") (pintype "bidirectional"))
      (node (ref "U201") (pin "11") (pinfunction "GND_11") (pintype "power_in"))
      (node (ref "U202") (pin "11") (pinfunction "GND_11") (pintype "power_in"))
      (node (ref "U301") (pin "6") (pinfunction "GND_6") (pintype "power_in"))
      (node (ref "U401") (pin "2") (pinfunction "GND_2") (pintype "power_in"))
      (node (ref "U401") (pin "5") (pinfunction "SHDN_5") (pintype "input"))
      (node (ref "U401") (pin "8") (pinfunction "RS_8") (pintype "input"))
      (node (ref "U501") (pin "10") (pinfunction "RES_P10_GND_10") (pintype "bidirectional"))
      (node (ref "U501") (pin "11") (pinfunction "RES_P11_GND_11") (pintype "bidirectional"))
      (node (ref "U501") (pin "12") (pinfunction "RES_P12_GND_12") (pintype "bidirectional"))
      (node (ref "U501") (pin "13") (pinfunction "GND_13") (pintype "bidirectional"))
      (node (ref "U501") (pin "8") (pinfunction "RES_P8_GND_8") (pintype "bidirectional"))
      (node (ref "U501") (pin "9") (pinfunction "RES_P9_GND_9") (pintype "bidirectional"))
      (node (ref "U502") (pin "10") (pinfunction "GND_10") (pintype "bidirectional"))
      (node (ref "U502") (pin "11") (pinfunction "GND_11") (pintype "bidirectional"))
      (node (ref "U502") (pin "12") (pinfunction "GND_12") (pintype "bidirectional"))
      (node (ref "U502") (pin "13") (pinfunction "GND_13") (pintype "bidirectional"))
      (node (ref "U502") (pin "9") (pinfunction "GND_9") (pintype "bidirectional"))
      (node (ref "U503") (pin "2") (pinfunction "PS_2") (pintype "bidirectional"))
      (node (ref "U503") (pin "3") (pinfunction "GND_3") (pintype "bidirectional"))
      (node (ref "U701") (pin "5") (pinfunction "GND_5") (pintype "power_in"))
      (node (ref "U702") (pin "4") (pinfunction "GND_4") (pintype "power_in"))
      (node (ref "U801") (pin "23") (pinfunction "VSS_1_23") (pintype "power_in"))
      (node (ref "U801") (pin "35") (pinfunction "VSS_2_35") (pintype "power_in"))
      (node (ref "U801") (pin "47") (pinfunction "VSS_3_47") (pintype "power_in"))
      (node (ref "U801") (pin "8") (pinfunction "VSSA_8") (pintype "power_in"))
      (node (ref "U901") (pin "11") (pinfunction "GND_11") (pintype "power_in"))
      (node (ref "U902") (pin "11") (pinfunction "GND_11") (pintype "power_in"))
      (node (ref "U903") (pin "1") (pinfunction "~{1OE}_1") (pintype "input"))
      (node (ref "U903") (pin "4") (pinfunction "GND_4") (pintype "power_in"))
      (node (ref "X101") (pin "2") (pinfunction "NC_2_2") (pintype "power_in"))
      (node (ref "X101") (pin "4") (pinfunction "NC_4_4") (pintype "power_in"))
      (node (ref "X801") (pin "2") (pinfunction "NC_2_2") (pintype "power_in"))
      (node (ref "X801") (pin "4") (pinfunction "NC_4_4") (pintype "power_in"))
    )
    (net (code "47") (name "GPIO_EXT_1") (class "Default")
      (node (ref "J403") (pin "P$6") (pinfunction "6_P$6") (pintype "passive"))
      (node (ref "U101") (pin "8") (pinfunction "PC14_8") (pintype "bidirectional"))
    )
    (net (code "48") (name "GYRO_DRDY") (class "Default")
      (node (ref "U$1") (pin "5") (pinfunction "S_5") (pintype "passive"))
      (node (ref "U101") (pin "35") (pinfunction "PB0_35") (pintype "bidirectional"))
      (node (ref "U501") (pin "6") (pinfunction "DRDY/INT2_6") (pintype "output"))
      (node (ref "U502") (pin "6") (pinfunction "DRDY/INT2_6") (pintype "bidirectional"))
    )
    (net (code "49") (name "IO-BOOT0") (class "Default")
      (node (ref "IO-BOOT1101") (pin "P$1") (pinfunction "P$1_P$1") (pintype "passive"))
      (node (ref "R801") (pin "P$1") (pinfunction "1_P$1") (pintype "passive"))
      (node (ref "U801") (pin "44") (pinfunction "BOOT0_44") (pintype "input"))
    )
    (net (code "50") (name "IO-CH1") (class "Default")
      (node (ref "U801") (pin "10") (pinfunction "PA0_10") (pintype "bidirectional"))
      (node (ref "U902") (pin "9") (pinfunction "A8_9") (pintype "bidirectional"))
    )
    (net (code "51") (name "IO-CH2") (class "Default")
      (node (ref "U801") (pin "11") (pinfunction "PA1_11") (pintype "bidirectional"))
      (node (ref "U902") (pin "8") (pinfunction "A7_8") (pintype "bidirectional"))
    )
    (net (code "52") (name "IO-CH3") (class "Default")
      (node (ref "U801") (pin "45") (pinfunction "PB8_45") (pintype "bidirectional"))
      (node (ref "U902") (pin "7") (pinfunction "A6_7") (pintype "bidirectional"))
    )
    (net (code "53") (name "IO-CH4") (class "Default")
      (node (ref "U801") (pin "46") (pinfunction "PB9_46") (pintype "bidirectional"))
      (node (ref "U902") (pin "6") (pinfunction "A5_6") (pintype "bidirectional"))
    )
    (net (code "54") (name "IO-CH5") (class "Default")
      (node (ref "U801") (pin "16") (pinfunction "PA6_16") (pintype "bidirectional"))
      (node (ref "U902") (pin "5") (pinfunction "A4_5") (pintype "bidirectional"))
    )
    (net (code "55") (name "IO-CH6") (class "Default")
      (node (ref "U801") (pin "17") (pinfunction "PA7_17") (pintype "bidirectional"))
      (node (ref "U902") (pin "4") (pinfunction "A3_4") (pintype "bidirectional"))
    )
    (net (code "56") (name "IO-CH7") (class "Default")
      (node (ref "U801") (pin "18") (pinfunction "PB0_18") (pintype "bidirectional"))
      (node (ref "U902") (pin "3") (pinfunction "A2_3") (pintype "bidirectional"))
    )
    (net (code "57") (name "IO-CH8") (class "Default")
      (node (ref "U801") (pin "19") (pinfunction "PB1_19") (pintype "bidirectional"))
      (node (ref "U902") (pin "1") (pinfunction "A1_1") (pintype "bidirectional"))
    )
    (net (code "58") (name "IO-SWCLK") (class "Default")
      (node (ref "JX802") (pin "4") (pinfunction "S_4") (pintype "passive"))
      (node (ref "U801") (pin "37") (pinfunction "PA14_37") (pintype "bidirectional"))
    )
    (net (code "59") (name "IO-SWDIO") (class "Default")
      (node (ref "JX802") (pin "2") (pinfunction "S_2") (pintype "passive"))
      (node (ref "U801") (pin "34") (pinfunction "PA13_34") (pintype "bidirectional"))
    )
    (net (code "60") (name "IO-SWO") (class "Default")
      (node (ref "JX802") (pin "6") (pinfunction "S_6") (pintype "passive"))
      (node (ref "U801") (pin "39") (pinfunction "PB3_39") (pintype "bidirectional"))
    )
    (net (code "61") (name "IO-USART1_RX") (class "Default")
      (node (ref "J801") (pin "P$3") (pinfunction "P$3_P$3") (pintype "bidirectional"))
      (node (ref "JX801") (pin "2") (pinfunction "+5V_2") (pintype "bidirectional"))
      (node (ref "U801") (pin "31") (pinfunction "PA10_31") (pintype "bidirectional"))
    )
    (net (code "62") (name "IO-USART1_TX") (class "Default")
      (node (ref "JX801") (pin "1") (pinfunction "PPM_1") (pintype "bidirectional"))
      (node (ref "R101") (pin "P$2") (pinfunction "2_P$2") (pintype "passive"))
      (node (ref "U801") (pin "30") (pinfunction "PA9_30") (pintype "bidirectional"))
    )
    (net (code "63") (name "IO-VDD_3V3") (class "Default")
      (node (ref "C1004") (pin "P$1") (pinfunction "1_P$1") (pintype "passive"))
      (node (ref "C802") (pin "P$1") (pinfunction "1_P$1") (pintype "passive"))
      (node (ref "C803") (pin "P$1") (pinfunction "1_P$1") (pintype "passive"))
      (node (ref "C804") (pin "P$1") (pinfunction "1_P$1") (pintype "passive"))
      (node (ref "C901") (pin "P$1") (pinfunction "1_P$1") (pintype "passive"))
      (node (ref "C903") (pin "P$1") (pinfunction "1_P$1") (pintype "passive"))
      (node (ref "J702") (pin "P$1") (pinfunction "1_P$1") (pintype "passive"))
      (node (ref "JX802") (pin "1") (pinfunction "S_1") (pintype "passive"))
      (node (ref "U$1002") (pin "7") (pinfunction "VOUT2_7") (pintype "bidirectional"))
      (node (ref "U$701") (pin "C") (pinfunction "C_C") (pintype "passive"))
      (node (ref "U801") (pin "24") (pinfunction "VDD_1_24") (pintype "power_in"))
      (node (ref "U801") (pin "36") (pinfunction "VDD_2_36") (pintype "power_in"))
      (node (ref "U801") (pin "48") (pinfunction "VDD_3_48") (pintype "power_in"))
      (node (ref "U801") (pin "9") (pinfunction "VDDA_9") (pintype "power_in"))
      (node (ref "U902") (pin "10") (pinfunction "OE_10") (pintype "input"))
      (node (ref "U902") (pin "19") (pinfunction "VCCB_19") (pintype "input"))
      (node (ref "U902") (pin "2") (pinfunction "VCCA_2") (pintype "input"))
      (node (ref "U903") (pin "8") (pinfunction "VCC_8") (pintype "power_in"))
    )
    (net (code "64") (name "IO-VDD_5V5") (class "Default")
      (node (ref "C1001") (pin "P$1") (pinfunction "1_P$1") (pintype "passive"))
      (node (ref "D1001") (pin "3") (pinfunction "CC_3") (pintype "passive"))
      (node (ref "J901") (pin "2") (pinfunction "S_2") (pintype "passive"))
      (node (ref "LED702") (pin "A") (pinfunction "A_A") (pintype "passive"))
      (node (ref "LED703") (pin "A") (pinfunction "A_A") (pintype "passive"))
      (node (ref "LED705") (pin "A") (pinfunction "A_A") (pintype "passive"))
      (node (ref "U$1002") (pin "1") (pinfunction "VIN_1") (pintype "bidirectional"))
      (node (ref "U$1002") (pin "4") (pinfunction "EN2_4") (pintype "bidirectional"))
    )
    (net (code "65") (name "IO-~{RESET}") (class "Default")
      (node (ref "C801") (pin "P$2") (pinfunction "2_P$2") (pintype "passive"))
      (node (ref "S801") (pin "A1") (pinfunction "1_A1") (pintype "passive"))
      (node (ref "U$1002") (pin "3") (pinfunction "POR2_3") (pintype "bidirectional"))
      (node (ref "U801") (pin "7") (pinfunction "NRST_7") (pintype "input"))
    )
    (net (code "66") (name "IO-~{VDD_SERVO_IN_FAULT}") (class "Default")
      (node (ref "U$1001") (pin "4") (pinfunction "~{FAULT}_4") (pintype "bidirectional"))
      (node (ref "U801") (pin "38") (pinfunction "PA15_38") (pintype "bidirectional"))
    )
    (net (code "67") (name "MAG_DRDY") (class "Default")
      (node (ref "U$1") (pin "4") (pinfunction "S_4") (pintype "passive"))
      (node (ref "U$501") (pin "9") (pinfunction "INT2_9") (pintype "bidirectional"))
      (node (ref "U101") (pin "36") (pinfunction "PB1_36") (pintype "bidirectional"))
    )
    (net (code "68") (name "Net-(C102-1)") (class "Default")
      (node (ref "C102") (pin "P$1") (pinfunction "1_P$1") (pintype "passive"))
      (node (ref "U101") (pin "12") (pinfunction "OSC_IN_12") (pintype "input"))
      (node (ref "X101") (pin "3") (pinfunction "3_3") (pintype "bidirectional"))
    )
    (net (code "69") (name "Net-(C103-2)") (class "Default")
      (node (ref "C103") (pin "P$2") (pinfunction "2_P$2") (pintype "passive"))
      (node (ref "U101") (pin "13") (pinfunction "OSC_OUT_13") (pintype "output"))
      (node (ref "X101") (pin "1") (pinfunction "1_1") (pintype "bidirectional"))
    )
    (net (code "70") (name "Net-(C504-1)") (class "Default")
      (node (ref "C504") (pin "P$1") (pinfunction "1_P$1") (pintype "passive"))
      (node (ref "U501") (pin "14") (pinfunction "PLLFILT_14") (pintype "bidirectional"))
    )
    (net (code "71") (name "Net-(C505-1)") (class "Default")
      (node (ref "C505") (pin "P$1") (pinfunction "1_P$1") (pintype "passive"))
      (node (ref "U502") (pin "14") (pinfunction "CAP_14") (pintype "bidirectional"))
    )
    (net (code "72") (name "Net-(C509-1)") (class "Default")
      (node (ref "C509") (pin "P$1") (pinfunction "1_P$1") (pintype "passive"))
      (node (ref "U$501") (pin "15") (pinfunction "C1_15") (pintype "bidirectional"))
    )
    (net (code "73") (name "Net-(C510-1)") (class "Default")
      (node (ref "C510") (pin "P$1") (pinfunction "1_P$1") (pintype "passive"))
      (node (ref "U$501") (pin "2") (pinfunction "SETC_2") (pintype "bidirectional"))
    )
    (net (code "74") (name "Net-(C510-2)") (class "Default")
      (node (ref "C510") (pin "P$2") (pinfunction "2_P$2") (pintype "passive"))
      (node (ref "U$501") (pin "3") (pinfunction "SETP_3") (pintype "bidirectional"))
    )
    (net (code "75") (name "Net-(C601-1)") (class "Default")
      (node (ref "C601") (pin "P$1") (pinfunction "1_P$1") (pintype "passive"))
      (node (ref "L603") (pin "P$2") (pinfunction "P$2_P$2") (pintype "bidirectional"))
      (node (ref "R603") (pin "P$2") (pinfunction "2_P$2") (pintype "passive"))
      (node (ref "U$605") (pin "1") (pinfunction "VIN_1") (pintype "bidirectional"))
      (node (ref "U$605") (pin "4") (pinfunction "EN2_4") (pintype "bidirectional"))
    )
    (net (code "76") (name "Net-(C602-2)") (class "Default")
      (node (ref "C602") (pin "P$2") (pinfunction "2_P$2") (pintype "passive"))
      (node (ref "U$605") (pin "6") (pinfunction "CSET_6") (pintype "bidirectional"))
    )
    (net (code "77") (name "Net-(C611-1)") (class "Default")
      (node (ref "C611") (pin "P$1") (pinfunction "1_P$1") (pintype "passive"))
      (node (ref "U101") (pin "49") (pinfunction "VCAP_1_49") (pintype "power_in"))
    )
    (net (code "78") (name "Net-(C613-1)") (class "Default")
      (node (ref "C613") (pin "P$1") (pinfunction "1_P$1") (pintype "passive"))
      (node (ref "U101") (pin "73") (pinfunction "VCAP_2_73") (pintype "power_in"))
    )
    (net (code "79") (name "Net-(C703-1)") (class "Default")
      (node (ref "C703") (pin "P$1") (pinfunction "1_P$1") (pintype "passive"))
      (node (ref "J701") (pin "P$1") (pinfunction "1_P$1") (pintype "passive"))
      (node (ref "R703") (pin "P$1") (pinfunction "1_P$1") (pintype "passive"))
      (node (ref "U702") (pin "1") (pinfunction "OUT_1") (pintype "output"))
    )
    (net (code "80") (name "Net-(C704-1)") (class "Default")
      (node (ref "C704") (pin "P$1") (pinfunction "1_P$1") (pintype "passive"))
      (node (ref "R705") (pin "P$1") (pinfunction "1_P$1") (pintype "passive"))
      (node (ref "U702") (pin "6") (pinfunction "VCC_6") (pintype "bidirectional"))
    )
    (net (code "81") (name "Net-(C805-1)") (class "Default")
      (node (ref "C805") (pin "P$1") (pinfunction "1_P$1") (pintype "passive"))
      (node (ref "U801") (pin "5") (pinfunction "PD0/OSC<=_5") (pintype "bidirectional"))
      (node (ref "X801") (pin "3") (pinfunction "3_3") (pintype "bidirectional"))
    )
    (net (code "82") (name "Net-(C806-2)") (class "Default")
      (node (ref "C806") (pin "P$2") (pinfunction "2_P$2") (pintype "passive"))
      (node (ref "U801") (pin "6") (pinfunction "PD1/OSC=>_6") (pintype "bidirectional"))
      (node (ref "X801") (pin "1") (pinfunction "1_1") (pintype "bidirectional"))
    )
    (net (code "83") (name "Net-(C1002-1)") (class "Default")
      (node (ref "C1002") (pin "P$1") (pinfunction "1_P$1") (pintype "passive"))
      (node (ref "U$1002") (pin "6") (pinfunction "CSET_6") (pintype "bidirectional"))
    )
    (net (code "84") (name "Net-(D1-C)") (class "Default")
      (node (ref "D1") (pin "CATHODE") (pinfunction "C_CATHODE") (pintype "passive"))
      (node (ref "L901") (pin "P$1") (pinfunction "P$1_P$1") (pintype "bidirectional"))
      (node (ref "U$6") (pin "C") (pinfunction "C_C") (pintype "passive"))
    )
    (net (code "85") (name "Net-(D1001-A1)") (class "Default")
      (node (ref "D1001") (pin "1") (pinfunction "A1_1") (pintype "passive"))
      (node (ref "F2") (pin "2") (pinfunction "2_2") (pintype "bidirectional"))
    )
    (net (code "86") (name "Net-(D1001-A2)") (class "Default")
      (node (ref "D1001") (pin "2") (pinfunction "A2_2") (pintype "passive"))
      (node (ref "U$1001") (pin "8") (pinfunction "OUT_8") (pintype "bidirectional"))
    )
    (net (code "87") (name "Net-(J201-1)") (class "Default")
      (node (ref "J201") (pin "P$1") (pinfunction "1_P$1") (pintype "passive"))
      (node (ref "L201") (pin "P$2") (pinfunction "P$2_P$2") (pintype "bidirectional"))
      (node (ref "U$201") (pin "C") (pinfunction "C_C") (pintype "passive"))
    )
    (net (code "88") (name "Net-(J202-1)") (class "Default")
      (node (ref "J202") (pin "P$1") (pinfunction "1_P$1") (pintype "passive"))
      (node (ref "L202") (pin "P$2") (pinfunction "P$2_P$2") (pintype "bidirectional"))
      (node (ref "U$202") (pin "C") (pinfunction "C_C") (pintype "passive"))
    )
    (net (code "89") (name "Net-(J203-1)") (class "Default")
      (node (ref "J203") (pin "P$1") (pinfunction "1_P$1") (pintype "passive"))
      (node (ref "J204") (pin "P$1") (pinfunction "1_P$1") (pintype "passive"))
      (node (ref "L203") (pin "P$2") (pinfunction "P$2_P$2") (pintype "bidirectional"))
      (node (ref "U$203") (pin "C") (pinfunction "C_C") (pintype "passive"))
    )
    (net (code "90") (name "Net-(J203-4)") (class "Default")
      (node (ref "J203") (pin "P$4") (pinfunction "4_P$4") (pintype "passive"))
      (node (ref "R12") (pin "P$2") (pinfunction "2_P$2") (pintype "passive"))
    )
    (net (code "91") (name "Net-(J203-5)") (class "Default")
      (node (ref "J203") (pin "P$5") (pinfunction "5_P$5") (pintype "passive"))
      (node (ref "R13") (pin "P$2") (pinfunction "2_P$2") (pintype "passive"))
    )
    (net (code "92") (name "Net-(J301-2)") (class "Default")
      (node (ref "J301") (pin "D-") (pinfunction "2_D-") (pintype "bidirectional"))
      (node (ref "J302") (pin "P$3") (pinfunction "3_P$3") (pintype "passive"))
      (node (ref "U$301") (pin "1") (pinfunction "D1I_1") (pintype "bidirectional"))
    )
    (net (code "93") (name "Net-(J301-3)") (class "Default")
      (node (ref "J301") (pin "D+") (pinfunction "3_D+") (pintype "bidirectional"))
      (node (ref "J302") (pin "P$2") (pinfunction "2_P$2") (pintype "passive"))
      (node (ref "U$301") (pin "3") (pinfunction "D2I_3") (pintype "bidirectional"))
    )
    (net (code "94") (name "Net-(J401-1)") (class "Default")
      (node (ref "J401") (pin "P$1") (pinfunction "1_P$1") (pintype "passive"))
      (node (ref "J402") (pin "P$1") (pinfunction "1_P$1") (pintype "passive"))
      (node (ref "L401") (pin "P$2") (pinfunction "P$2_P$2") (pintype "bidirectional"))
      (node (ref "U$401") (pin "C") (pinfunction "C_C") (pintype "passive"))
    )
    (net (code "95") (name "Net-(J401-2)") (class "Default")
      (node (ref "J401") (pin "P$2") (pinfunction "2_P$2") (pintype "passive"))
      (node (ref "R404") (pin "P$2") (pinfunction "2_P$2") (pintype "passive"))
    )
    (net (code "96") (name "Net-(J401-3)") (class "Default")
      (node (ref "J401") (pin "P$3") (pinfunction "3_P$3") (pintype "passive"))
      (node (ref "R405") (pin "P$2") (pinfunction "2_P$2") (pintype "passive"))
    )
    (net (code "97") (name "Net-(J403-1)") (class "Default")
      (node (ref "J403") (pin "P$1") (pinfunction "1_P$1") (pintype "passive"))
      (node (ref "L402") (pin "P$2") (pinfunction "P$2_P$2") (pintype "bidirectional"))
      (node (ref "U$402") (pin "C") (pinfunction "C_C") (pintype "passive"))
    )
    (net (code "98") (name "Net-(J404-1)") (class "Default")
      (node (ref "J404") (pin "P$1") (pinfunction "1_P$1") (pintype "passive"))
      (node (ref "L404") (pin "P$2") (pinfunction "P$2_P$2") (pintype "bidirectional"))
      (node (ref "U$403") (pin "C") (pinfunction "C_C") (pintype "passive"))
    )
    (net (code "99") (name "Net-(J404-2)") (class "Default")
      (node (ref "J404") (pin "P$2") (pinfunction "2_P$2") (pintype "passive"))
      (node (ref "R407") (pin "P$2") (pinfunction "2_P$2") (pintype "passive"))
    )
    (net (code "100") (name "Net-(J404-4)") (class "Default")
      (node (ref "J404") (pin "P$4") (pinfunction "4_P$4") (pintype "passive"))
      (node (ref "R408") (pin "P$2") (pinfunction "2_P$2") (pintype "passive"))
    )
    (net (code "101") (name "Net-(J405-1)") (class "Default")
      (node (ref "J405") (pin "P$1") (pinfunction "1_P$1") (pintype "passive"))
      (node (ref "L403") (pin "P$2") (pinfunction "P$2_P$2") (pintype "bidirectional"))
      (node (ref "U$404") (pin "C") (pinfunction "C_C") (pintype "passive"))
    )
    (net (code "102") (name "Net-(J601-3)") (class "Default")
      (node (ref "J601") (pin "P$3") (pinfunction "3_P$3") (pintype "passive"))
      (node (ref "L601") (pin "P$1") (pinfunction "P$1_P$1") (pintype "bidirectional"))
    )
    (net (code "103") (name "Net-(J601-4)") (class "Default")
      (node (ref "J601") (pin "P$4") (pinfunction "4_P$4") (pintype "passive"))
      (node (ref "L602") (pin "P$1") (pinfunction "P$1_P$1") (pintype "bidirectional"))
    )
    (net (code "104") (name "Net-(J702-2)") (class "Default")
      (node (ref "J702") (pin "P$2") (pinfunction "2_P$2") (pintype "passive"))
      (node (ref "R710") (pin "P$1") (pinfunction "1_P$1") (pintype "passive"))
    )
    (net (code "105") (name "Net-(J901A-S)") (class "Default")
      (node (ref "J901") (pin "1") (pinfunction "S_1") (pintype "passive"))
      (node (ref "R909") (pin "P$2") (pinfunction "2_P$2") (pintype "passive"))
    )
    (net (code "106") (name "Net-(J901B-S)") (class "Default")
      (node (ref "J901") (pin "10") (pinfunction "S_10") (pintype "passive"))
      (node (ref "R914") (pin "P$2") (pinfunction "2_P$2") (pintype "passive"))
    )
    (net (code "107") (name "Net-(J901C-S)") (class "Default")
      (node (ref "J901") (pin "13") (pinfunction "S_13") (pintype "passive"))
      (node (ref "R906") (pin "P$2") (pinfunction "2_P$2") (pintype "passive"))
    )
    (net (code "108") (name "Net-(J901D-S)") (class "Default")
      (node (ref "J901") (pin "16") (pinfunction "S_16") (pintype "passive"))
      (node (ref "R915") (pin "P$2") (pinfunction "2_P$2") (pintype "passive"))
    )
    (net (code "109") (name "Net-(J901E-S)") (class "Default")
      (node (ref "J901") (pin "19") (pinfunction "S_19") (pintype "passive"))
      (node (ref "R907") (pin "P$2") (pinfunction "2_P$2") (pintype "passive"))
    )
    (net (code "110") (name "Net-(J901G-S)") (class "Default")
      (node (ref "J901") (pin "22") (pinfunction "S_22") (pintype "passive"))
      (node (ref "R916") (pin "P$2") (pinfunction "2_P$2") (pintype "passive"))
    )
    (net (code "111") (name "Net-(J901H-S)") (class "Default")
      (node (ref "J901") (pin "25") (pinfunction "S_25") (pintype "passive"))
      (node (ref "R908") (pin "P$2") (pinfunction "2_P$2") (pintype "passive"))
    )
    (net (code "112") (name "Net-(J901I-S)") (class "Default")
      (node (ref "J901") (pin "28") (pinfunction "S_28") (pintype "passive"))
      (node (ref "R917") (pin "P$2") (pinfunction "2_P$2") (pintype "passive"))
    )
    (net (code "113") (name "Net-(J901J-S)") (class "Default")
      (node (ref "J901") (pin "31") (pinfunction "S_31") (pintype "passive"))
      (node (ref "R902") (pin "P$2") (pinfunction "2_P$2") (pintype "passive"))
    )
    (net (code "114") (name "Net-(J901K-S)") (class "Default")
      (node (ref "J901") (pin "34") (pinfunction "S_34") (pintype "passive"))
      (node (ref "R911") (pin "P$2") (pinfunction "2_P$2") (pintype "passive"))
    )
    (net (code "115") (name "Net-(J901L-S)") (class "Default")
      (node (ref "J901") (pin "37") (pinfunction "S_37") (pintype "passive"))
      (node (ref "R903") (pin "P$2") (pinfunction "2_P$2") (pintype "passive"))
    )
    (net (code "116") (name "Net-(J901M-S)") (class "Default")
      (node (ref "J901") (pin "4") (pinfunction "S_4") (pintype "passive"))
      (node (ref "R910") (pin "P$2") (pinfunction "2_P$2") (pintype "passive"))
    )
    (net (code "117") (name "Net-(J901N-S)") (class "Default")
      (node (ref "J901") (pin "40") (pinfunction "S_40") (pintype "passive"))
      (node (ref "R912") (pin "P$2") (pinfunction "2_P$2") (pintype "passive"))
    )
    (net (code "118") (name "Net-(J901O-S)") (class "Default")
      (node (ref "J901") (pin "43") (pinfunction "S_43") (pintype "passive"))
      (node (ref "R904") (pin "P$2") (pinfunction "2_P$2") (pintype "passive"))
    )
    (net (code "119") (name "Net-(J901P-S)") (class "Default")
      (node (ref "J901") (pin "46") (pinfunction "S_46") (pintype "passive"))
      (node (ref "R913") (pin "P$2") (pinfunction "2_P$2") (pintype "passive"))
    )
    (net (code "120") (name "Net-(J901Q-S)") (class "Default")
      (node (ref "J901") (pin "7") (pinfunction "S_7") (pintype "passive"))
      (node (ref "R905") (pin "P$2") (pinfunction "2_P$2") (pintype "passive"))
    )
    (net (code "121") (name "Net-(L701-2)") (class "Default")
      (node (ref "L701") (pin "P$2") (pinfunction "2_P$2") (pintype "passive"))
      (node (ref "U702") (pin "5") (pinfunction "SW_5") (pintype "passive"))
    )
    (net (code "122") (name "Net-(R1-2)") (class "Default")
      (node (ref "R1") (pin "P$2") (pinfunction "2_P$2") (pintype "passive"))
      (node (ref "R2") (pin "P$1") (pinfunction "1_P$1") (pintype "passive"))
      (node (ref "U$2") (pin "P$1") (pinfunction "UV1_P$1") (pintype "bidirectional"))
    )
    (net (code "123") (name "Net-(R2-2)") (class "Default")
      (node (ref "R2") (pin "P$2") (pinfunction "2_P$2") (pintype "passive"))
      (node (ref "R5") (pin "P$1") (pinfunction "1_P$1") (pintype "passive"))
      (node (ref "U$2") (pin "P$2") (pinfunction "OV1_P$2") (pintype "bidirectional"))
    )
    (net (code "124") (name "Net-(R3-1)") (class "Default")
      (node (ref "R3") (pin "P$1") (pinfunction "1_P$1") (pintype "passive"))
      (node (ref "R707") (pin "P$2") (pinfunction "2_P$2") (pintype "passive"))
    )
    (net (code "125") (name "Net-(R3-2)") (class "Default")
      (node (ref "LED701") (pin "C") (pinfunction "C_C") (pintype "passive"))
      (node (ref "R3") (pin "P$2") (pinfunction "2_P$2") (pintype "passive"))
    )
    (net (code "126") (name "Net-(R4-1)") (class "Default")
      (node (ref "R4") (pin "P$1") (pinfunction "1_P$1") (pintype "passive"))
      (node (ref "R709") (pin "P$2") (pinfunction "2_P$2") (pintype "passive"))
    )
    (net (code "127") (name "Net-(R4-2)") (class "Default")
      (node (ref "LED703") (pin "C") (pinfunction "C_C") (pintype "passive"))
      (node (ref "R4") (pin "P$2") (pinfunction "2_P$2") (pintype "passive"))
    )
    (net (code "128") (name "Net-(R6-2)") (class "Default")
      (node (ref "R6") (pin "P$2") (pinfunction "2_P$2") (pintype "passive"))
      (node (ref "R7") (pin "P$1") (pinfunction "1_P$1") (pintype "passive"))
      (node (ref "U$2") (pin "P$5") (pinfunction "UV3_P$5") (pintype "bidirectional"))
    )
    (net (code "129") (name "Net-(R7-2)") (class "Default")
      (node (ref "R7") (pin "P$2") (pinfunction "2_P$2") (pintype "passive"))
      (node (ref "R8") (pin "P$1") (pinfunction "1_P$1") (pintype "passive"))
      (node (ref "U$2") (pin "P$6") (pinfunction "OV3_P$6") (pintype "bidirectional"))
    )
    (net (code "130") (name "Net-(R10-1)") (class "Default")
      (node (ref "R10") (pin "P$1") (pinfunction "1_P$1") (pintype "passive"))
      (node (ref "R9") (pin "P$2") (pinfunction "2_P$2") (pintype "passive"))
      (node (ref "U$2") (pin "P$3") (pinfunction "UV2_P$3") (pintype "bidirectional"))
    )
    (net (code "131") (name "Net-(R10-2)") (class "Default")
      (node (ref "R10") (pin "P$2") (pinfunction "2_P$2") (pintype "passive"))
      (node (ref "R11") (pin "P$1") (pinfunction "1_P$1") (pintype "passive"))
      (node (ref "U$2") (pin "P$4") (pinfunction "OV2_P$4") (pintype "bidirectional"))
    )
    (net (code "132") (name "Net-(R101-1)") (class "Default")
      (node (ref "R101") (pin "P$1") (pinfunction "1_P$1") (pintype "passive"))
      (node (ref "U101") (pin "69") (pinfunction "PA10_69") (pintype "bidirectional"))
    )
    (net (code "133") (name "Net-(R102-1)") (class "Default")
      (node (ref "R102") (pin "P$1") (pinfunction "1_P$1") (pintype "passive"))
      (node (ref "U101") (pin "37") (pinfunction "PB2_37") (pintype "bidirectional"))
    )
    (net (code "134") (name "Net-(R201-1)") (class "Default")
      (node (ref "R201") (pin "P$1") (pinfunction "1_P$1") (pintype "passive"))
      (node (ref "U201") (pin "20") (pinfunction "B1_20") (pintype "bidirectional"))
    )
    (net (code "135") (name "Net-(R202-1)") (class "Default")
      (node (ref "R202") (pin "P$1") (pinfunction "1_P$1") (pintype "passive"))
      (node (ref "U201") (pin "17") (pinfunction "B3_17") (pintype "bidirectional"))
    )
    (net (code "136") (name "Net-(R203-1)") (class "Default")
      (node (ref "R203") (pin "P$1") (pinfunction "1_P$1") (pintype "passive"))
      (node (ref "U201") (pin "15") (pinfunction "B5_15") (pintype "bidirectional"))
    )
    (net (code "137") (name "Net-(R204-1)") (class "Default")
      (node (ref "R204") (pin "P$1") (pinfunction "1_P$1") (pintype "passive"))
      (node (ref "U201") (pin "13") (pinfunction "B7_13") (pintype "bidirectional"))
    )
    (net (code "138") (name "Net-(R205-1)") (class "Default")
      (node (ref "R205") (pin "P$1") (pinfunction "1_P$1") (pintype "passive"))
      (node (ref "U202") (pin "17") (pinfunction "B3_17") (pintype "bidirectional"))
    )
    (net (code "139") (name "Net-(R206-1)") (class "Default")
      (node (ref "R206") (pin "P$1") (pinfunction "1_P$1") (pintype "passive"))
      (node (ref "U202") (pin "15") (pinfunction "B5_15") (pintype "bidirectional"))
    )
    (net (code "140") (name "Net-(R207-1)") (class "Default")
      (node (ref "R207") (pin "P$1") (pinfunction "1_P$1") (pintype "passive"))
      (node (ref "U202") (pin "13") (pinfunction "B7_13") (pintype "bidirectional"))
    )
    (net (code "141") (name "Net-(R208-1)") (class "Default")
      (node (ref "R208") (pin "P$1") (pinfunction "1_P$1") (pintype "passive"))
      (node (ref "U201") (pin "18") (pinfunction "B2_18") (pintype "bidirectional"))
    )
    (net (code "142") (name "Net-(R209-1)") (class "Default")
      (node (ref "R209") (pin "P$1") (pinfunction "1_P$1") (pintype "passive"))
      (node (ref "U201") (pin "16") (pinfunction "B4_16") (pintype "bidirectional"))
    )
    (net (code "143") (name "Net-(R210-1)") (class "Default")
      (node (ref "R210") (pin "P$1") (pinfunction "1_P$1") (pintype "passive"))
      (node (ref "U201") (pin "14") (pinfunction "B6_14") (pintype "bidirectional"))
    )
    (net (code "144") (name "Net-(R211-1)") (class "Default")
      (node (ref "R211") (pin "P$1") (pinfunction "1_P$1") (pintype "passive"))
      (node (ref "U201") (pin "12") (pinfunction "B8_12") (pintype "bidirectional"))
    )
    (net (code "145") (name "Net-(R212-1)") (class "Default")
      (node (ref "R212") (pin "P$1") (pinfunction "1_P$1") (pintype "passive"))
      (node (ref "U202") (pin "16") (pinfunction "B4_16") (pintype "bidirectional"))
    )
    (net (code "146") (name "Net-(R213-1)") (class "Default")
      (node (ref "R213") (pin "P$1") (pinfunction "1_P$1") (pintype "passive"))
      (node (ref "U202") (pin "14") (pinfunction "B6_14") (pintype "bidirectional"))
    )
    (net (code "147") (name "Net-(R214-1)") (class "Default")
      (node (ref "R214") (pin "P$1") (pinfunction "1_P$1") (pintype "passive"))
      (node (ref "U202") (pin "12") (pinfunction "B8_12") (pintype "bidirectional"))
    )
    (net (code "148") (name "Net-(R602-1)") (class "Default")
      (node (ref "R602") (pin "P$1") (pinfunction "1_P$1") (pintype "passive"))
      (node (ref "U$602") (pin "7") (pinfunction "ILIM_7") (pintype "bidirectional"))
    )
    (net (code "149") (name "Net-(R604-2)") (class "Default")
      (node (ref "L601") (pin "P$2") (pinfunction "P$2_P$2") (pintype "bidirectional"))
      (node (ref "R604") (pin "P$2") (pinfunction "2_P$2") (pintype "passive"))
    )
    (net (code "150") (name "Net-(R605-2)") (class "Default")
      (node (ref "L602") (pin "P$2") (pinfunction "P$2_P$2") (pintype "bidirectional"))
      (node (ref "R605") (pin "P$2") (pinfunction "2_P$2") (pintype "passive"))
    )
    (net (code "151") (name "Net-(R606-1)") (class "Default")
      (node (ref "R606") (pin "P$1") (pinfunction "1_P$1") (pintype "passive"))
      (node (ref "U$604") (pin "7") (pinfunction "ILIM_7") (pintype "bidirectional"))
    )
    (net (code "152") (name "Net-(R701-1)") (class "Default")
      (node (ref "R701") (pin "P$1") (pinfunction "1_P$1") (pintype "passive"))
      (node (ref "U702") (pin "7") (pinfunction "+IN_7") (pintype "input"))
    )
    (net (code "153") (name "Net-(R702-1)") (class "Default")
      (node (ref "R702") (pin "P$1") (pinfunction "1_P$1") (pintype "passive"))
      (node (ref "R703") (pin "P$2") (pinfunction "2_P$2") (pintype "passive"))
      (node (ref "U702") (pin "8") (pinfunction "-IN_8") (pintype "input"))
    )
    (net (code "154") (name "Net-(R704-2)") (class "Default")
      (node (ref "R704") (pin "P$2") (pinfunction "2_P$2") (pintype "passive"))
      (node (ref "U701") (pin "6") (pinfunction "REXT_6") (pintype "bidirectional"))
    )
    (net (code "155") (name "Net-(R705-2)") (class "Default")
      (node (ref "R705") (pin "P$2") (pinfunction "2_P$2") (pintype "passive"))
      (node (ref "R706") (pin "P$1") (pinfunction "1_P$1") (pintype "passive"))
      (node (ref "U702") (pin "2") (pinfunction "FB_2") (pintype "bidirectional"))
    )
    (net (code "156") (name "Net-(R708-2)") (class "Default")
      (node (ref "LED702") (pin "C") (pinfunction "C_C") (pintype "passive"))
      (node (ref "R708") (pin "P$2") (pinfunction "2_P$2") (pintype "passive"))
    )
    (net (code "157") (name "Net-(R711-2)") (class "Default")
      (node (ref "LED704") (pin "C") (pinfunction "C_C") (pintype "passive"))
      (node (ref "R711") (pin "P$2") (pinfunction "2_P$2") (pintype "passive"))
    )
    (net (code "158") (name "Net-(R712-2)") (class "Default")
      (node (ref "LED705") (pin "C") (pinfunction "C_C") (pintype "passive"))
      (node (ref "R712") (pin "P$2") (pinfunction "2_P$2") (pintype "passive"))
    )
    (net (code "159") (name "Net-(R802-1)") (class "Default")
      (node (ref "R802") (pin "P$1") (pinfunction "1_P$1") (pintype "passive"))
      (node (ref "U801") (pin "20") (pinfunction "PB2_20") (pintype "bidirectional"))
    )
    (net (code "160") (name "Net-(R803-1)") (class "Default")
      (node (ref "R803") (pin "P$1") (pinfunction "1_P$1") (pintype "passive"))
      (node (ref "U801") (pin "12") (pinfunction "PA2_12") (pintype "bidirectional"))
    )
    (net (code "161") (name "Net-(R804-1)") (class "Default")
      (node (ref "R804") (pin "P$1") (pinfunction "1_P$1") (pintype "passive"))
      (node (ref "U801") (pin "13") (pinfunction "PA3_13") (pintype "bidirectional"))
    )
    (net (code "162") (name "Net-(R901-2)") (class "Default")
      (node (ref "R901") (pin "P$2") (pinfunction "2_P$2") (pintype "passive"))
      (node (ref "R910") (pin "P$1") (pinfunction "1_P$1") (pintype "passive"))
      (node (ref "U$902") (pin "C") (pinfunction "C_C") (pintype "passive"))
      (node (ref "U903") (pin "3") (pinfunction "2Y_3") (pintype "bidirectional"))
    )
    (net (code "163") (name "Net-(R902-1)") (class "Default")
      (node (ref "R902") (pin "P$1") (pinfunction "1_P$1") (pintype "passive"))
      (node (ref "U901") (pin "20") (pinfunction "B1_20") (pintype "bidirectional"))
    )
    (net (code "164") (name "Net-(R903-1)") (class "Default")
      (node (ref "R903") (pin "P$1") (pinfunction "1_P$1") (pintype "passive"))
      (node (ref "U901") (pin "17") (pinfunction "B3_17") (pintype "bidirectional"))
    )
    (net (code "165") (name "Net-(R904-1)") (class "Default")
      (node (ref "R904") (pin "P$1") (pinfunction "1_P$1") (pintype "passive"))
      (node (ref "U901") (pin "15") (pinfunction "B5_15") (pintype "bidirectional"))
    )
    (net (code "166") (name "Net-(R905-1)") (class "Default")
      (node (ref "R905") (pin "P$1") (pinfunction "1_P$1") (pintype "passive"))
      (node (ref "U902") (pin "20") (pinfunction "B1_20") (pintype "bidirectional"))
    )
    (net (code "167") (name "Net-(R906-1)") (class "Default")
      (node (ref "R906") (pin "P$1") (pinfunction "1_P$1") (pintype "passive"))
      (node (ref "U902") (pin "17") (pinfunction "B3_17") (pintype "bidirectional"))
    )
    (net (code "168") (name "Net-(R907-1)") (class "Default")
      (node (ref "R907") (pin "P$1") (pinfunction "1_P$1") (pintype "passive"))
      (node (ref "U902") (pin "15") (pinfunction "B5_15") (pintype "bidirectional"))
    )
    (net (code "169") (name "Net-(R908-1)") (class "Default")
      (node (ref "R908") (pin "P$1") (pinfunction "1_P$1") (pintype "passive"))
      (node (ref "U902") (pin "13") (pinfunction "B7_13") (pintype "bidirectional"))
    )
    (net (code "170") (name "Net-(R911-1)") (class "Default")
      (node (ref "R911") (pin "P$1") (pinfunction "1_P$1") (pintype "passive"))
      (node (ref "U901") (pin "18") (pinfunction "B2_18") (pintype "bidirectional"))
    )
    (net (code "171") (name "Net-(R912-1)") (class "Default")
      (node (ref "R912") (pin "P$1") (pinfunction "1_P$1") (pintype "passive"))
      (node (ref "U901") (pin "16") (pinfunction "B4_16") (pintype "bidirectional"))
    )
    (net (code "172") (name "Net-(R913-1)") (class "Default")
      (node (ref "R913") (pin "P$1") (pinfunction "1_P$1") (pintype "passive"))
      (node (ref "U901") (pin "14") (pinfunction "B6_14") (pintype "bidirectional"))
    )
    (net (code "173") (name "Net-(R914-1)") (class "Default")
      (node (ref "R914") (pin "P$1") (pinfunction "1_P$1") (pintype "passive"))
      (node (ref "U902") (pin "18") (pinfunction "B2_18") (pintype "bidirectional"))
    )
    (net (code "174") (name "Net-(R915-1)") (class "Default")
      (node (ref "R915") (pin "P$1") (pinfunction "1_P$1") (pintype "passive"))
      (node (ref "U902") (pin "16") (pinfunction "B4_16") (pintype "bidirectional"))
    )
    (net (code "175") (name "Net-(R916-1)") (class "Default")
      (node (ref "R916") (pin "P$1") (pinfunction "1_P$1") (pintype "passive"))
      (node (ref "U902") (pin "14") (pinfunction "B6_14") (pintype "bidirectional"))
    )
    (net (code "176") (name "Net-(R917-1)") (class "Default")
      (node (ref "R917") (pin "P$1") (pinfunction "1_P$1") (pintype "passive"))
      (node (ref "U902") (pin "12") (pinfunction "B8_12") (pintype "bidirectional"))
    )
    (net (code "177") (name "Net-(R918-2)") (class "Default")
      (node (ref "R918") (pin "P$2") (pinfunction "2_P$2") (pintype "passive"))
      (node (ref "R922") (pin "P$1") (pinfunction "1_P$1") (pintype "passive"))
    )
    (net (code "178") (name "Net-(R1001-2)") (class "Default")
      (node (ref "R1001") (pin "P$2") (pinfunction "2_P$2") (pintype "passive"))
      (node (ref "U$1001") (pin "7") (pinfunction "ILIM_7") (pintype "bidirectional"))
    )
    (net (code "179") (name "Net-(U$2-G1)") (class "Default")
      (node (ref "U$2") (pin "P$17") (pinfunction "G1_P$17") (pintype "bidirectional"))
      (node (ref "U$3") (pin "P$2") (pinfunction "G_P$2") (pintype "passive"))
      (node (ref "U$3") (pin "P$4") (pinfunction "G_P$4") (pintype "passive"))
    )
    (net (code "180") (name "Net-(U$2-G2)") (class "Default")
      (node (ref "U$2") (pin "P$15") (pinfunction "G2_P$15") (pintype "bidirectional"))
      (node (ref "U$4") (pin "P$2") (pinfunction "G_P$2") (pintype "passive"))
      (node (ref "U$4") (pin "P$4") (pinfunction "G_P$4") (pintype "passive"))
    )
    (net (code "181") (name "Net-(U$2-G3)") (class "Default")
      (node (ref "U$2") (pin "P$13") (pinfunction "G3_P$13") (pintype "bidirectional"))
      (node (ref "U$5") (pin "P$2") (pinfunction "G_P$2") (pintype "passive"))
      (node (ref "U$5") (pin "P$4") (pinfunction "G_P$4") (pintype "passive"))
    )
    (net (code "182") (name "Net-(U$2-VS1)") (class "Default")
      (node (ref "U$2") (pin "P$18") (pinfunction "VS1_P$18") (pintype "bidirectional"))
      (node (ref "U$3") (pin "P$1") (pinfunction "S_P$1") (pintype "passive"))
      (node (ref "U$3") (pin "P$3") (pinfunction "S_P$3") (pintype "passive"))
    )
    (net (code "183") (name "Net-(U$2-VS2)") (class "Default")
      (node (ref "U$2") (pin "P$16") (pinfunction "VS2_P$16") (pintype "bidirectional"))
      (node (ref "U$4") (pin "P$1") (pinfunction "S_P$1") (pintype "passive"))
      (node (ref "U$4") (pin "P$3") (pinfunction "S_P$3") (pintype "passive"))
    )
    (net (code "184") (name "Net-(U$2-VS3)") (class "Default")
      (node (ref "U$2") (pin "P$14") (pinfunction "VS3_P$14") (pintype "bidirectional"))
      (node (ref "U$5") (pin "P$1") (pinfunction "S_P$1") (pintype "passive"))
      (node (ref "U$5") (pin "P$3") (pinfunction "S_P$3") (pintype "passive"))
    )
    (net (code "185") (name "Net-(U701-OUT0)") (class "Default")
      (node (ref "U701") (pin "9") (pinfunction "OUT0_9") (pintype "open_collector"))
      (node (ref "U703") (pin "C1") (pinfunction "C_C1") (pintype "passive"))
    )
    (net (code "186") (name "Net-(U701-OUT1)") (class "Default")
      (node (ref "U701") (pin "8") (pinfunction "OUT1_8") (pintype "open_collector"))
      (node (ref "U703") (pin "C2") (pinfunction "C_C2") (pintype "passive"))
    )
    (net (code "187") (name "Net-(U701-OUT2)") (class "Default")
      (node (ref "U701") (pin "7") (pinfunction "OUT2_7") (pintype "open_collector"))
      (node (ref "U703") (pin "C3") (pinfunction "C_C3") (pintype "passive"))
    )
    (net (code "188") (name "OTG_FS_DM") (class "Default")
      (node (ref "U$301") (pin "6") (pinfunction "D1O_6") (pintype "bidirectional"))
      (node (ref "U101") (pin "70") (pinfunction "PA11_70") (pintype "bidirectional"))
    )
    (net (code "189") (name "OTG_FS_DP") (class "Default")
      (node (ref "U$301") (pin "4") (pinfunction "D2O_4") (pintype "bidirectional"))
      (node (ref "U101") (pin "71") (pinfunction "PA12_71") (pintype "bidirectional"))
    )
    (net (code "190") (name "PPM_INPUT") (class "Default")
      (node (ref "R909") (pin "P$1") (pinfunction "1_P$1") (pintype "passive"))
      (node (ref "U$901") (pin "C") (pinfunction "C_C") (pintype "passive"))
      (node (ref "U801") (pin "29") (pinfunction "PA8_29") (pintype "bidirectional"))
      (node (ref "U903") (pin "2") (pinfunction "1A_2") (pintype "bidirectional"))
    )
    (net (code "191") (name "PRESSURE_SENS") (class "Default")
      (node (ref "C401") (pin "P$1") (pinfunction "1_P$1") (pintype "passive"))
      (node (ref "R403") (pin "P$2") (pinfunction "2_P$2") (pintype "passive"))
      (node (ref "R406") (pin "P$1") (pinfunction "1_P$1") (pintype "passive"))
      (node (ref "U101") (pin "34") (pinfunction "PC5_34") (pintype "bidirectional"))
    )
    (net (code "192") (name "PRESSURE_SENS_IN") (class "Default")
      (node (ref "ADC_PR") (pin "P$1") (pinfunction "P$1_P$1") (pintype "passive"))
      (node (ref "J402") (pin "P$2") (pinfunction "2_P$2") (pintype "passive"))
      (node (ref "R406") (pin "P$2") (pinfunction "2_P$2") (pintype "passive"))
    )
    (net (code "193") (name "RSSI_IN") (class "Default")
      (node (ref "R901") (pin "P$1") (pinfunction "1_P$1") (pintype "passive"))
      (node (ref "U801") (pin "15") (pinfunction "PA5_15") (pintype "bidirectional"))
      (node (ref "U801") (pin "33") (pinfunction "PA12_33") (pintype "bidirectional"))
    )
    (net (code "194") (name "SAFETY") (class "Default")
      (node (ref "J702") (pin "P$3") (pinfunction "3_P$3") (pintype "passive"))
      (node (ref "R713") (pin "P$1") (pinfunction "1_P$1") (pintype "passive"))
      (node (ref "U801") (pin "41") (pinfunction "PB5_41") (pintype "bidirectional"))
    )
    (net (code "195") (name "SBUS_INPUT") (class "Default")
      (node (ref "U801") (pin "22") (pinfunction "PB11_22") (pintype "bidirectional"))
      (node (ref "U903") (pin "6") (pinfunction "1Y_6") (pintype "bidirectional"))
    )
    (net (code "196") (name "SBUS_OUTPUT") (class "Default")
      (node (ref "U801") (pin "21") (pinfunction "PB10_21") (pintype "bidirectional"))
      (node (ref "U903") (pin "5") (pinfunction "2A_5") (pintype "bidirectional"))
    )
    (net (code "197") (name "SDIO_CK") (class "Default")
      (node (ref "U101") (pin "80") (pinfunction "PC12_80") (pintype "bidirectional"))
      (node (ref "U301") (pin "5") (pinfunction "CLK_5") (pintype "bidirectional"))
    )
    (net (code "198") (name "SDIO_CMD") (class "Default")
      (node (ref "R303") (pin "P$1") (pinfunction "1_P$1") (pintype "passive"))
      (node (ref "U101") (pin "83") (pinfunction "PD2_83") (pintype "bidirectional"))
      (node (ref "U301") (pin "3") (pinfunction "CMD_3") (pintype "bidirectional"))
    )
    (net (code "199") (name "SDIO_D0") (class "Default")
      (node (ref "R304") (pin "P$1") (pinfunction "1_P$1") (pintype "passive"))
      (node (ref "U101") (pin "65") (pinfunction "PC8_65") (pintype "bidirectional"))
      (node (ref "U301") (pin "7") (pinfunction "D0_7") (pintype "bidirectional"))
    )
    (net (code "200") (name "SDIO_D1") (class "Default")
      (node (ref "R305") (pin "P$1") (pinfunction "1_P$1") (pintype "passive"))
      (node (ref "U101") (pin "66") (pinfunction "PC9_66") (pintype "bidirectional"))
      (node (ref "U301") (pin "8") (pinfunction "D1_8") (pintype "bidirectional"))
    )
    (net (code "201") (name "SDIO_D2") (class "Default")
      (node (ref "R301") (pin "P$1") (pinfunction "1_P$1") (pintype "passive"))
      (node (ref "U101") (pin "78") (pinfunction "PC10_78") (pintype "bidirectional"))
      (node (ref "U301") (pin "1") (pinfunction "D2_1") (pintype "bidirectional"))
    )
    (net (code "202") (name "SDIO_D3") (class "Default")
      (node (ref "R302") (pin "P$1") (pinfunction "1_P$1") (pintype "passive"))
      (node (ref "U101") (pin "79") (pinfunction "PC11_79") (pintype "bidirectional"))
      (node (ref "U301") (pin "2") (pinfunction "D3_2") (pintype "bidirectional"))
    )
    (net (code "203") (name "SERIAL1_CTS") (class "Default")
      (node (ref "J201") (pin "P$4") (pinfunction "4_P$4") (pintype "passive"))
      (node (ref "R211") (pin "P$2") (pinfunction "2_P$2") (pintype "passive"))
    )
    (net (code "204") (name "SERIAL1_RTS") (class "Default")
      (node (ref "J201") (pin "P$5") (pinfunction "5_P$5") (pintype "passive"))
      (node (ref "R204") (pin "P$2") (pinfunction "2_P$2") (pintype "passive"))
    )
    (net (code "205") (name "SERIAL1_RX") (class "Default")
      (node (ref "J201") (pin "P$3") (pinfunction "3_P$3") (pintype "passive"))
      (node (ref "R203") (pin "P$2") (pinfunction "2_P$2") (pintype "passive"))
      (node (ref "S1RX") (pin "P$1") (pinfunction "P$1_P$1") (pintype "passive"))
    )
    (net (code "206") (name "SERIAL1_TX") (class "Default")
      (node (ref "J201") (pin "P$2") (pinfunction "2_P$2") (pintype "passive"))
      (node (ref "R210") (pin "P$2") (pinfunction "2_P$2") (pintype "passive"))
      (node (ref "S1TX") (pin "P$1") (pinfunction "P$1_P$1") (pintype "passive"))
    )
    (net (code "207") (name "SERIAL2_CTS") (class "Default")
      (node (ref "J202") (pin "P$4") (pinfunction "4_P$4") (pintype "passive"))
      (node (ref "R208") (pin "P$2") (pinfunction "2_P$2") (pintype "passive"))
    )
    (net (code "208") (name "SERIAL2_RTS") (class "Default")
      (node (ref "J202") (pin "P$5") (pinfunction "5_P$5") (pintype "passive"))
      (node (ref "R201") (pin "P$2") (pinfunction "2_P$2") (pintype "passive"))
    )
    (net (code "209") (name "SERIAL2_RX") (class "Default")
      (node (ref "J202") (pin "P$3") (pinfunction "3_P$3") (pintype "passive"))
      (node (ref "R202") (pin "P$2") (pinfunction "2_P$2") (pintype "passive"))
      (node (ref "S2RX") (pin "P$1") (pinfunction "P$1_P$1") (pintype "passive"))
    )
    (net (code "210") (name "SERIAL2_TX") (class "Default")
      (node (ref "J202") (pin "P$2") (pinfunction "2_P$2") (pintype "passive"))
      (node (ref "R209") (pin "P$2") (pinfunction "2_P$2") (pintype "passive"))
      (node (ref "S2TX") (pin "P$1") (pinfunction "P$1_P$1") (pintype "passive"))
    )
    (net (code "211") (name "SERIAL3_RX") (class "Default")
      (node (ref "J203") (pin "P$3") (pinfunction "3_P$3") (pintype "passive"))
      (node (ref "R207") (pin "P$2") (pinfunction "2_P$2") (pintype "passive"))
      (node (ref "S3RX") (pin "P$1") (pinfunction "P$1_P$1") (pintype "passive"))
    )
    (net (code "212") (name "SERIAL3_TX") (class "Default")
      (node (ref "J203") (pin "P$2") (pinfunction "2_P$2") (pintype "passive"))
      (node (ref "R214") (pin "P$2") (pinfunction "2_P$2") (pintype "passive"))
      (node (ref "S3TX") (pin "P$1") (pinfunction "P$1_P$1") (pintype "passive"))
    )
    (net (code "213") (name "SERIAL4_RX") (class "Default")
      (node (ref "J204") (pin "P$3") (pinfunction "3_P$3") (pintype "passive"))
      (node (ref "R206") (pin "P$2") (pinfunction "2_P$2") (pintype "passive"))
      (node (ref "S4RX") (pin "P$1") (pinfunction "P$1_P$1") (pintype "passive"))
    )
    (net (code "214") (name "SERIAL4_TX") (class "Default")
      (node (ref "J204") (pin "P$2") (pinfunction "2_P$2") (pintype "passive"))
      (node (ref "R213") (pin "P$2") (pinfunction "2_P$2") (pintype "passive"))
      (node (ref "S4TX") (pin "P$1") (pinfunction "P$1_P$1") (pintype "passive"))
    )
    (net (code "215") (name "SERIAL5_RX") (class "Default")
      (node (ref "J204") (pin "P$5") (pinfunction "5_P$5") (pintype "passive"))
      (node (ref "R205") (pin "P$2") (pinfunction "2_P$2") (pintype "passive"))
      (node (ref "S5_RX") (pin "P$1") (pinfunction "P$1_P$1") (pintype "passive"))
    )
    (net (code "216") (name "SERIAL5_TX") (class "Default")
      (node (ref "J204") (pin "P$4") (pinfunction "4_P$4") (pintype "passive"))
      (node (ref "R212") (pin "P$2") (pinfunction "2_P$2") (pintype "passive"))
      (node (ref "S5_TX") (pin "P$1") (pinfunction "P$1_P$1") (pintype "passive"))
    )
    (net (code "217") (name "SERIAL_FMU_TO_IO") (class "Default")
      (node (ref "R804") (pin "P$2") (pinfunction "2_P$2") (pintype "passive"))
      (node (ref "U101") (pin "63") (pinfunction "PC6_63") (pintype "bidirectional"))
    )
    (net (code "218") (name "SERIAL_IO_TO_FMU") (class "Default")
      (node (ref "R803") (pin "P$2") (pinfunction "2_P$2") (pintype "passive"))
      (node (ref "U101") (pin "64") (pinfunction "PC7_64") (pintype "bidirectional"))
    )
    (net (code "219") (name "SPI_EXT_MISO") (class "Default")
      (node (ref "J403") (pin "P$3") (pinfunction "3_P$3") (pintype "passive"))
      (node (ref "U101") (pin "4") (pinfunction "PE5_4") (pintype "bidirectional"))
    )
    (net (code "220") (name "SPI_EXT_MOSI") (class "Default")
      (node (ref "J403") (pin "P$4") (pinfunction "4_P$4") (pintype "passive"))
      (node (ref "U101") (pin "5") (pinfunction "PE6_5") (pintype "bidirectional"))
    )
    (net (code "221") (name "SPI_EXT_SCK") (class "Default")
      (node (ref "J403") (pin "P$2") (pinfunction "2_P$2") (pintype "passive"))
      (node (ref "U101") (pin "1") (pinfunction "PE2_1") (pintype "bidirectional"))
    )
    (net (code "222") (name "SPI_INT_MISO") (class "Default")
      (node (ref "U$1") (pin "9") (pinfunction "S_9") (pintype "passive"))
      (node (ref "U$501") (pin "7") (pinfunction "SDO/SA0_7") (pintype "bidirectional"))
      (node (ref "U101") (pin "31") (pinfunction "PA6_31") (pintype "bidirectional"))
      (node (ref "U501") (pin "4") (pinfunction "SDO/SA0_4") (pintype "bidirectional"))
      (node (ref "U502") (pin "4") (pinfunction "SDO/SA0_4") (pintype "bidirectional"))
      (node (ref "U503") (pin "6") (pinfunction "SDO_6") (pintype "bidirectional"))
    )
    (net (code "223") (name "SPI_INT_MOSI") (class "Default")
      (node (ref "U$1") (pin "8") (pinfunction "S_8") (pintype "passive"))
      (node (ref "U$501") (pin "6") (pinfunction "SDA/SDI/SDO_6") (pintype "bidirectional"))
      (node (ref "U101") (pin "32") (pinfunction "PA7_32") (pintype "bidirectional"))
      (node (ref "U501") (pin "3") (pinfunction "SDA/SDI/SDO_3") (pintype "bidirectional"))
      (node (ref "U502") (pin "3") (pinfunction "SDA/SDI/SDO_3") (pintype "bidirectional"))
      (node (ref "U503") (pin "7") (pinfunction "SDI/SDA_7") (pintype "bidirectional"))
    )
    (net (code "224") (name "SPI_INT_SCK") (class "Default")
      (node (ref "U$1") (pin "10") (pinfunction "S_10") (pintype "passive"))
      (node (ref "U$501") (pin "4") (pinfunction "SCL/SPC_4") (pintype "bidirectional"))
      (node (ref "U101") (pin "30") (pinfunction "PA5_30") (pintype "bidirectional"))
      (node (ref "U501") (pin "2") (pinfunction "SCL/SPC_2") (pintype "input"))
      (node (ref "U502") (pin "2") (pinfunction "SCL/SPC_2") (pintype "bidirectional"))
      (node (ref "U503") (pin "8") (pinfunction "SCLK_8") (pintype "bidirectional"))
    )
    (net (code "225") (name "VBAT") (class "Default")
      (node (ref "B601") (pin "1") (pinfunction "POS_1") (pintype "bidirectional"))
      (node (ref "R608") (pin "P$1") (pinfunction "1_P$1") (pintype "passive"))
      (node (ref "U101") (pin "6") (pinfunction "VBAT_6") (pintype "power_in"))
      (node (ref "U801") (pin "1") (pinfunction "VBAT_1") (pintype "power_in"))
    )
    (net (code "226") (name "VBUS") (class "Default")
      (node (ref "J301") (pin "VBUS") (pinfunction "1_VBUS") (pintype "power_in"))
      (node (ref "J302") (pin "P$1") (pinfunction "1_P$1") (pintype "passive"))
      (node (ref "R6") (pin "P$1") (pinfunction "1_P$1") (pintype "passive"))
      (node (ref "U$2") (pin "P$19") (pinfunction "V3_P$19") (pintype "bidirectional"))
      (node (ref "U$301") (pin "5") (pinfunction "VBUS_5") (pintype "bidirectional"))
      (node (ref "U$5") (pin "P$7") (pinfunction "D_P$7") (pintype "passive"))
      (node (ref "U$5") (pin "P$8") (pinfunction "D_P$8") (pintype "passive"))
      (node (ref "U101") (pin "68") (pinfunction "PA9_68") (pintype "bidirectional"))
    )
    (net (code "227") (name "VDD_3V3_SENSORS") (class "Default")
      (node (ref "C501") (pin "P$1") (pinfunction "1_P$1") (pintype "passive"))
      (node (ref "C502") (pin "P$1") (pinfunction "1_P$1") (pintype "passive"))
      (node (ref "C503") (pin "P$1") (pinfunction "1_P$1") (pintype "passive"))
      (node (ref "C506") (pin "P$1") (pinfunction "1_P$1") (pintype "passive"))
      (node (ref "C507") (pin "P$1") (pinfunction "1_P$1") (pintype "passive"))
      (node (ref "C508") (pin "P$1") (pinfunction "1_P$1") (pintype "passive"))
      (node (ref "C605") (pin "P$1") (pinfunction "1_P$1") (pintype "passive"))
      (node (ref "U$1") (pin "1") (pinfunction "S_1") (pintype "passive"))
      (node (ref "U$501") (pin "1") (pinfunction "VDD_IO_1") (pintype "bidirectional"))
      (node (ref "U$501") (pin "14") (pinfunction "VDD_14") (pintype "bidirectional"))
      (node (ref "U$605") (pin "8") (pinfunction "VOUT1_8") (pintype "bidirectional"))
      (node (ref "U501") (pin "1") (pinfunction "VDD_IO_1") (pintype "bidirectional"))
      (node (ref "U501") (pin "15") (pinfunction "RES_P15_VDD_15") (pintype "bidirectional"))
      (node (ref "U501") (pin "16") (pinfunction "VDD_16") (pintype "bidirectional"))
      (node (ref "U502") (pin "1") (pinfunction "VDD_IO_1") (pintype "bidirectional"))
      (node (ref "U502") (pin "15") (pinfunction "VDD_15") (pintype "bidirectional"))
      (node (ref "U502") (pin "16") (pinfunction "VDD_16") (pintype "bidirectional"))
      (node (ref "U503") (pin "1") (pinfunction "VDD_1") (pintype "bidirectional"))
      (node (ref "VDDA_3V1101") (pin "P$1") (pinfunction "P$1_P$1") (pintype "passive"))
    )
    (net (code "228") (name "VDD_3V3_SENSORS_EN") (class "Default")
      (node (ref "R603") (pin "P$1") (pinfunction "1_P$1") (pintype "passive"))
      (node (ref "U$605") (pin "5") (pinfunction "EN1_5") (pintype "bidirectional"))
      (node (ref "U101") (pin "2") (pinfunction "PE3_2") (pintype "bidirectional"))
    )
    (net (code "229") (name "VDD_3V3_SPEKTRUM") (class "Default")
      (node (ref "C1003") (pin "P$1") (pinfunction "1_P$1") (pintype "passive"))
      (node (ref "J801") (pin "P$1") (pinfunction "P$1_P$1") (pintype "bidirectional"))
      (node (ref "U$1002") (pin "8") (pinfunction "VOUT1_8") (pintype "bidirectional"))
      (node (ref "U$801") (pin "C") (pinfunction "C_C") (pintype "passive"))
    )
    (net (code "230") (name "VDD_3V3_SPEKTRUM_EN") (class "Default")
      (node (ref "R1002") (pin "P$2") (pinfunction "2_P$2") (pintype "passive"))
      (node (ref "U$1002") (pin "5") (pinfunction "EN1_5") (pintype "bidirectional"))
      (node (ref "U801") (pin "2") (pinfunction "PC13_2") (pintype "bidirectional"))
    )
    (net (code "231") (name "VDD_5V_BRICK") (class "Default")
      (node (ref "J601") (pin "P$1") (pinfunction "1_P$1") (pintype "passive"))
      (node (ref "J601") (pin "P$2") (pinfunction "2_P$2") (pintype "passive"))
      (node (ref "R1") (pin "P$1") (pinfunction "1_P$1") (pintype "passive"))
      (node (ref "U$2") (pin "P$21") (pinfunction "V1_P$21") (pintype "bidirectional"))
      (node (ref "U$3") (pin "P$7") (pinfunction "D_P$7") (pintype "passive"))
      (node (ref "U$3") (pin "P$8") (pinfunction "D_P$8") (pintype "passive"))
      (node (ref "VDD_5V_BRICK") (pin "P$1") (pinfunction "P$1_P$1") (pintype "passive"))
    )
    (net (code "232") (name "VDD_5V_HIPOWER") (class "Default")
      (node (ref "L201") (pin "P$1") (pinfunction "P$1_P$1") (pintype "bidirectional"))
      (node (ref "U$602") (pin "8") (pinfunction "OUT_8") (pintype "bidirectional"))
    )
    (net (code "233") (name "VDD_5V_IN") (class "Default")
      (node (ref "C702") (pin "P$1") (pinfunction "1_P$1") (pintype "passive"))
      (node (ref "F2") (pin "1") (pinfunction "1_1") (pintype "bidirectional"))
      (node (ref "L603") (pin "P$1") (pinfunction "P$1_P$1") (pintype "bidirectional"))
      (node (ref "L701") (pin "P$1") (pinfunction "1_P$1") (pintype "passive"))
      (node (ref "LED701") (pin "A") (pinfunction "A_A") (pintype "passive"))
      (node (ref "LED704") (pin "A") (pinfunction "A_A") (pintype "passive"))
      (node (ref "R609") (pin "P$2") (pinfunction "2_P$2") (pintype "passive"))
      (node (ref "U$2") (pin "P$12") (pinfunction "VOUT_P$12") (pintype "bidirectional"))
      (node (ref "U$3") (pin "P$5") (pinfunction "D_P$5") (pintype "passive"))
      (node (ref "U$3") (pin "P$6") (pinfunction "D_P$6") (pintype "passive"))
      (node (ref "U$4") (pin "P$5") (pinfunction "D_P$5") (pintype "passive"))
      (node (ref "U$4") (pin "P$6") (pinfunction "D_P$6") (pintype "passive"))
      (node (ref "U$5") (pin "P$5") (pinfunction "D_P$5") (pintype "passive"))
      (node (ref "U$5") (pin "P$6") (pinfunction "D_P$6") (pintype "passive"))
      (node (ref "U$602") (pin "1") (pinfunction "IN_1") (pintype "bidirectional"))
      (node (ref "U$604") (pin "1") (pinfunction "IN_1") (pintype "bidirectional"))
      (node (ref "U702") (pin "3") (pinfunction "VIN_3") (pintype "power_in"))
      (node (ref "U703") (pin "A1") (pinfunction "A_A1") (pintype "passive"))
      (node (ref "U703") (pin "A2") (pinfunction "A_A2") (pintype "passive"))
      (node (ref "U703") (pin "A3") (pinfunction "A_A3") (pintype "passive"))
    )
    (net (code "234") (name "VDD_5V_PERIPH") (class "Default")
      (node (ref "L202") (pin "P$1") (pinfunction "P$1_P$1") (pintype "bidirectional"))
      (node (ref "L203") (pin "P$1") (pinfunction "P$1_P$1") (pintype "bidirectional"))
      (node (ref "L401") (pin "P$1") (pinfunction "P$1_P$1") (pintype "bidirectional"))
      (node (ref "L402") (pin "P$1") (pinfunction "P$1_P$1") (pintype "bidirectional"))
      (node (ref "L403") (pin "P$1") (pinfunction "P$1_P$1") (pintype "bidirectional"))
      (node (ref "L404") (pin "P$1") (pinfunction "P$1_P$1") (pintype "bidirectional"))
      (node (ref "U$604") (pin "8") (pinfunction "OUT_8") (pintype "bidirectional"))
    )
    (net (code "235") (name "VDD_5V_SENS") (class "Default")
      (node (ref "R609") (pin "P$1") (pinfunction "1_P$1") (pintype "passive"))
      (node (ref "R610") (pin "P$1") (pinfunction "1_P$1") (pintype "passive"))
      (node (ref "U101") (pin "29") (pinfunction "PA4_29") (pintype "bidirectional"))
    )
    (net (code "236") (name "VDD_SERVO") (class "Default")
      (node (ref "D1") (pin "ANODE") (pinfunction "A_ANODE") (pintype "passive"))
      (node (ref "J901") (pin "11") (pinfunction "S_11") (pintype "passive"))
      (node (ref "J901") (pin "14") (pinfunction "S_14") (pintype "passive"))
      (node (ref "J901") (pin "17") (pinfunction "S_17") (pintype "passive"))
      (node (ref "J901") (pin "20") (pinfunction "S_20") (pintype "passive"))
      (node (ref "J901") (pin "23") (pinfunction "S_23") (pintype "passive"))
      (node (ref "J901") (pin "26") (pinfunction "S_26") (pintype "passive"))
      (node (ref "J901") (pin "29") (pinfunction "S_29") (pintype "passive"))
      (node (ref "J901") (pin "32") (pinfunction "S_32") (pintype "passive"))
      (node (ref "J901") (pin "35") (pinfunction "S_35") (pintype "passive"))
      (node (ref "J901") (pin "38") (pinfunction "S_38") (pintype "passive"))
      (node (ref "J901") (pin "41") (pinfunction "S_41") (pintype "passive"))
      (node (ref "J901") (pin "44") (pinfunction "S_44") (pintype "passive"))
      (node (ref "J901") (pin "47") (pinfunction "S_47") (pintype "passive"))
      (node (ref "J901") (pin "5") (pinfunction "S_5") (pintype "passive"))
      (node (ref "J901") (pin "8") (pinfunction "S_8") (pintype "passive"))
      (node (ref "R9") (pin "P$1") (pinfunction "1_P$1") (pintype "passive"))
      (node (ref "R922") (pin "P$2") (pinfunction "2_P$2") (pintype "passive"))
      (node (ref "U$2") (pin "P$20") (pinfunction "V2_P$20") (pintype "bidirectional"))
      (node (ref "U$4") (pin "P$7") (pinfunction "D_P$7") (pintype "passive"))
      (node (ref "U$4") (pin "P$8") (pinfunction "D_P$8") (pintype "passive"))
    )
    (net (code "237") (name "VDD_SERVO_IN") (class "Default")
      (node (ref "L901") (pin "P$2") (pinfunction "P$2_P$2") (pintype "bidirectional"))
      (node (ref "U$1001") (pin "1") (pinfunction "IN_1") (pintype "bidirectional"))
    )
    (net (code "238") (name "VDD_SERVO_SENS") (class "Default")
      (node (ref "R918") (pin "P$1") (pinfunction "1_P$1") (pintype "passive"))
      (node (ref "R919") (pin "P$2") (pinfunction "2_P$2") (pintype "passive"))
      (node (ref "U801") (pin "14") (pinfunction "PA4_14") (pintype "bidirectional"))
    )
    (net (code "239") (name "unconnected-(J301-4-PadID)") (class "Default")
      (node (ref "J301") (pin "ID") (pinfunction "4_ID") (pintype "passive"))
    )
    (net (code "240") (name "unconnected-(JX301A-S-Pad10)") (class "Default")
      (node (ref "JX301") (pin "10") (pinfunction "S_10") (pintype "passive"))
    )
    (net (code "241") (name "unconnected-(JX301F-S-Pad8)") (class "Default")
      (node (ref "JX301") (pin "8") (pinfunction "S_8") (pintype "passive"))
    )
    (net (code "242") (name "unconnected-(JX802A-S-Pad10)") (class "Default")
      (node (ref "JX802") (pin "10") (pinfunction "S_10") (pintype "passive"))
    )
    (net (code "243") (name "unconnected-(JX802F-S-Pad8)") (class "Default")
      (node (ref "JX802") (pin "8") (pinfunction "S_8") (pintype "passive"))
    )
    (net (code "244") (name "unconnected-(U$2-CAS-PadP$11)") (class "Default")
      (node (ref "U$2") (pin "P$11") (pinfunction "CAS_P$11") (pintype "bidirectional"))
    )
    (net (code "245") (name "unconnected-(U$2-EN-PadP$22)") (class "Default")
      (node (ref "U$2") (pin "P$22") (pinfunction "EN_P$22") (pintype "bidirectional"))
    )
    (net (code "246") (name "unconnected-(U$2-~{SHDN}-PadP$23)") (class "Default")
      (node (ref "U$2") (pin "P$23") (pinfunction "~{SHDN}_P$23") (pintype "bidirectional"))
    )
    (net (code "247") (name "unconnected-(U101I-PC0-Pad15)") (class "Default")
      (node (ref "U101") (pin "15") (pinfunction "PC0_15") (pintype "bidirectional"))
    )
    (net (code "248") (name "unconnected-(U101I-PC1-Pad16)") (class "Default")
      (node (ref "U101") (pin "16") (pinfunction "PC1_16") (pintype "bidirectional"))
    )
    (net (code "249") (name "unconnected-(U101I-PC2-Pad17)") (class "Default")
      (node (ref "U101") (pin "17") (pinfunction "PC2_17") (pintype "bidirectional"))
    )
    (net (code "250") (name "unconnected-(U101J-PD15-Pad62)") (class "Default")
      (node (ref "U101") (pin "62") (pinfunction "PD15_62") (pintype "bidirectional"))
    )
    (net (code "251") (name "unconnected-(U202-A1-Pad1)") (class "Default")
      (node (ref "U202") (pin "1") (pinfunction "A1_1") (pintype "bidirectional"))
    )
    (net (code "252") (name "unconnected-(U202-A2-Pad3)") (class "Default")
      (node (ref "U202") (pin "3") (pinfunction "A2_3") (pintype "bidirectional"))
    )
    (net (code "253") (name "unconnected-(U202-B1-Pad20)") (class "Default")
      (node (ref "U202") (pin "20") (pinfunction "B1_20") (pintype "bidirectional"))
    )
    (net (code "254") (name "unconnected-(U202-B2-Pad18)") (class "Default")
      (node (ref "U202") (pin "18") (pinfunction "B2_18") (pintype "bidirectional"))
    )
    (net (code "255") (name "unconnected-(U501-INT1-Pad7)") (class "Default")
      (node (ref "U501") (pin "7") (pinfunction "INT1_7") (pintype "output"))
    )
    (net (code "256") (name "unconnected-(U502-DEN-Pad8)") (class "Default")
      (node (ref "U502") (pin "8") (pinfunction "DEN_8") (pintype "bidirectional"))
    )
    (net (code "257") (name "unconnected-(U502-INT1-Pad7)") (class "Default")
      (node (ref "U502") (pin "7") (pinfunction "INT1_7") (pintype "bidirectional"))
    )
    (net (code "258") (name "unconnected-(U503-CSB1-Pad4)") (class "Default")
      (node (ref "U503") (pin "4") (pinfunction "CSB1_4") (pintype "bidirectional"))
    )
    (net (code "259") (name "unconnected-(U801B-PA11-Pad32)") (class "Default")
      (node (ref "U801") (pin "32") (pinfunction "PA11_32") (pintype "bidirectional"))
    )
    (net (code "260") (name "unconnected-(U801D-PB12-Pad25)") (class "Default")
      (node (ref "U801") (pin "25") (pinfunction "PB12_25") (pintype "bidirectional"))
    )
    (net (code "261") (name "unconnected-(U801E-PB6-Pad42)") (class "Default")
      (node (ref "U801") (pin "42") (pinfunction "PB6_42") (pintype "bidirectional"))
    )
    (net (code "262") (name "unconnected-(U801E-PB7-Pad43)") (class "Default")
      (node (ref "U801") (pin "43") (pinfunction "PB7_43") (pintype "bidirectional"))
    )
    (net (code "263") (name "unconnected-(U801F-PC14-Pad3)") (class "Default")
      (node (ref "U801") (pin "3") (pinfunction "PC14_3") (pintype "bidirectional"))
    )
    (net (code "264") (name "unconnected-(U801F-PC15-Pad4)") (class "Default")
      (node (ref "U801") (pin "4") (pinfunction "PC15_4") (pintype "bidirectional"))
    )
    (net (code "265") (name "unconnected-(U901-A7-Pad8)") (class "Default")
      (node (ref "U901") (pin "8") (pinfunction "A7_8") (pintype "bidirectional"))
    )
    (net (code "266") (name "unconnected-(U901-A8-Pad9)") (class "Default")
      (node (ref "U901") (pin "9") (pinfunction "A8_9") (pintype "bidirectional"))
    )
    (net (code "267") (name "unconnected-(U901-B7-Pad13)") (class "Default")
      (node (ref "U901") (pin "13") (pinfunction "B7_13") (pintype "bidirectional"))
    )
    (net (code "268") (name "unconnected-(U901-B8-Pad12)") (class "Default")
      (node (ref "U901") (pin "12") (pinfunction "B8_12") (pintype "bidirectional"))
    )
    (net (code "269") (name "~{ACCEL_MAG_CS}") (class "Default")
      (node (ref "U$1") (pin "6") (pinfunction "S_6") (pintype "passive"))
      (node (ref "U$501") (pin "8") (pinfunction "CS_8") (pintype "bidirectional"))
      (node (ref "U101") (pin "9") (pinfunction "PC15_9") (pintype "bidirectional"))
    )
    (net (code "270") (name "~{BARO_CS}") (class "Default")
      (node (ref "U101") (pin "88") (pinfunction "PD7_88") (pintype "bidirectional"))
      (node (ref "U503") (pin "5") (pinfunction "CSB2_5") (pintype "bidirectional"))
    )
    (net (code "271") (name "~{FMU-LED_AMBER}") (class "Default")
      (node (ref "R707") (pin "P$1") (pinfunction "1_P$1") (pintype "passive"))
      (node (ref "U101") (pin "43") (pinfunction "PE12_43") (pintype "bidirectional"))
    )
    (net (code "272") (name "~{FRAM_CS}") (class "Default")
      (node (ref "U101") (pin "57") (pinfunction "PD10_57") (pintype "bidirectional"))
      (node (ref "U102") (pin "1") (pinfunction "~{S}_1") (pintype "bidirectional"))
    )
    (net (code "273") (name "~{GYRO_CS}") (class "Default")
      (node (ref "U$1") (pin "7") (pinfunction "S_7") (pintype "passive"))
      (node (ref "U101") (pin "7") (pinfunction "PC13_7") (pintype "bidirectional"))
      (node (ref "U501") (pin "5") (pinfunction "CS_5") (pintype "input"))
      (node (ref "U502") (pin "5") (pinfunction "CS_5") (pintype "bidirectional"))
    )
    (net (code "274") (name "~{IO-LED_AMBER}") (class "Default")
      (node (ref "R709") (pin "P$1") (pinfunction "1_P$1") (pintype "passive"))
      (node (ref "U801") (pin "28") (pinfunction "PB15_28") (pintype "bidirectional"))
    )
    (net (code "275") (name "~{IO-LED_BLUE}") (class "Default")
      (node (ref "R712") (pin "P$1") (pinfunction "1_P$1") (pintype "passive"))
      (node (ref "U801") (pin "27") (pinfunction "PB14_27") (pintype "bidirectional"))
    )
    (net (code "276") (name "~{IO-LED_SAFETY}") (class "Default")
      (node (ref "R710") (pin "P$2") (pinfunction "2_P$2") (pintype "passive"))
      (node (ref "U801") (pin "26") (pinfunction "PB13_26") (pintype "bidirectional"))
    )
    (net (code "277") (name "~{SBUS_OUTPUT_EN}") (class "Default")
      (node (ref "U801") (pin "40") (pinfunction "PB4_40") (pintype "bidirectional"))
      (node (ref "U903") (pin "7") (pinfunction "~{2OE}_7") (pintype "input"))
    )
    (net (code "278") (name "~{SPI_EXT_NSS}") (class "Default")
      (node (ref "J403") (pin "P$5") (pinfunction "5_P$5") (pintype "passive"))
      (node (ref "U101") (pin "3") (pinfunction "PE4_3") (pintype "bidirectional"))
    )
    (net (code "279") (name "~{VBUS_VALID}") (class "Default")
      (node (ref "U$2") (pin "P$9") (pinfunction "~{VALID3}_P$9") (pintype "bidirectional"))
    )
    (net (code "280") (name "~{VDD_5V_HIPOWER_OC}") (class "Default")
      (node (ref "U$602") (pin "4") (pinfunction "~{FAULT}_4") (pintype "bidirectional"))
      (node (ref "U101") (pin "41") (pinfunction "PE10_41") (pintype "bidirectional"))
    )
    (net (code "281") (name "~{VDD_5V_PERIPH_EN}") (class "Default")
      (node (ref "R607") (pin "P$1") (pinfunction "1_P$1") (pintype "passive"))
      (node (ref "U$602") (pin "5") (pinfunction "~{CE}_5") (pintype "bidirectional"))
      (node (ref "U$604") (pin "5") (pinfunction "~{CE}_5") (pintype "bidirectional"))
      (node (ref "U101") (pin "67") (pinfunction "PA8_67") (pintype "bidirectional"))
    )
    (net (code "282") (name "~{VDD_5V_PERIPH_OC}") (class "Default")
      (node (ref "U$604") (pin "4") (pinfunction "~{FAULT}_4") (pintype "bidirectional"))
      (node (ref "U101") (pin "46") (pinfunction "PE15_46") (pintype "bidirectional"))
    )
    (net (code "283") (name "~{VDD_BRICK_VALID}") (class "Default")
      (node (ref "U$2") (pin "P$7") (pinfunction "~{VALID1}_P$7") (pintype "bidirectional"))
      (node (ref "U101") (pin "91") (pinfunction "PB5_91") (pintype "bidirectional"))
    )
    (net (code "284") (name "~{VDD_SERVO_VALID}") (class "Default")
      (node (ref "U$2") (pin "P$8") (pinfunction "~{VALID2}_P$8") (pintype "bidirectional"))
      (node (ref "U101") (pin "93") (pinfunction "PB7_93") (pintype "bidirectional"))
    )
  )
)
